# M847.net
KiCad netlist of a schematic drawn in EAGLE
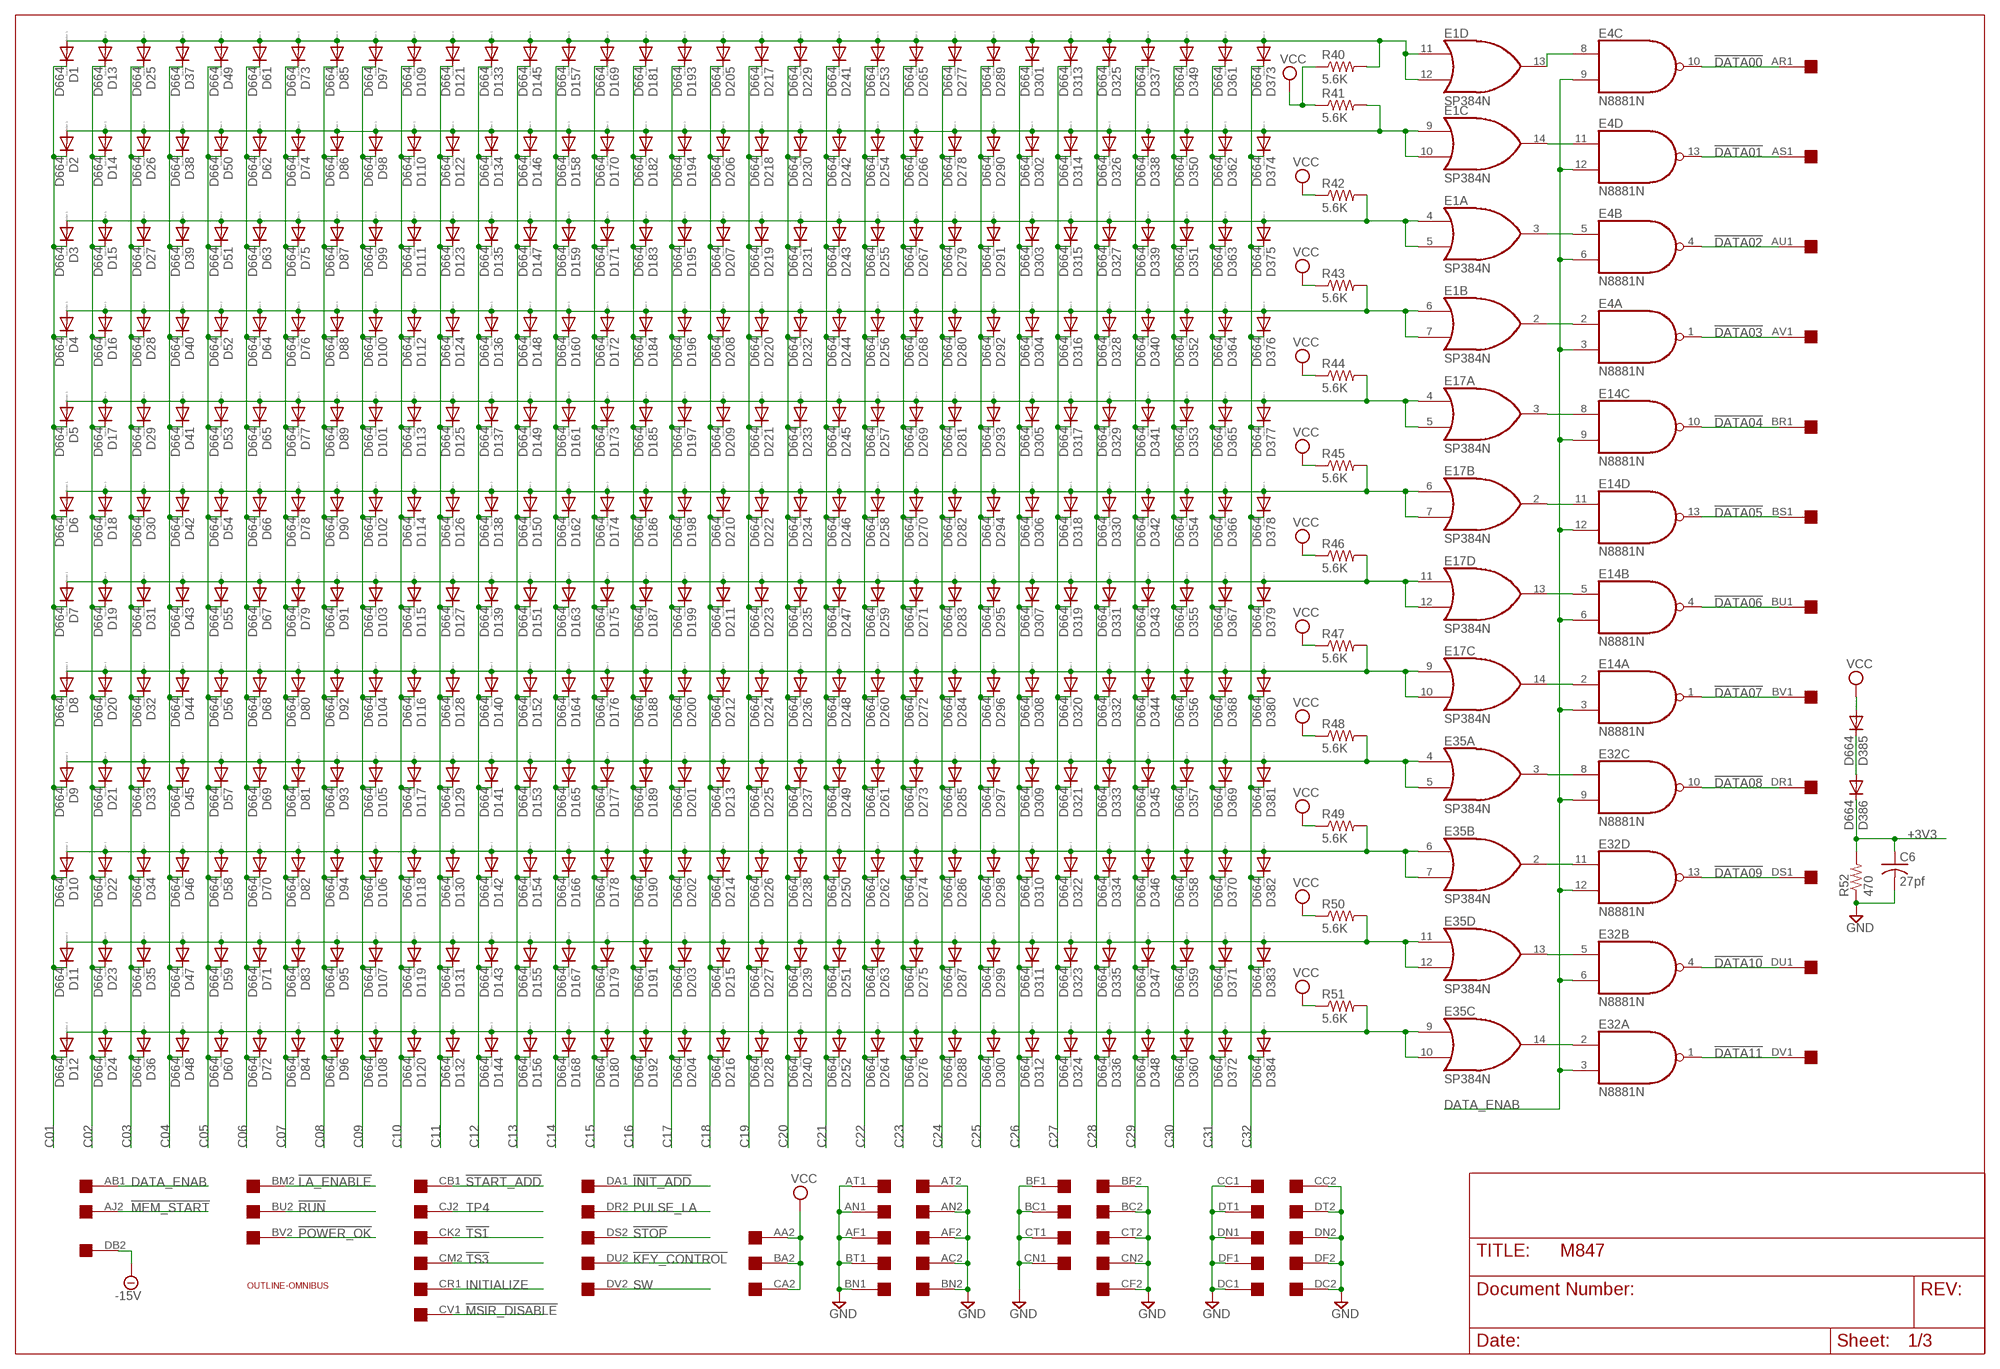
[diagram p0: schematic, sheet 1]
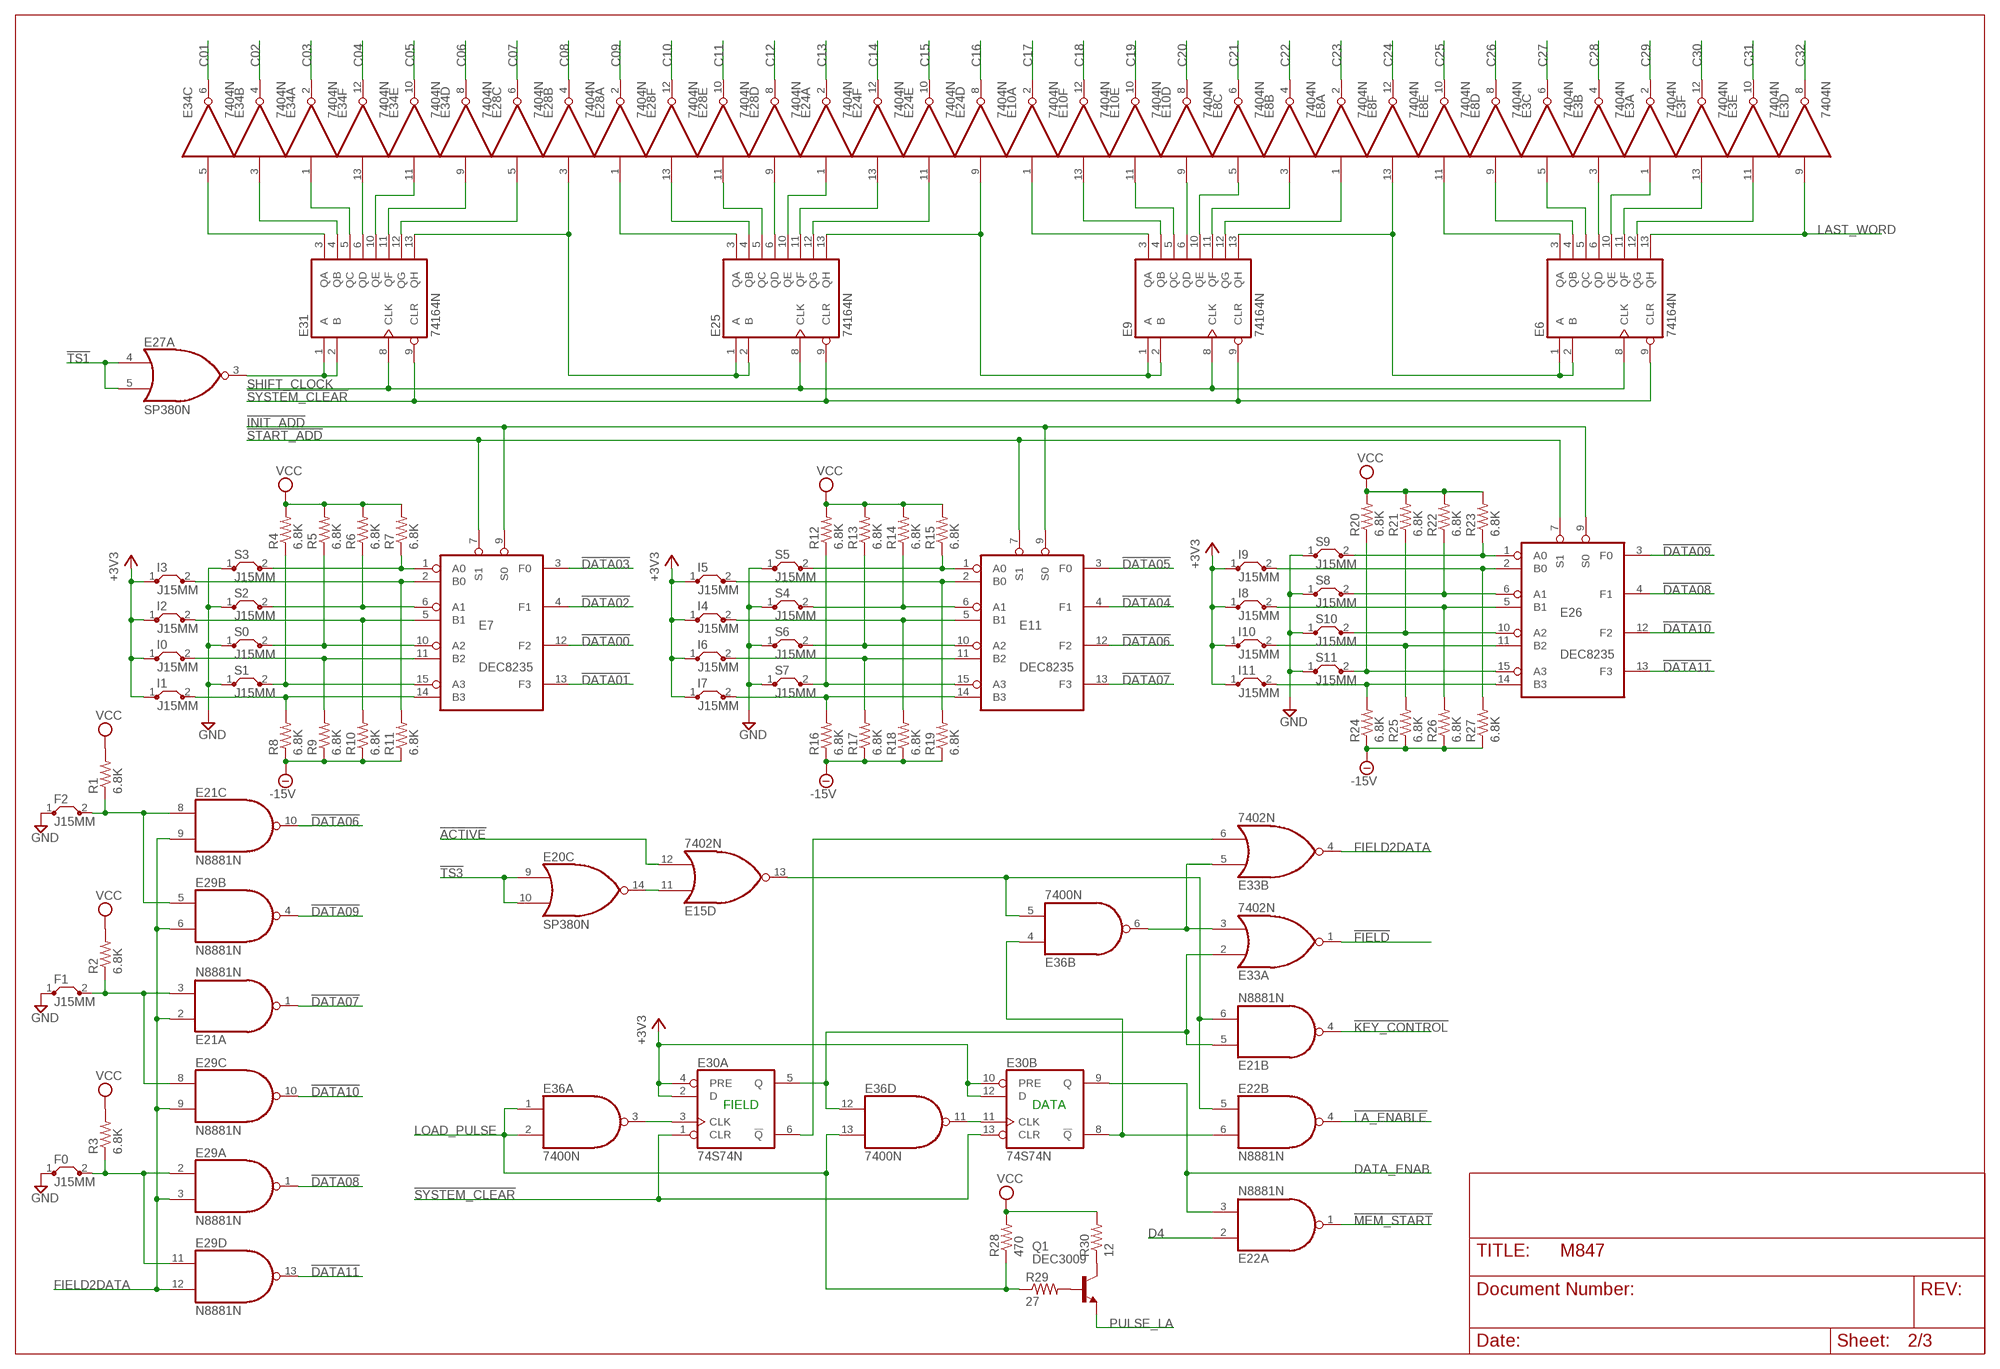
[diagram p1: schematic, sheet 2]
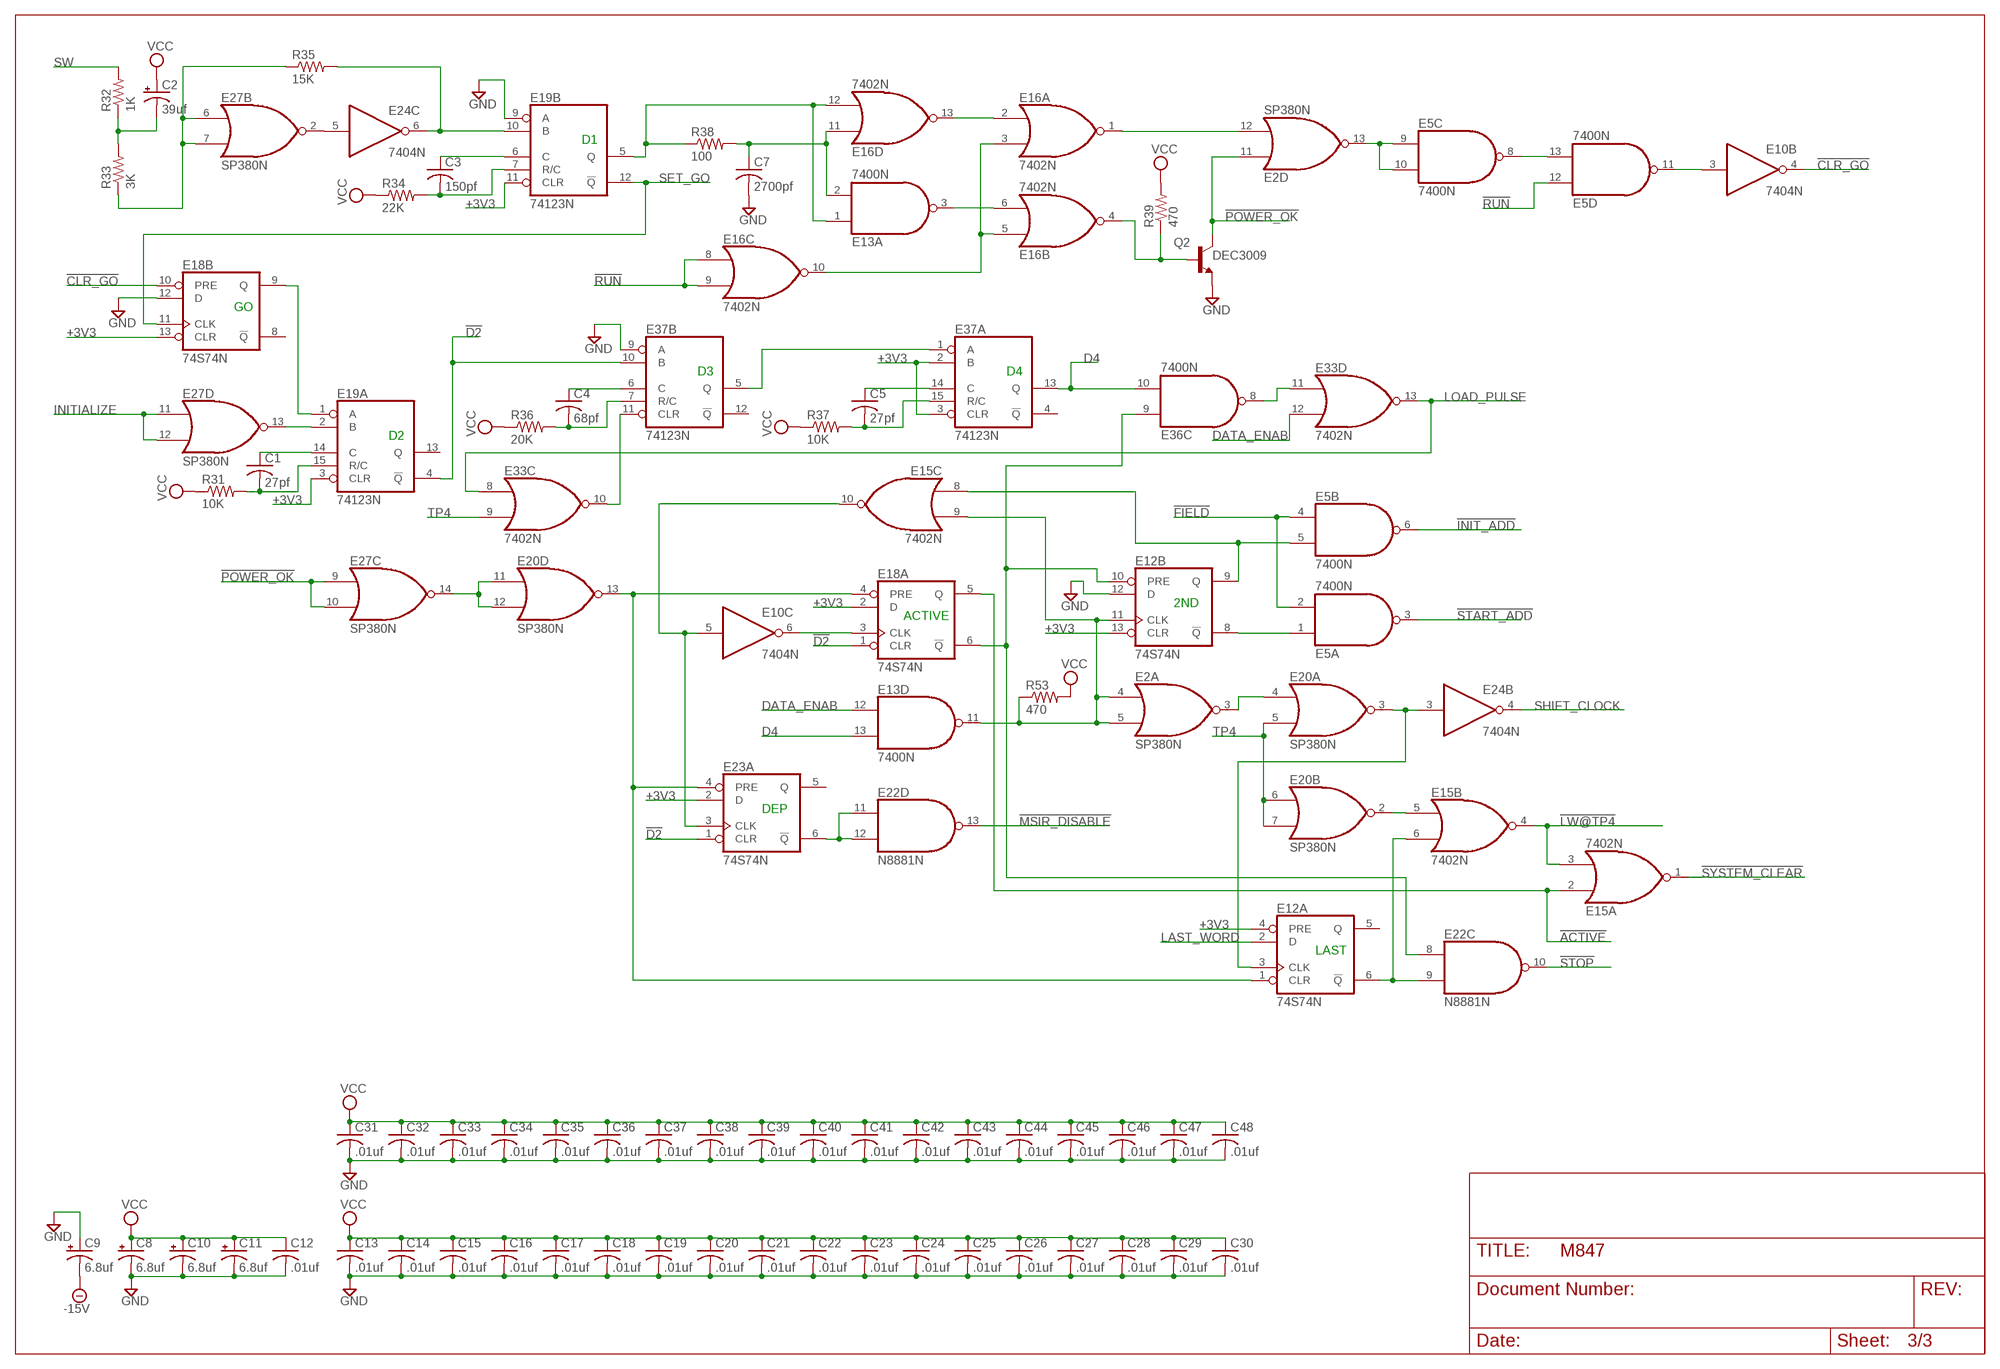
[diagram p2: schematic, sheet 3]

(export (version "E")
  (design (tool "Eeschema 10.0.6"))
  (components
    (comp (ref "C6")
      (value "27pf")
      (footprint "eagle-import:C050-025X075")
      (libsource (lib "eagle-import") (part "C-US050-025X075"))
    )
    (comp (ref "D1")
      (value "D664")
      (footprint "eagle-import:DO35-10")
      (libsource (lib "eagle-import") (part "1N4148DO35-10"))
    )
    (comp (ref "D2")
      (value "D664")
      (footprint "eagle-import:DO35-10")
      (libsource (lib "eagle-import") (part "1N4148DO35-10"))
    )
    (comp (ref "D3")
      (value "D664")
      (footprint "eagle-import:DO35-10")
      (libsource (lib "eagle-import") (part "1N4148DO35-10"))
    )
    (comp (ref "D4")
      (value "D664")
      (footprint "eagle-import:DO35-10")
      (libsource (lib "eagle-import") (part "1N4148DO35-10"))
    )
    (comp (ref "D5")
      (value "D664")
      (footprint "eagle-import:DO35-10")
      (libsource (lib "eagle-import") (part "1N4148DO35-10"))
    )
    (comp (ref "D6")
      (value "D664")
      (footprint "eagle-import:DO35-10")
      (libsource (lib "eagle-import") (part "1N4148DO35-10"))
    )
    (comp (ref "D7")
      (value "D664")
      (footprint "eagle-import:DO35-10")
      (libsource (lib "eagle-import") (part "1N4148DO35-10"))
    )
    (comp (ref "D8")
      (value "D664")
      (footprint "eagle-import:DO35-10")
      (libsource (lib "eagle-import") (part "1N4148DO35-10"))
    )
    (comp (ref "D9")
      (value "D664")
      (footprint "eagle-import:DO35-10")
      (libsource (lib "eagle-import") (part "1N4148DO35-10"))
    )
    (comp (ref "D10")
      (value "D664")
      (footprint "eagle-import:DO35-10")
      (libsource (lib "eagle-import") (part "1N4148DO35-10"))
    )
    (comp (ref "D11")
      (value "D664")
      (footprint "eagle-import:DO35-10")
      (libsource (lib "eagle-import") (part "1N4148DO35-10"))
    )
    (comp (ref "D12")
      (value "D664")
      (footprint "eagle-import:DO35-10")
      (libsource (lib "eagle-import") (part "1N4148DO35-10"))
    )
    (comp (ref "D13")
      (value "D664")
      (footprint "eagle-import:DO35-10")
      (libsource (lib "eagle-import") (part "1N4148DO35-10"))
    )
    (comp (ref "D14")
      (value "D664")
      (footprint "eagle-import:DO35-10")
      (libsource (lib "eagle-import") (part "1N4148DO35-10"))
    )
    (comp (ref "D15")
      (value "D664")
      (footprint "eagle-import:DO35-10")
      (libsource (lib "eagle-import") (part "1N4148DO35-10"))
    )
    (comp (ref "D16")
      (value "D664")
      (footprint "eagle-import:DO35-10")
      (libsource (lib "eagle-import") (part "1N4148DO35-10"))
    )
    (comp (ref "D17")
      (value "D664")
      (footprint "eagle-import:DO35-10")
      (libsource (lib "eagle-import") (part "1N4148DO35-10"))
    )
    (comp (ref "D18")
      (value "D664")
      (footprint "eagle-import:DO35-10")
      (libsource (lib "eagle-import") (part "1N4148DO35-10"))
    )
    (comp (ref "D19")
      (value "D664")
      (footprint "eagle-import:DO35-10")
      (libsource (lib "eagle-import") (part "1N4148DO35-10"))
    )
    (comp (ref "D20")
      (value "D664")
      (footprint "eagle-import:DO35-10")
      (libsource (lib "eagle-import") (part "1N4148DO35-10"))
    )
    (comp (ref "D21")
      (value "D664")
      (footprint "eagle-import:DO35-10")
      (libsource (lib "eagle-import") (part "1N4148DO35-10"))
    )
    (comp (ref "D22")
      (value "D664")
      (footprint "eagle-import:DO35-10")
      (libsource (lib "eagle-import") (part "1N4148DO35-10"))
    )
    (comp (ref "D23")
      (value "D664")
      (footprint "eagle-import:DO35-10")
      (libsource (lib "eagle-import") (part "1N4148DO35-10"))
    )
    (comp (ref "D24")
      (value "D664")
      (footprint "eagle-import:DO35-10")
      (libsource (lib "eagle-import") (part "1N4148DO35-10"))
    )
    (comp (ref "D25")
      (value "D664")
      (footprint "eagle-import:DO35-10")
      (libsource (lib "eagle-import") (part "1N4148DO35-10"))
    )
    (comp (ref "D26")
      (value "D664")
      (footprint "eagle-import:DO35-10")
      (libsource (lib "eagle-import") (part "1N4148DO35-10"))
    )
    (comp (ref "D27")
      (value "D664")
      (footprint "eagle-import:DO35-10")
      (libsource (lib "eagle-import") (part "1N4148DO35-10"))
    )
    (comp (ref "D28")
      (value "D664")
      (footprint "eagle-import:DO35-10")
      (libsource (lib "eagle-import") (part "1N4148DO35-10"))
    )
    (comp (ref "D29")
      (value "D664")
      (footprint "eagle-import:DO35-10")
      (libsource (lib "eagle-import") (part "1N4148DO35-10"))
    )
    (comp (ref "D30")
      (value "D664")
      (footprint "eagle-import:DO35-10")
      (libsource (lib "eagle-import") (part "1N4148DO35-10"))
    )
    (comp (ref "D31")
      (value "D664")
      (footprint "eagle-import:DO35-10")
      (libsource (lib "eagle-import") (part "1N4148DO35-10"))
    )
    (comp (ref "D32")
      (value "D664")
      (footprint "eagle-import:DO35-10")
      (libsource (lib "eagle-import") (part "1N4148DO35-10"))
    )
    (comp (ref "D33")
      (value "D664")
      (footprint "eagle-import:DO35-10")
      (libsource (lib "eagle-import") (part "1N4148DO35-10"))
    )
    (comp (ref "D34")
      (value "D664")
      (footprint "eagle-import:DO35-10")
      (libsource (lib "eagle-import") (part "1N4148DO35-10"))
    )
    (comp (ref "D35")
      (value "D664")
      (footprint "eagle-import:DO35-10")
      (libsource (lib "eagle-import") (part "1N4148DO35-10"))
    )
    (comp (ref "D36")
      (value "D664")
      (footprint "eagle-import:DO35-10")
      (libsource (lib "eagle-import") (part "1N4148DO35-10"))
    )
    (comp (ref "D37")
      (value "D664")
      (footprint "eagle-import:DO35-10")
      (libsource (lib "eagle-import") (part "1N4148DO35-10"))
    )
    (comp (ref "D38")
      (value "D664")
      (footprint "eagle-import:DO35-10")
      (libsource (lib "eagle-import") (part "1N4148DO35-10"))
    )
    (comp (ref "D39")
      (value "D664")
      (footprint "eagle-import:DO35-10")
      (libsource (lib "eagle-import") (part "1N4148DO35-10"))
    )
    (comp (ref "D40")
      (value "D664")
      (footprint "eagle-import:DO35-10")
      (libsource (lib "eagle-import") (part "1N4148DO35-10"))
    )
    (comp (ref "D41")
      (value "D664")
      (footprint "eagle-import:DO35-10")
      (libsource (lib "eagle-import") (part "1N4148DO35-10"))
    )
    (comp (ref "D42")
      (value "D664")
      (footprint "eagle-import:DO35-10")
      (libsource (lib "eagle-import") (part "1N4148DO35-10"))
    )
    (comp (ref "D43")
      (value "D664")
      (footprint "eagle-import:DO35-10")
      (libsource (lib "eagle-import") (part "1N4148DO35-10"))
    )
    (comp (ref "D44")
      (value "D664")
      (footprint "eagle-import:DO35-10")
      (libsource (lib "eagle-import") (part "1N4148DO35-10"))
    )
    (comp (ref "D45")
      (value "D664")
      (footprint "eagle-import:DO35-10")
      (libsource (lib "eagle-import") (part "1N4148DO35-10"))
    )
    (comp (ref "D46")
      (value "D664")
      (footprint "eagle-import:DO35-10")
      (libsource (lib "eagle-import") (part "1N4148DO35-10"))
    )
    (comp (ref "D47")
      (value "D664")
      (footprint "eagle-import:DO35-10")
      (libsource (lib "eagle-import") (part "1N4148DO35-10"))
    )
    (comp (ref "D48")
      (value "D664")
      (footprint "eagle-import:DO35-10")
      (libsource (lib "eagle-import") (part "1N4148DO35-10"))
    )
    (comp (ref "D49")
      (value "D664")
      (footprint "eagle-import:DO35-10")
      (libsource (lib "eagle-import") (part "1N4148DO35-10"))
    )
    (comp (ref "D50")
      (value "D664")
      (footprint "eagle-import:DO35-10")
      (libsource (lib "eagle-import") (part "1N4148DO35-10"))
    )
    (comp (ref "D51")
      (value "D664")
      (footprint "eagle-import:DO35-10")
      (libsource (lib "eagle-import") (part "1N4148DO35-10"))
    )
    (comp (ref "D52")
      (value "D664")
      (footprint "eagle-import:DO35-10")
      (libsource (lib "eagle-import") (part "1N4148DO35-10"))
    )
    (comp (ref "D53")
      (value "D664")
      (footprint "eagle-import:DO35-10")
      (libsource (lib "eagle-import") (part "1N4148DO35-10"))
    )
    (comp (ref "D54")
      (value "D664")
      (footprint "eagle-import:DO35-10")
      (libsource (lib "eagle-import") (part "1N4148DO35-10"))
    )
    (comp (ref "D55")
      (value "D664")
      (footprint "eagle-import:DO35-10")
      (libsource (lib "eagle-import") (part "1N4148DO35-10"))
    )
    (comp (ref "D56")
      (value "D664")
      (footprint "eagle-import:DO35-10")
      (libsource (lib "eagle-import") (part "1N4148DO35-10"))
    )
    (comp (ref "D57")
      (value "D664")
      (footprint "eagle-import:DO35-10")
      (libsource (lib "eagle-import") (part "1N4148DO35-10"))
    )
    (comp (ref "D58")
      (value "D664")
      (footprint "eagle-import:DO35-10")
      (libsource (lib "eagle-import") (part "1N4148DO35-10"))
    )
    (comp (ref "D59")
      (value "D664")
      (footprint "eagle-import:DO35-10")
      (libsource (lib "eagle-import") (part "1N4148DO35-10"))
    )
    (comp (ref "D60")
      (value "D664")
      (footprint "eagle-import:DO35-10")
      (libsource (lib "eagle-import") (part "1N4148DO35-10"))
    )
    (comp (ref "D61")
      (value "D664")
      (footprint "eagle-import:DO35-10")
      (libsource (lib "eagle-import") (part "1N4148DO35-10"))
    )
    (comp (ref "D62")
      (value "D664")
      (footprint "eagle-import:DO35-10")
      (libsource (lib "eagle-import") (part "1N4148DO35-10"))
    )
    (comp (ref "D63")
      (value "D664")
      (footprint "eagle-import:DO35-10")
      (libsource (lib "eagle-import") (part "1N4148DO35-10"))
    )
    (comp (ref "D64")
      (value "D664")
      (footprint "eagle-import:DO35-10")
      (libsource (lib "eagle-import") (part "1N4148DO35-10"))
    )
    (comp (ref "D65")
      (value "D664")
      (footprint "eagle-import:DO35-10")
      (libsource (lib "eagle-import") (part "1N4148DO35-10"))
    )
    (comp (ref "D66")
      (value "D664")
      (footprint "eagle-import:DO35-10")
      (libsource (lib "eagle-import") (part "1N4148DO35-10"))
    )
    (comp (ref "D67")
      (value "D664")
      (footprint "eagle-import:DO35-10")
      (libsource (lib "eagle-import") (part "1N4148DO35-10"))
    )
    (comp (ref "D68")
      (value "D664")
      (footprint "eagle-import:DO35-10")
      (libsource (lib "eagle-import") (part "1N4148DO35-10"))
    )
    (comp (ref "D69")
      (value "D664")
      (footprint "eagle-import:DO35-10")
      (libsource (lib "eagle-import") (part "1N4148DO35-10"))
    )
    (comp (ref "D70")
      (value "D664")
      (footprint "eagle-import:DO35-10")
      (libsource (lib "eagle-import") (part "1N4148DO35-10"))
    )
    (comp (ref "D71")
      (value "D664")
      (footprint "eagle-import:DO35-10")
      (libsource (lib "eagle-import") (part "1N4148DO35-10"))
    )
    (comp (ref "D72")
      (value "D664")
      (footprint "eagle-import:DO35-10")
      (libsource (lib "eagle-import") (part "1N4148DO35-10"))
    )
    (comp (ref "D73")
      (value "D664")
      (footprint "eagle-import:DO35-10")
      (libsource (lib "eagle-import") (part "1N4148DO35-10"))
    )
    (comp (ref "D74")
      (value "D664")
      (footprint "eagle-import:DO35-10")
      (libsource (lib "eagle-import") (part "1N4148DO35-10"))
    )
    (comp (ref "D75")
      (value "D664")
      (footprint "eagle-import:DO35-10")
      (libsource (lib "eagle-import") (part "1N4148DO35-10"))
    )
    (comp (ref "D76")
      (value "D664")
      (footprint "eagle-import:DO35-10")
      (libsource (lib "eagle-import") (part "1N4148DO35-10"))
    )
    (comp (ref "D77")
      (value "D664")
      (footprint "eagle-import:DO35-10")
      (libsource (lib "eagle-import") (part "1N4148DO35-10"))
    )
    (comp (ref "D78")
      (value "D664")
      (footprint "eagle-import:DO35-10")
      (libsource (lib "eagle-import") (part "1N4148DO35-10"))
    )
    (comp (ref "D79")
      (value "D664")
      (footprint "eagle-import:DO35-10")
      (libsource (lib "eagle-import") (part "1N4148DO35-10"))
    )
    (comp (ref "D80")
      (value "D664")
      (footprint "eagle-import:DO35-10")
      (libsource (lib "eagle-import") (part "1N4148DO35-10"))
    )
    (comp (ref "D81")
      (value "D664")
      (footprint "eagle-import:DO35-10")
      (libsource (lib "eagle-import") (part "1N4148DO35-10"))
    )
    (comp (ref "D82")
      (value "D664")
      (footprint "eagle-import:DO35-10")
      (libsource (lib "eagle-import") (part "1N4148DO35-10"))
    )
    (comp (ref "D83")
      (value "D664")
      (footprint "eagle-import:DO35-10")
      (libsource (lib "eagle-import") (part "1N4148DO35-10"))
    )
    (comp (ref "D84")
      (value "D664")
      (footprint "eagle-import:DO35-10")
      (libsource (lib "eagle-import") (part "1N4148DO35-10"))
    )
    (comp (ref "D85")
      (value "D664")
      (footprint "eagle-import:DO35-10")
      (libsource (lib "eagle-import") (part "1N4148DO35-10"))
    )
    (comp (ref "D86")
      (value "D664")
      (footprint "eagle-import:DO35-10")
      (libsource (lib "eagle-import") (part "1N4148DO35-10"))
    )
    (comp (ref "D87")
      (value "D664")
      (footprint "eagle-import:DO35-10")
      (libsource (lib "eagle-import") (part "1N4148DO35-10"))
    )
    (comp (ref "D88")
      (value "D664")
      (footprint "eagle-import:DO35-10")
      (libsource (lib "eagle-import") (part "1N4148DO35-10"))
    )
    (comp (ref "D89")
      (value "D664")
      (footprint "eagle-import:DO35-10")
      (libsource (lib "eagle-import") (part "1N4148DO35-10"))
    )
    (comp (ref "D90")
      (value "D664")
      (footprint "eagle-import:DO35-10")
      (libsource (lib "eagle-import") (part "1N4148DO35-10"))
    )
    (comp (ref "D91")
      (value "D664")
      (footprint "eagle-import:DO35-10")
      (libsource (lib "eagle-import") (part "1N4148DO35-10"))
    )
    (comp (ref "D92")
      (value "D664")
      (footprint "eagle-import:DO35-10")
      (libsource (lib "eagle-import") (part "1N4148DO35-10"))
    )
    (comp (ref "D93")
      (value "D664")
      (footprint "eagle-import:DO35-10")
      (libsource (lib "eagle-import") (part "1N4148DO35-10"))
    )
    (comp (ref "D94")
      (value "D664")
      (footprint "eagle-import:DO35-10")
      (libsource (lib "eagle-import") (part "1N4148DO35-10"))
    )
    (comp (ref "D95")
      (value "D664")
      (footprint "eagle-import:DO35-10")
      (libsource (lib "eagle-import") (part "1N4148DO35-10"))
    )
    (comp (ref "D96")
      (value "D664")
      (footprint "eagle-import:DO35-10")
      (libsource (lib "eagle-import") (part "1N4148DO35-10"))
    )
    (comp (ref "D97")
      (value "D664")
      (footprint "eagle-import:DO35-10")
      (libsource (lib "eagle-import") (part "1N4148DO35-10"))
    )
    (comp (ref "D98")
      (value "D664")
      (footprint "eagle-import:DO35-10")
      (libsource (lib "eagle-import") (part "1N4148DO35-10"))
    )
    (comp (ref "D99")
      (value "D664")
      (footprint "eagle-import:DO35-10")
      (libsource (lib "eagle-import") (part "1N4148DO35-10"))
    )
    (comp (ref "D100")
      (value "D664")
      (footprint "eagle-import:DO35-10")
      (libsource (lib "eagle-import") (part "1N4148DO35-10"))
    )
    (comp (ref "D101")
      (value "D664")
      (footprint "eagle-import:DO35-10")
      (libsource (lib "eagle-import") (part "1N4148DO35-10"))
    )
    (comp (ref "D102")
      (value "D664")
      (footprint "eagle-import:DO35-10")
      (libsource (lib "eagle-import") (part "1N4148DO35-10"))
    )
    (comp (ref "D103")
      (value "D664")
      (footprint "eagle-import:DO35-10")
      (libsource (lib "eagle-import") (part "1N4148DO35-10"))
    )
    (comp (ref "D104")
      (value "D664")
      (footprint "eagle-import:DO35-10")
      (libsource (lib "eagle-import") (part "1N4148DO35-10"))
    )
    (comp (ref "D105")
      (value "D664")
      (footprint "eagle-import:DO35-10")
      (libsource (lib "eagle-import") (part "1N4148DO35-10"))
    )
    (comp (ref "D106")
      (value "D664")
      (footprint "eagle-import:DO35-10")
      (libsource (lib "eagle-import") (part "1N4148DO35-10"))
    )
    (comp (ref "D107")
      (value "D664")
      (footprint "eagle-import:DO35-10")
      (libsource (lib "eagle-import") (part "1N4148DO35-10"))
    )
    (comp (ref "D108")
      (value "D664")
      (footprint "eagle-import:DO35-10")
      (libsource (lib "eagle-import") (part "1N4148DO35-10"))
    )
    (comp (ref "D109")
      (value "D664")
      (footprint "eagle-import:DO35-10")
      (libsource (lib "eagle-import") (part "1N4148DO35-10"))
    )
    (comp (ref "D110")
      (value "D664")
      (footprint "eagle-import:DO35-10")
      (libsource (lib "eagle-import") (part "1N4148DO35-10"))
    )
    (comp (ref "D111")
      (value "D664")
      (footprint "eagle-import:DO35-10")
      (libsource (lib "eagle-import") (part "1N4148DO35-10"))
    )
    (comp (ref "D112")
      (value "D664")
      (footprint "eagle-import:DO35-10")
      (libsource (lib "eagle-import") (part "1N4148DO35-10"))
    )
    (comp (ref "D113")
      (value "D664")
      (footprint "eagle-import:DO35-10")
      (libsource (lib "eagle-import") (part "1N4148DO35-10"))
    )
    (comp (ref "D114")
      (value "D664")
      (footprint "eagle-import:DO35-10")
      (libsource (lib "eagle-import") (part "1N4148DO35-10"))
    )
    (comp (ref "D115")
      (value "D664")
      (footprint "eagle-import:DO35-10")
      (libsource (lib "eagle-import") (part "1N4148DO35-10"))
    )
    (comp (ref "D116")
      (value "D664")
      (footprint "eagle-import:DO35-10")
      (libsource (lib "eagle-import") (part "1N4148DO35-10"))
    )
    (comp (ref "D117")
      (value "D664")
      (footprint "eagle-import:DO35-10")
      (libsource (lib "eagle-import") (part "1N4148DO35-10"))
    )
    (comp (ref "D118")
      (value "D664")
      (footprint "eagle-import:DO35-10")
      (libsource (lib "eagle-import") (part "1N4148DO35-10"))
    )
    (comp (ref "D119")
      (value "D664")
      (footprint "eagle-import:DO35-10")
      (libsource (lib "eagle-import") (part "1N4148DO35-10"))
    )
    (comp (ref "D120")
      (value "D664")
      (footprint "eagle-import:DO35-10")
      (libsource (lib "eagle-import") (part "1N4148DO35-10"))
    )
    (comp (ref "D121")
      (value "D664")
      (footprint "eagle-import:DO35-10")
      (libsource (lib "eagle-import") (part "1N4148DO35-10"))
    )
    (comp (ref "D122")
      (value "D664")
      (footprint "eagle-import:DO35-10")
      (libsource (lib "eagle-import") (part "1N4148DO35-10"))
    )
    (comp (ref "D123")
      (value "D664")
      (footprint "eagle-import:DO35-10")
      (libsource (lib "eagle-import") (part "1N4148DO35-10"))
    )
    (comp (ref "D124")
      (value "D664")
      (footprint "eagle-import:DO35-10")
      (libsource (lib "eagle-import") (part "1N4148DO35-10"))
    )
    (comp (ref "D125")
      (value "D664")
      (footprint "eagle-import:DO35-10")
      (libsource (lib "eagle-import") (part "1N4148DO35-10"))
    )
    (comp (ref "D126")
      (value "D664")
      (footprint "eagle-import:DO35-10")
      (libsource (lib "eagle-import") (part "1N4148DO35-10"))
    )
    (comp (ref "D127")
      (value "D664")
      (footprint "eagle-import:DO35-10")
      (libsource (lib "eagle-import") (part "1N4148DO35-10"))
    )
    (comp (ref "D128")
      (value "D664")
      (footprint "eagle-import:DO35-10")
      (libsource (lib "eagle-import") (part "1N4148DO35-10"))
    )
    (comp (ref "D129")
      (value "D664")
      (footprint "eagle-import:DO35-10")
      (libsource (lib "eagle-import") (part "1N4148DO35-10"))
    )
    (comp (ref "D130")
      (value "D664")
      (footprint "eagle-import:DO35-10")
      (libsource (lib "eagle-import") (part "1N4148DO35-10"))
    )
    (comp (ref "D131")
      (value "D664")
      (footprint "eagle-import:DO35-10")
      (libsource (lib "eagle-import") (part "1N4148DO35-10"))
    )
    (comp (ref "D132")
      (value "D664")
      (footprint "eagle-import:DO35-10")
      (libsource (lib "eagle-import") (part "1N4148DO35-10"))
    )
    (comp (ref "D133")
      (value "D664")
      (footprint "eagle-import:DO35-10")
      (libsource (lib "eagle-import") (part "1N4148DO35-10"))
    )
    (comp (ref "D134")
      (value "D664")
      (footprint "eagle-import:DO35-10")
      (libsource (lib "eagle-import") (part "1N4148DO35-10"))
    )
    (comp (ref "D135")
      (value "D664")
      (footprint "eagle-import:DO35-10")
      (libsource (lib "eagle-import") (part "1N4148DO35-10"))
    )
    (comp (ref "D136")
      (value "D664")
      (footprint "eagle-import:DO35-10")
      (libsource (lib "eagle-import") (part "1N4148DO35-10"))
    )
    (comp (ref "D137")
      (value "D664")
      (footprint "eagle-import:DO35-10")
      (libsource (lib "eagle-import") (part "1N4148DO35-10"))
    )
    (comp (ref "D138")
      (value "D664")
      (footprint "eagle-import:DO35-10")
      (libsource (lib "eagle-import") (part "1N4148DO35-10"))
    )
    (comp (ref "D139")
      (value "D664")
      (footprint "eagle-import:DO35-10")
      (libsource (lib "eagle-import") (part "1N4148DO35-10"))
    )
    (comp (ref "D140")
      (value "D664")
      (footprint "eagle-import:DO35-10")
      (libsource (lib "eagle-import") (part "1N4148DO35-10"))
    )
    (comp (ref "D141")
      (value "D664")
      (footprint "eagle-import:DO35-10")
      (libsource (lib "eagle-import") (part "1N4148DO35-10"))
    )
    (comp (ref "D142")
      (value "D664")
      (footprint "eagle-import:DO35-10")
      (libsource (lib "eagle-import") (part "1N4148DO35-10"))
    )
    (comp (ref "D143")
      (value "D664")
      (footprint "eagle-import:DO35-10")
      (libsource (lib "eagle-import") (part "1N4148DO35-10"))
    )
    (comp (ref "D144")
      (value "D664")
      (footprint "eagle-import:DO35-10")
      (libsource (lib "eagle-import") (part "1N4148DO35-10"))
    )
    (comp (ref "D145")
      (value "D664")
      (footprint "eagle-import:DO35-10")
      (libsource (lib "eagle-import") (part "1N4148DO35-10"))
    )
    (comp (ref "D146")
      (value "D664")
      (footprint "eagle-import:DO35-10")
      (libsource (lib "eagle-import") (part "1N4148DO35-10"))
    )
    (comp (ref "D147")
      (value "D664")
      (footprint "eagle-import:DO35-10")
      (libsource (lib "eagle-import") (part "1N4148DO35-10"))
    )
    (comp (ref "D148")
      (value "D664")
      (footprint "eagle-import:DO35-10")
      (libsource (lib "eagle-import") (part "1N4148DO35-10"))
    )
    (comp (ref "D149")
      (value "D664")
      (footprint "eagle-import:DO35-10")
      (libsource (lib "eagle-import") (part "1N4148DO35-10"))
    )
    (comp (ref "D150")
      (value "D664")
      (footprint "eagle-import:DO35-10")
      (libsource (lib "eagle-import") (part "1N4148DO35-10"))
    )
    (comp (ref "D151")
      (value "D664")
      (footprint "eagle-import:DO35-10")
      (libsource (lib "eagle-import") (part "1N4148DO35-10"))
    )
    (comp (ref "D152")
      (value "D664")
      (footprint "eagle-import:DO35-10")
      (libsource (lib "eagle-import") (part "1N4148DO35-10"))
    )
    (comp (ref "D153")
      (value "D664")
      (footprint "eagle-import:DO35-10")
      (libsource (lib "eagle-import") (part "1N4148DO35-10"))
    )
    (comp (ref "D154")
      (value "D664")
      (footprint "eagle-import:DO35-10")
      (libsource (lib "eagle-import") (part "1N4148DO35-10"))
    )
    (comp (ref "D155")
      (value "D664")
      (footprint "eagle-import:DO35-10")
      (libsource (lib "eagle-import") (part "1N4148DO35-10"))
    )
    (comp (ref "D156")
      (value "D664")
      (footprint "eagle-import:DO35-10")
      (libsource (lib "eagle-import") (part "1N4148DO35-10"))
    )
    (comp (ref "D157")
      (value "D664")
      (footprint "eagle-import:DO35-10")
      (libsource (lib "eagle-import") (part "1N4148DO35-10"))
    )
    (comp (ref "D158")
      (value "D664")
      (footprint "eagle-import:DO35-10")
      (libsource (lib "eagle-import") (part "1N4148DO35-10"))
    )
    (comp (ref "D159")
      (value "D664")
      (footprint "eagle-import:DO35-10")
      (libsource (lib "eagle-import") (part "1N4148DO35-10"))
    )
    (comp (ref "D160")
      (value "D664")
      (footprint "eagle-import:DO35-10")
      (libsource (lib "eagle-import") (part "1N4148DO35-10"))
    )
    (comp (ref "D161")
      (value "D664")
      (footprint "eagle-import:DO35-10")
      (libsource (lib "eagle-import") (part "1N4148DO35-10"))
    )
    (comp (ref "D162")
      (value "D664")
      (footprint "eagle-import:DO35-10")
      (libsource (lib "eagle-import") (part "1N4148DO35-10"))
    )
    (comp (ref "D163")
      (value "D664")
      (footprint "eagle-import:DO35-10")
      (libsource (lib "eagle-import") (part "1N4148DO35-10"))
    )
    (comp (ref "D164")
      (value "D664")
      (footprint "eagle-import:DO35-10")
      (libsource (lib "eagle-import") (part "1N4148DO35-10"))
    )
    (comp (ref "D165")
      (value "D664")
      (footprint "eagle-import:DO35-10")
      (libsource (lib "eagle-import") (part "1N4148DO35-10"))
    )
    (comp (ref "D166")
      (value "D664")
      (footprint "eagle-import:DO35-10")
      (libsource (lib "eagle-import") (part "1N4148DO35-10"))
    )
    (comp (ref "D167")
      (value "D664")
      (footprint "eagle-import:DO35-10")
      (libsource (lib "eagle-import") (part "1N4148DO35-10"))
    )
    (comp (ref "D168")
      (value "D664")
      (footprint "eagle-import:DO35-10")
      (libsource (lib "eagle-import") (part "1N4148DO35-10"))
    )
    (comp (ref "D169")
      (value "D664")
      (footprint "eagle-import:DO35-10")
      (libsource (lib "eagle-import") (part "1N4148DO35-10"))
    )
    (comp (ref "D170")
      (value "D664")
      (footprint "eagle-import:DO35-10")
      (libsource (lib "eagle-import") (part "1N4148DO35-10"))
    )
    (comp (ref "D171")
      (value "D664")
      (footprint "eagle-import:DO35-10")
      (libsource (lib "eagle-import") (part "1N4148DO35-10"))
    )
    (comp (ref "D172")
      (value "D664")
      (footprint "eagle-import:DO35-10")
      (libsource (lib "eagle-import") (part "1N4148DO35-10"))
    )
    (comp (ref "D173")
      (value "D664")
      (footprint "eagle-import:DO35-10")
      (libsource (lib "eagle-import") (part "1N4148DO35-10"))
    )
    (comp (ref "D174")
      (value "D664")
      (footprint "eagle-import:DO35-10")
      (libsource (lib "eagle-import") (part "1N4148DO35-10"))
    )
    (comp (ref "D175")
      (value "D664")
      (footprint "eagle-import:DO35-10")
      (libsource (lib "eagle-import") (part "1N4148DO35-10"))
    )
    (comp (ref "D176")
      (value "D664")
      (footprint "eagle-import:DO35-10")
      (libsource (lib "eagle-import") (part "1N4148DO35-10"))
    )
    (comp (ref "D177")
      (value "D664")
      (footprint "eagle-import:DO35-10")
      (libsource (lib "eagle-import") (part "1N4148DO35-10"))
    )
    (comp (ref "D178")
      (value "D664")
      (footprint "eagle-import:DO35-10")
      (libsource (lib "eagle-import") (part "1N4148DO35-10"))
    )
    (comp (ref "D179")
      (value "D664")
      (footprint "eagle-import:DO35-10")
      (libsource (lib "eagle-import") (part "1N4148DO35-10"))
    )
    (comp (ref "D180")
      (value "D664")
      (footprint "eagle-import:DO35-10")
      (libsource (lib "eagle-import") (part "1N4148DO35-10"))
    )
    (comp (ref "D181")
      (value "D664")
      (footprint "eagle-import:DO35-10")
      (libsource (lib "eagle-import") (part "1N4148DO35-10"))
    )
    (comp (ref "D182")
      (value "D664")
      (footprint "eagle-import:DO35-10")
      (libsource (lib "eagle-import") (part "1N4148DO35-10"))
    )
    (comp (ref "D183")
      (value "D664")
      (footprint "eagle-import:DO35-10")
      (libsource (lib "eagle-import") (part "1N4148DO35-10"))
    )
    (comp (ref "D184")
      (value "D664")
      (footprint "eagle-import:DO35-10")
      (libsource (lib "eagle-import") (part "1N4148DO35-10"))
    )
    (comp (ref "D185")
      (value "D664")
      (footprint "eagle-import:DO35-10")
      (libsource (lib "eagle-import") (part "1N4148DO35-10"))
    )
    (comp (ref "D186")
      (value "D664")
      (footprint "eagle-import:DO35-10")
      (libsource (lib "eagle-import") (part "1N4148DO35-10"))
    )
    (comp (ref "D187")
      (value "D664")
      (footprint "eagle-import:DO35-10")
      (libsource (lib "eagle-import") (part "1N4148DO35-10"))
    )
    (comp (ref "D188")
      (value "D664")
      (footprint "eagle-import:DO35-10")
      (libsource (lib "eagle-import") (part "1N4148DO35-10"))
    )
    (comp (ref "D189")
      (value "D664")
      (footprint "eagle-import:DO35-10")
      (libsource (lib "eagle-import") (part "1N4148DO35-10"))
    )
    (comp (ref "D190")
      (value "D664")
      (footprint "eagle-import:DO35-10")
      (libsource (lib "eagle-import") (part "1N4148DO35-10"))
    )
    (comp (ref "D191")
      (value "D664")
      (footprint "eagle-import:DO35-10")
      (libsource (lib "eagle-import") (part "1N4148DO35-10"))
    )
    (comp (ref "D192")
      (value "D664")
      (footprint "eagle-import:DO35-10")
      (libsource (lib "eagle-import") (part "1N4148DO35-10"))
    )
    (comp (ref "D193")
      (value "D664")
      (footprint "eagle-import:DO35-10")
      (libsource (lib "eagle-import") (part "1N4148DO35-10"))
    )
    (comp (ref "D194")
      (value "D664")
      (footprint "eagle-import:DO35-10")
      (libsource (lib "eagle-import") (part "1N4148DO35-10"))
    )
    (comp (ref "D195")
      (value "D664")
      (footprint "eagle-import:DO35-10")
      (libsource (lib "eagle-import") (part "1N4148DO35-10"))
    )
    (comp (ref "D196")
      (value "D664")
      (footprint "eagle-import:DO35-10")
      (libsource (lib "eagle-import") (part "1N4148DO35-10"))
    )
    (comp (ref "D197")
      (value "D664")
      (footprint "eagle-import:DO35-10")
      (libsource (lib "eagle-import") (part "1N4148DO35-10"))
    )
    (comp (ref "D198")
      (value "D664")
      (footprint "eagle-import:DO35-10")
      (libsource (lib "eagle-import") (part "1N4148DO35-10"))
    )
    (comp (ref "D199")
      (value "D664")
      (footprint "eagle-import:DO35-10")
      (libsource (lib "eagle-import") (part "1N4148DO35-10"))
    )
    (comp (ref "D200")
      (value "D664")
      (footprint "eagle-import:DO35-10")
      (libsource (lib "eagle-import") (part "1N4148DO35-10"))
    )
    (comp (ref "D201")
      (value "D664")
      (footprint "eagle-import:DO35-10")
      (libsource (lib "eagle-import") (part "1N4148DO35-10"))
    )
    (comp (ref "D202")
      (value "D664")
      (footprint "eagle-import:DO35-10")
      (libsource (lib "eagle-import") (part "1N4148DO35-10"))
    )
    (comp (ref "D203")
      (value "D664")
      (footprint "eagle-import:DO35-10")
      (libsource (lib "eagle-import") (part "1N4148DO35-10"))
    )
    (comp (ref "D204")
      (value "D664")
      (footprint "eagle-import:DO35-10")
      (libsource (lib "eagle-import") (part "1N4148DO35-10"))
    )
    (comp (ref "D205")
      (value "D664")
      (footprint "eagle-import:DO35-10")
      (libsource (lib "eagle-import") (part "1N4148DO35-10"))
    )
    (comp (ref "D206")
      (value "D664")
      (footprint "eagle-import:DO35-10")
      (libsource (lib "eagle-import") (part "1N4148DO35-10"))
    )
    (comp (ref "D207")
      (value "D664")
      (footprint "eagle-import:DO35-10")
      (libsource (lib "eagle-import") (part "1N4148DO35-10"))
    )
    (comp (ref "D208")
      (value "D664")
      (footprint "eagle-import:DO35-10")
      (libsource (lib "eagle-import") (part "1N4148DO35-10"))
    )
    (comp (ref "D209")
      (value "D664")
      (footprint "eagle-import:DO35-10")
      (libsource (lib "eagle-import") (part "1N4148DO35-10"))
    )
    (comp (ref "D210")
      (value "D664")
      (footprint "eagle-import:DO35-10")
      (libsource (lib "eagle-import") (part "1N4148DO35-10"))
    )
    (comp (ref "D211")
      (value "D664")
      (footprint "eagle-import:DO35-10")
      (libsource (lib "eagle-import") (part "1N4148DO35-10"))
    )
    (comp (ref "D212")
      (value "D664")
      (footprint "eagle-import:DO35-10")
      (libsource (lib "eagle-import") (part "1N4148DO35-10"))
    )
    (comp (ref "D213")
      (value "D664")
      (footprint "eagle-import:DO35-10")
      (libsource (lib "eagle-import") (part "1N4148DO35-10"))
    )
    (comp (ref "D214")
      (value "D664")
      (footprint "eagle-import:DO35-10")
      (libsource (lib "eagle-import") (part "1N4148DO35-10"))
    )
    (comp (ref "D215")
      (value "D664")
      (footprint "eagle-import:DO35-10")
      (libsource (lib "eagle-import") (part "1N4148DO35-10"))
    )
    (comp (ref "D216")
      (value "D664")
      (footprint "eagle-import:DO35-10")
      (libsource (lib "eagle-import") (part "1N4148DO35-10"))
    )
    (comp (ref "D217")
      (value "D664")
      (footprint "eagle-import:DO35-10")
      (libsource (lib "eagle-import") (part "1N4148DO35-10"))
    )
    (comp (ref "D218")
      (value "D664")
      (footprint "eagle-import:DO35-10")
      (libsource (lib "eagle-import") (part "1N4148DO35-10"))
    )
    (comp (ref "D219")
      (value "D664")
      (footprint "eagle-import:DO35-10")
      (libsource (lib "eagle-import") (part "1N4148DO35-10"))
    )
    (comp (ref "D220")
      (value "D664")
      (footprint "eagle-import:DO35-10")
      (libsource (lib "eagle-import") (part "1N4148DO35-10"))
    )
    (comp (ref "D221")
      (value "D664")
      (footprint "eagle-import:DO35-10")
      (libsource (lib "eagle-import") (part "1N4148DO35-10"))
    )
    (comp (ref "D222")
      (value "D664")
      (footprint "eagle-import:DO35-10")
      (libsource (lib "eagle-import") (part "1N4148DO35-10"))
    )
    (comp (ref "D223")
      (value "D664")
      (footprint "eagle-import:DO35-10")
      (libsource (lib "eagle-import") (part "1N4148DO35-10"))
    )
    (comp (ref "D224")
      (value "D664")
      (footprint "eagle-import:DO35-10")
      (libsource (lib "eagle-import") (part "1N4148DO35-10"))
    )
    (comp (ref "D225")
      (value "D664")
      (footprint "eagle-import:DO35-10")
      (libsource (lib "eagle-import") (part "1N4148DO35-10"))
    )
    (comp (ref "D226")
      (value "D664")
      (footprint "eagle-import:DO35-10")
      (libsource (lib "eagle-import") (part "1N4148DO35-10"))
    )
    (comp (ref "D227")
      (value "D664")
      (footprint "eagle-import:DO35-10")
      (libsource (lib "eagle-import") (part "1N4148DO35-10"))
    )
    (comp (ref "D228")
      (value "D664")
      (footprint "eagle-import:DO35-10")
      (libsource (lib "eagle-import") (part "1N4148DO35-10"))
    )
    (comp (ref "D229")
      (value "D664")
      (footprint "eagle-import:DO35-10")
      (libsource (lib "eagle-import") (part "1N4148DO35-10"))
    )
    (comp (ref "D230")
      (value "D664")
      (footprint "eagle-import:DO35-10")
      (libsource (lib "eagle-import") (part "1N4148DO35-10"))
    )
    (comp (ref "D231")
      (value "D664")
      (footprint "eagle-import:DO35-10")
      (libsource (lib "eagle-import") (part "1N4148DO35-10"))
    )
    (comp (ref "D232")
      (value "D664")
      (footprint "eagle-import:DO35-10")
      (libsource (lib "eagle-import") (part "1N4148DO35-10"))
    )
    (comp (ref "D233")
      (value "D664")
      (footprint "eagle-import:DO35-10")
      (libsource (lib "eagle-import") (part "1N4148DO35-10"))
    )
    (comp (ref "D234")
      (value "D664")
      (footprint "eagle-import:DO35-10")
      (libsource (lib "eagle-import") (part "1N4148DO35-10"))
    )
    (comp (ref "D235")
      (value "D664")
      (footprint "eagle-import:DO35-10")
      (libsource (lib "eagle-import") (part "1N4148DO35-10"))
    )
    (comp (ref "D236")
      (value "D664")
      (footprint "eagle-import:DO35-10")
      (libsource (lib "eagle-import") (part "1N4148DO35-10"))
    )
    (comp (ref "D237")
      (value "D664")
      (footprint "eagle-import:DO35-10")
      (libsource (lib "eagle-import") (part "1N4148DO35-10"))
    )
    (comp (ref "D238")
      (value "D664")
      (footprint "eagle-import:DO35-10")
      (libsource (lib "eagle-import") (part "1N4148DO35-10"))
    )
    (comp (ref "D239")
      (value "D664")
      (footprint "eagle-import:DO35-10")
      (libsource (lib "eagle-import") (part "1N4148DO35-10"))
    )
    (comp (ref "D240")
      (value "D664")
      (footprint "eagle-import:DO35-10")
      (libsource (lib "eagle-import") (part "1N4148DO35-10"))
    )
    (comp (ref "D241")
      (value "D664")
      (footprint "eagle-import:DO35-10")
      (libsource (lib "eagle-import") (part "1N4148DO35-10"))
    )
    (comp (ref "D242")
      (value "D664")
      (footprint "eagle-import:DO35-10")
      (libsource (lib "eagle-import") (part "1N4148DO35-10"))
    )
    (comp (ref "D243")
      (value "D664")
      (footprint "eagle-import:DO35-10")
      (libsource (lib "eagle-import") (part "1N4148DO35-10"))
    )
    (comp (ref "D244")
      (value "D664")
      (footprint "eagle-import:DO35-10")
      (libsource (lib "eagle-import") (part "1N4148DO35-10"))
    )
    (comp (ref "D245")
      (value "D664")
      (footprint "eagle-import:DO35-10")
      (libsource (lib "eagle-import") (part "1N4148DO35-10"))
    )
    (comp (ref "D246")
      (value "D664")
      (footprint "eagle-import:DO35-10")
      (libsource (lib "eagle-import") (part "1N4148DO35-10"))
    )
    (comp (ref "D247")
      (value "D664")
      (footprint "eagle-import:DO35-10")
      (libsource (lib "eagle-import") (part "1N4148DO35-10"))
    )
    (comp (ref "D248")
      (value "D664")
      (footprint "eagle-import:DO35-10")
      (libsource (lib "eagle-import") (part "1N4148DO35-10"))
    )
    (comp (ref "D249")
      (value "D664")
      (footprint "eagle-import:DO35-10")
      (libsource (lib "eagle-import") (part "1N4148DO35-10"))
    )
    (comp (ref "D250")
      (value "D664")
      (footprint "eagle-import:DO35-10")
      (libsource (lib "eagle-import") (part "1N4148DO35-10"))
    )
    (comp (ref "D251")
      (value "D664")
      (footprint "eagle-import:DO35-10")
      (libsource (lib "eagle-import") (part "1N4148DO35-10"))
    )
    (comp (ref "D252")
      (value "D664")
      (footprint "eagle-import:DO35-10")
      (libsource (lib "eagle-import") (part "1N4148DO35-10"))
    )
    (comp (ref "D253")
      (value "D664")
      (footprint "eagle-import:DO35-10")
      (libsource (lib "eagle-import") (part "1N4148DO35-10"))
    )
    (comp (ref "D254")
      (value "D664")
      (footprint "eagle-import:DO35-10")
      (libsource (lib "eagle-import") (part "1N4148DO35-10"))
    )
    (comp (ref "D255")
      (value "D664")
      (footprint "eagle-import:DO35-10")
      (libsource (lib "eagle-import") (part "1N4148DO35-10"))
    )
    (comp (ref "D256")
      (value "D664")
      (footprint "eagle-import:DO35-10")
      (libsource (lib "eagle-import") (part "1N4148DO35-10"))
    )
    (comp (ref "D257")
      (value "D664")
      (footprint "eagle-import:DO35-10")
      (libsource (lib "eagle-import") (part "1N4148DO35-10"))
    )
    (comp (ref "D258")
      (value "D664")
      (footprint "eagle-import:DO35-10")
      (libsource (lib "eagle-import") (part "1N4148DO35-10"))
    )
    (comp (ref "D259")
      (value "D664")
      (footprint "eagle-import:DO35-10")
      (libsource (lib "eagle-import") (part "1N4148DO35-10"))
    )
    (comp (ref "D260")
      (value "D664")
      (footprint "eagle-import:DO35-10")
      (libsource (lib "eagle-import") (part "1N4148DO35-10"))
    )
    (comp (ref "D261")
      (value "D664")
      (footprint "eagle-import:DO35-10")
      (libsource (lib "eagle-import") (part "1N4148DO35-10"))
    )
    (comp (ref "D262")
      (value "D664")
      (footprint "eagle-import:DO35-10")
      (libsource (lib "eagle-import") (part "1N4148DO35-10"))
    )
    (comp (ref "D263")
      (value "D664")
      (footprint "eagle-import:DO35-10")
      (libsource (lib "eagle-import") (part "1N4148DO35-10"))
    )
    (comp (ref "D264")
      (value "D664")
      (footprint "eagle-import:DO35-10")
      (libsource (lib "eagle-import") (part "1N4148DO35-10"))
    )
    (comp (ref "D265")
      (value "D664")
      (footprint "eagle-import:DO35-10")
      (libsource (lib "eagle-import") (part "1N4148DO35-10"))
    )
    (comp (ref "D266")
      (value "D664")
      (footprint "eagle-import:DO35-10")
      (libsource (lib "eagle-import") (part "1N4148DO35-10"))
    )
    (comp (ref "D267")
      (value "D664")
      (footprint "eagle-import:DO35-10")
      (libsource (lib "eagle-import") (part "1N4148DO35-10"))
    )
    (comp (ref "D268")
      (value "D664")
      (footprint "eagle-import:DO35-10")
      (libsource (lib "eagle-import") (part "1N4148DO35-10"))
    )
    (comp (ref "D269")
      (value "D664")
      (footprint "eagle-import:DO35-10")
      (libsource (lib "eagle-import") (part "1N4148DO35-10"))
    )
    (comp (ref "D270")
      (value "D664")
      (footprint "eagle-import:DO35-10")
      (libsource (lib "eagle-import") (part "1N4148DO35-10"))
    )
    (comp (ref "D271")
      (value "D664")
      (footprint "eagle-import:DO35-10")
      (libsource (lib "eagle-import") (part "1N4148DO35-10"))
    )
    (comp (ref "D272")
      (value "D664")
      (footprint "eagle-import:DO35-10")
      (libsource (lib "eagle-import") (part "1N4148DO35-10"))
    )
    (comp (ref "D273")
      (value "D664")
      (footprint "eagle-import:DO35-10")
      (libsource (lib "eagle-import") (part "1N4148DO35-10"))
    )
    (comp (ref "D274")
      (value "D664")
      (footprint "eagle-import:DO35-10")
      (libsource (lib "eagle-import") (part "1N4148DO35-10"))
    )
    (comp (ref "D275")
      (value "D664")
      (footprint "eagle-import:DO35-10")
      (libsource (lib "eagle-import") (part "1N4148DO35-10"))
    )
    (comp (ref "D276")
      (value "D664")
      (footprint "eagle-import:DO35-10")
      (libsource (lib "eagle-import") (part "1N4148DO35-10"))
    )
    (comp (ref "D277")
      (value "D664")
      (footprint "eagle-import:DO35-10")
      (libsource (lib "eagle-import") (part "1N4148DO35-10"))
    )
    (comp (ref "D278")
      (value "D664")
      (footprint "eagle-import:DO35-10")
      (libsource (lib "eagle-import") (part "1N4148DO35-10"))
    )
    (comp (ref "D279")
      (value "D664")
      (footprint "eagle-import:DO35-10")
      (libsource (lib "eagle-import") (part "1N4148DO35-10"))
    )
    (comp (ref "D280")
      (value "D664")
      (footprint "eagle-import:DO35-10")
      (libsource (lib "eagle-import") (part "1N4148DO35-10"))
    )
    (comp (ref "D281")
      (value "D664")
      (footprint "eagle-import:DO35-10")
      (libsource (lib "eagle-import") (part "1N4148DO35-10"))
    )
    (comp (ref "D282")
      (value "D664")
      (footprint "eagle-import:DO35-10")
      (libsource (lib "eagle-import") (part "1N4148DO35-10"))
    )
    (comp (ref "D283")
      (value "D664")
      (footprint "eagle-import:DO35-10")
      (libsource (lib "eagle-import") (part "1N4148DO35-10"))
    )
    (comp (ref "D284")
      (value "D664")
      (footprint "eagle-import:DO35-10")
      (libsource (lib "eagle-import") (part "1N4148DO35-10"))
    )
    (comp (ref "D285")
      (value "D664")
      (footprint "eagle-import:DO35-10")
      (libsource (lib "eagle-import") (part "1N4148DO35-10"))
    )
    (comp (ref "D286")
      (value "D664")
      (footprint "eagle-import:DO35-10")
      (libsource (lib "eagle-import") (part "1N4148DO35-10"))
    )
    (comp (ref "D287")
      (value "D664")
      (footprint "eagle-import:DO35-10")
      (libsource (lib "eagle-import") (part "1N4148DO35-10"))
    )
    (comp (ref "D288")
      (value "D664")
      (footprint "eagle-import:DO35-10")
      (libsource (lib "eagle-import") (part "1N4148DO35-10"))
    )
    (comp (ref "D289")
      (value "D664")
      (footprint "eagle-import:DO35-10")
      (libsource (lib "eagle-import") (part "1N4148DO35-10"))
    )
    (comp (ref "D290")
      (value "D664")
      (footprint "eagle-import:DO35-10")
      (libsource (lib "eagle-import") (part "1N4148DO35-10"))
    )
    (comp (ref "D291")
      (value "D664")
      (footprint "eagle-import:DO35-10")
      (libsource (lib "eagle-import") (part "1N4148DO35-10"))
    )
    (comp (ref "D292")
      (value "D664")
      (footprint "eagle-import:DO35-10")
      (libsource (lib "eagle-import") (part "1N4148DO35-10"))
    )
    (comp (ref "D293")
      (value "D664")
      (footprint "eagle-import:DO35-10")
      (libsource (lib "eagle-import") (part "1N4148DO35-10"))
    )
    (comp (ref "D294")
      (value "D664")
      (footprint "eagle-import:DO35-10")
      (libsource (lib "eagle-import") (part "1N4148DO35-10"))
    )
    (comp (ref "D295")
      (value "D664")
      (footprint "eagle-import:DO35-10")
      (libsource (lib "eagle-import") (part "1N4148DO35-10"))
    )
    (comp (ref "D296")
      (value "D664")
      (footprint "eagle-import:DO35-10")
      (libsource (lib "eagle-import") (part "1N4148DO35-10"))
    )
    (comp (ref "D297")
      (value "D664")
      (footprint "eagle-import:DO35-10")
      (libsource (lib "eagle-import") (part "1N4148DO35-10"))
    )
    (comp (ref "D298")
      (value "D664")
      (footprint "eagle-import:DO35-10")
      (libsource (lib "eagle-import") (part "1N4148DO35-10"))
    )
    (comp (ref "D299")
      (value "D664")
      (footprint "eagle-import:DO35-10")
      (libsource (lib "eagle-import") (part "1N4148DO35-10"))
    )
    (comp (ref "D300")
      (value "D664")
      (footprint "eagle-import:DO35-10")
      (libsource (lib "eagle-import") (part "1N4148DO35-10"))
    )
    (comp (ref "D301")
      (value "D664")
      (footprint "eagle-import:DO35-10")
      (libsource (lib "eagle-import") (part "1N4148DO35-10"))
    )
    (comp (ref "D302")
      (value "D664")
      (footprint "eagle-import:DO35-10")
      (libsource (lib "eagle-import") (part "1N4148DO35-10"))
    )
    (comp (ref "D303")
      (value "D664")
      (footprint "eagle-import:DO35-10")
      (libsource (lib "eagle-import") (part "1N4148DO35-10"))
    )
    (comp (ref "D304")
      (value "D664")
      (footprint "eagle-import:DO35-10")
      (libsource (lib "eagle-import") (part "1N4148DO35-10"))
    )
    (comp (ref "D305")
      (value "D664")
      (footprint "eagle-import:DO35-10")
      (libsource (lib "eagle-import") (part "1N4148DO35-10"))
    )
    (comp (ref "D306")
      (value "D664")
      (footprint "eagle-import:DO35-10")
      (libsource (lib "eagle-import") (part "1N4148DO35-10"))
    )
    (comp (ref "D307")
      (value "D664")
      (footprint "eagle-import:DO35-10")
      (libsource (lib "eagle-import") (part "1N4148DO35-10"))
    )
    (comp (ref "D308")
      (value "D664")
      (footprint "eagle-import:DO35-10")
      (libsource (lib "eagle-import") (part "1N4148DO35-10"))
    )
    (comp (ref "D309")
      (value "D664")
      (footprint "eagle-import:DO35-10")
      (libsource (lib "eagle-import") (part "1N4148DO35-10"))
    )
    (comp (ref "D310")
      (value "D664")
      (footprint "eagle-import:DO35-10")
      (libsource (lib "eagle-import") (part "1N4148DO35-10"))
    )
    (comp (ref "D311")
      (value "D664")
      (footprint "eagle-import:DO35-10")
      (libsource (lib "eagle-import") (part "1N4148DO35-10"))
    )
    (comp (ref "D312")
      (value "D664")
      (footprint "eagle-import:DO35-10")
      (libsource (lib "eagle-import") (part "1N4148DO35-10"))
    )
    (comp (ref "D313")
      (value "D664")
      (footprint "eagle-import:DO35-10")
      (libsource (lib "eagle-import") (part "1N4148DO35-10"))
    )
    (comp (ref "D314")
      (value "D664")
      (footprint "eagle-import:DO35-10")
      (libsource (lib "eagle-import") (part "1N4148DO35-10"))
    )
    (comp (ref "D315")
      (value "D664")
      (footprint "eagle-import:DO35-10")
      (libsource (lib "eagle-import") (part "1N4148DO35-10"))
    )
    (comp (ref "D316")
      (value "D664")
      (footprint "eagle-import:DO35-10")
      (libsource (lib "eagle-import") (part "1N4148DO35-10"))
    )
    (comp (ref "D317")
      (value "D664")
      (footprint "eagle-import:DO35-10")
      (libsource (lib "eagle-import") (part "1N4148DO35-10"))
    )
    (comp (ref "D318")
      (value "D664")
      (footprint "eagle-import:DO35-10")
      (libsource (lib "eagle-import") (part "1N4148DO35-10"))
    )
    (comp (ref "D319")
      (value "D664")
      (footprint "eagle-import:DO35-10")
      (libsource (lib "eagle-import") (part "1N4148DO35-10"))
    )
    (comp (ref "D320")
      (value "D664")
      (footprint "eagle-import:DO35-10")
      (libsource (lib "eagle-import") (part "1N4148DO35-10"))
    )
    (comp (ref "D321")
      (value "D664")
      (footprint "eagle-import:DO35-10")
      (libsource (lib "eagle-import") (part "1N4148DO35-10"))
    )
    (comp (ref "D322")
      (value "D664")
      (footprint "eagle-import:DO35-10")
      (libsource (lib "eagle-import") (part "1N4148DO35-10"))
    )
    (comp (ref "D323")
      (value "D664")
      (footprint "eagle-import:DO35-10")
      (libsource (lib "eagle-import") (part "1N4148DO35-10"))
    )
    (comp (ref "D324")
      (value "D664")
      (footprint "eagle-import:DO35-10")
      (libsource (lib "eagle-import") (part "1N4148DO35-10"))
    )
    (comp (ref "D325")
      (value "D664")
      (footprint "eagle-import:DO35-10")
      (libsource (lib "eagle-import") (part "1N4148DO35-10"))
    )
    (comp (ref "D326")
      (value "D664")
      (footprint "eagle-import:DO35-10")
      (libsource (lib "eagle-import") (part "1N4148DO35-10"))
    )
    (comp (ref "D327")
      (value "D664")
      (footprint "eagle-import:DO35-10")
      (libsource (lib "eagle-import") (part "1N4148DO35-10"))
    )
    (comp (ref "D328")
      (value "D664")
      (footprint "eagle-import:DO35-10")
      (libsource (lib "eagle-import") (part "1N4148DO35-10"))
    )
    (comp (ref "D329")
      (value "D664")
      (footprint "eagle-import:DO35-10")
      (libsource (lib "eagle-import") (part "1N4148DO35-10"))
    )
    (comp (ref "D330")
      (value "D664")
      (footprint "eagle-import:DO35-10")
      (libsource (lib "eagle-import") (part "1N4148DO35-10"))
    )
    (comp (ref "D331")
      (value "D664")
      (footprint "eagle-import:DO35-10")
      (libsource (lib "eagle-import") (part "1N4148DO35-10"))
    )
    (comp (ref "D332")
      (value "D664")
      (footprint "eagle-import:DO35-10")
      (libsource (lib "eagle-import") (part "1N4148DO35-10"))
    )
    (comp (ref "D333")
      (value "D664")
      (footprint "eagle-import:DO35-10")
      (libsource (lib "eagle-import") (part "1N4148DO35-10"))
    )
    (comp (ref "D334")
      (value "D664")
      (footprint "eagle-import:DO35-10")
      (libsource (lib "eagle-import") (part "1N4148DO35-10"))
    )
    (comp (ref "D335")
      (value "D664")
      (footprint "eagle-import:DO35-10")
      (libsource (lib "eagle-import") (part "1N4148DO35-10"))
    )
    (comp (ref "D336")
      (value "D664")
      (footprint "eagle-import:DO35-10")
      (libsource (lib "eagle-import") (part "1N4148DO35-10"))
    )
    (comp (ref "D337")
      (value "D664")
      (footprint "eagle-import:DO35-10")
      (libsource (lib "eagle-import") (part "1N4148DO35-10"))
    )
    (comp (ref "D338")
      (value "D664")
      (footprint "eagle-import:DO35-10")
      (libsource (lib "eagle-import") (part "1N4148DO35-10"))
    )
    (comp (ref "D339")
      (value "D664")
      (footprint "eagle-import:DO35-10")
      (libsource (lib "eagle-import") (part "1N4148DO35-10"))
    )
    (comp (ref "D340")
      (value "D664")
      (footprint "eagle-import:DO35-10")
      (libsource (lib "eagle-import") (part "1N4148DO35-10"))
    )
    (comp (ref "D341")
      (value "D664")
      (footprint "eagle-import:DO35-10")
      (libsource (lib "eagle-import") (part "1N4148DO35-10"))
    )
    (comp (ref "D342")
      (value "D664")
      (footprint "eagle-import:DO35-10")
      (libsource (lib "eagle-import") (part "1N4148DO35-10"))
    )
    (comp (ref "D343")
      (value "D664")
      (footprint "eagle-import:DO35-10")
      (libsource (lib "eagle-import") (part "1N4148DO35-10"))
    )
    (comp (ref "D344")
      (value "D664")
      (footprint "eagle-import:DO35-10")
      (libsource (lib "eagle-import") (part "1N4148DO35-10"))
    )
    (comp (ref "D345")
      (value "D664")
      (footprint "eagle-import:DO35-10")
      (libsource (lib "eagle-import") (part "1N4148DO35-10"))
    )
    (comp (ref "D346")
      (value "D664")
      (footprint "eagle-import:DO35-10")
      (libsource (lib "eagle-import") (part "1N4148DO35-10"))
    )
    (comp (ref "D347")
      (value "D664")
      (footprint "eagle-import:DO35-10")
      (libsource (lib "eagle-import") (part "1N4148DO35-10"))
    )
    (comp (ref "D348")
      (value "D664")
      (footprint "eagle-import:DO35-10")
      (libsource (lib "eagle-import") (part "1N4148DO35-10"))
    )
    (comp (ref "D349")
      (value "D664")
      (footprint "eagle-import:DO35-10")
      (libsource (lib "eagle-import") (part "1N4148DO35-10"))
    )
    (comp (ref "D350")
      (value "D664")
      (footprint "eagle-import:DO35-10")
      (libsource (lib "eagle-import") (part "1N4148DO35-10"))
    )
    (comp (ref "D351")
      (value "D664")
      (footprint "eagle-import:DO35-10")
      (libsource (lib "eagle-import") (part "1N4148DO35-10"))
    )
    (comp (ref "D352")
      (value "D664")
      (footprint "eagle-import:DO35-10")
      (libsource (lib "eagle-import") (part "1N4148DO35-10"))
    )
    (comp (ref "D353")
      (value "D664")
      (footprint "eagle-import:DO35-10")
      (libsource (lib "eagle-import") (part "1N4148DO35-10"))
    )
    (comp (ref "D354")
      (value "D664")
      (footprint "eagle-import:DO35-10")
      (libsource (lib "eagle-import") (part "1N4148DO35-10"))
    )
    (comp (ref "D355")
      (value "D664")
      (footprint "eagle-import:DO35-10")
      (libsource (lib "eagle-import") (part "1N4148DO35-10"))
    )
    (comp (ref "D356")
      (value "D664")
      (footprint "eagle-import:DO35-10")
      (libsource (lib "eagle-import") (part "1N4148DO35-10"))
    )
    (comp (ref "D357")
      (value "D664")
      (footprint "eagle-import:DO35-10")
      (libsource (lib "eagle-import") (part "1N4148DO35-10"))
    )
    (comp (ref "D358")
      (value "D664")
      (footprint "eagle-import:DO35-10")
      (libsource (lib "eagle-import") (part "1N4148DO35-10"))
    )
    (comp (ref "D359")
      (value "D664")
      (footprint "eagle-import:DO35-10")
      (libsource (lib "eagle-import") (part "1N4148DO35-10"))
    )
    (comp (ref "D360")
      (value "D664")
      (footprint "eagle-import:DO35-10")
      (libsource (lib "eagle-import") (part "1N4148DO35-10"))
    )
    (comp (ref "D361")
      (value "D664")
      (footprint "eagle-import:DO35-10")
      (libsource (lib "eagle-import") (part "1N4148DO35-10"))
    )
    (comp (ref "D362")
      (value "D664")
      (footprint "eagle-import:DO35-10")
      (libsource (lib "eagle-import") (part "1N4148DO35-10"))
    )
    (comp (ref "D363")
      (value "D664")
      (footprint "eagle-import:DO35-10")
      (libsource (lib "eagle-import") (part "1N4148DO35-10"))
    )
    (comp (ref "D364")
      (value "D664")
      (footprint "eagle-import:DO35-10")
      (libsource (lib "eagle-import") (part "1N4148DO35-10"))
    )
    (comp (ref "D365")
      (value "D664")
      (footprint "eagle-import:DO35-10")
      (libsource (lib "eagle-import") (part "1N4148DO35-10"))
    )
    (comp (ref "D366")
      (value "D664")
      (footprint "eagle-import:DO35-10")
      (libsource (lib "eagle-import") (part "1N4148DO35-10"))
    )
    (comp (ref "D367")
      (value "D664")
      (footprint "eagle-import:DO35-10")
      (libsource (lib "eagle-import") (part "1N4148DO35-10"))
    )
    (comp (ref "D368")
      (value "D664")
      (footprint "eagle-import:DO35-10")
      (libsource (lib "eagle-import") (part "1N4148DO35-10"))
    )
    (comp (ref "D369")
      (value "D664")
      (footprint "eagle-import:DO35-10")
      (libsource (lib "eagle-import") (part "1N4148DO35-10"))
    )
    (comp (ref "D370")
      (value "D664")
      (footprint "eagle-import:DO35-10")
      (libsource (lib "eagle-import") (part "1N4148DO35-10"))
    )
    (comp (ref "D371")
      (value "D664")
      (footprint "eagle-import:DO35-10")
      (libsource (lib "eagle-import") (part "1N4148DO35-10"))
    )
    (comp (ref "D372")
      (value "D664")
      (footprint "eagle-import:DO35-10")
      (libsource (lib "eagle-import") (part "1N4148DO35-10"))
    )
    (comp (ref "D373")
      (value "D664")
      (footprint "eagle-import:DO35-10")
      (libsource (lib "eagle-import") (part "1N4148DO35-10"))
    )
    (comp (ref "D374")
      (value "D664")
      (footprint "eagle-import:DO35-10")
      (libsource (lib "eagle-import") (part "1N4148DO35-10"))
    )
    (comp (ref "D375")
      (value "D664")
      (footprint "eagle-import:DO35-10")
      (libsource (lib "eagle-import") (part "1N4148DO35-10"))
    )
    (comp (ref "D376")
      (value "D664")
      (footprint "eagle-import:DO35-10")
      (libsource (lib "eagle-import") (part "1N4148DO35-10"))
    )
    (comp (ref "D377")
      (value "D664")
      (footprint "eagle-import:DO35-10")
      (libsource (lib "eagle-import") (part "1N4148DO35-10"))
    )
    (comp (ref "D378")
      (value "D664")
      (footprint "eagle-import:DO35-10")
      (libsource (lib "eagle-import") (part "1N4148DO35-10"))
    )
    (comp (ref "D379")
      (value "D664")
      (footprint "eagle-import:DO35-10")
      (libsource (lib "eagle-import") (part "1N4148DO35-10"))
    )
    (comp (ref "D380")
      (value "D664")
      (footprint "eagle-import:DO35-10")
      (libsource (lib "eagle-import") (part "1N4148DO35-10"))
    )
    (comp (ref "D381")
      (value "D664")
      (footprint "eagle-import:DO35-10")
      (libsource (lib "eagle-import") (part "1N4148DO35-10"))
    )
    (comp (ref "D382")
      (value "D664")
      (footprint "eagle-import:DO35-10")
      (libsource (lib "eagle-import") (part "1N4148DO35-10"))
    )
    (comp (ref "D383")
      (value "D664")
      (footprint "eagle-import:DO35-10")
      (libsource (lib "eagle-import") (part "1N4148DO35-10"))
    )
    (comp (ref "D384")
      (value "D664")
      (footprint "eagle-import:DO35-10")
      (libsource (lib "eagle-import") (part "1N4148DO35-10"))
    )
    (comp (ref "D385")
      (value "D664")
      (footprint "eagle-import:DO35-10")
      (libsource (lib "eagle-import") (part "1N4148DO35-10"))
    )
    (comp (ref "D386")
      (value "D664")
      (footprint "eagle-import:DO35-10")
      (libsource (lib "eagle-import") (part "1N4148DO35-10"))
    )
    (comp (ref "E1")
      (value "SP384N")
      (footprint "eagle-import:DIL14")
      (libsource (lib "eagle-import") (part "SP384N"))
    )
    (comp (ref "E4")
      (value "N8881N")
      (footprint "eagle-import:DIL14")
      (libsource (lib "eagle-import") (part "N8881N"))
    )
    (comp (ref "E14")
      (value "N8881N")
      (footprint "eagle-import:DIL14")
      (libsource (lib "eagle-import") (part "N8881N"))
    )
    (comp (ref "E17")
      (value "SP384N")
      (footprint "eagle-import:DIL14")
      (libsource (lib "eagle-import") (part "SP384N"))
    )
    (comp (ref "E32")
      (value "N8881N")
      (footprint "eagle-import:DIL14")
      (libsource (lib "eagle-import") (part "N8881N"))
    )
    (comp (ref "E35")
      (value "SP384N")
      (footprint "eagle-import:DIL14")
      (libsource (lib "eagle-import") (part "SP384N"))
    )
    (comp (ref "R40")
      (value "5.6K")
      (footprint "eagle-import:0207_10")
      (libsource (lib "eagle-import") (part "R-US_0207/10"))
    )
    (comp (ref "R41")
      (value "5.6K")
      (footprint "eagle-import:0207_10")
      (libsource (lib "eagle-import") (part "R-US_0207/10"))
    )
    (comp (ref "R42")
      (value "5.6K")
      (footprint "eagle-import:0207_10")
      (libsource (lib "eagle-import") (part "R-US_0207/10"))
    )
    (comp (ref "R43")
      (value "5.6K")
      (footprint "eagle-import:0207_10")
      (libsource (lib "eagle-import") (part "R-US_0207/10"))
    )
    (comp (ref "R44")
      (value "5.6K")
      (footprint "eagle-import:0207_10")
      (libsource (lib "eagle-import") (part "R-US_0207/10"))
    )
    (comp (ref "R45")
      (value "5.6K")
      (footprint "eagle-import:0207_10")
      (libsource (lib "eagle-import") (part "R-US_0207/10"))
    )
    (comp (ref "R46")
      (value "5.6K")
      (footprint "eagle-import:0207_10")
      (libsource (lib "eagle-import") (part "R-US_0207/10"))
    )
    (comp (ref "R47")
      (value "5.6K")
      (footprint "eagle-import:0207_10")
      (libsource (lib "eagle-import") (part "R-US_0207/10"))
    )
    (comp (ref "R48")
      (value "5.6K")
      (footprint "eagle-import:0207_10")
      (libsource (lib "eagle-import") (part "R-US_0207/10"))
    )
    (comp (ref "R49")
      (value "5.6K")
      (footprint "eagle-import:0207_10")
      (libsource (lib "eagle-import") (part "R-US_0207/10"))
    )
    (comp (ref "R50")
      (value "5.6K")
      (footprint "eagle-import:0207_10")
      (libsource (lib "eagle-import") (part "R-US_0207/10"))
    )
    (comp (ref "R51")
      (value "5.6K")
      (footprint "eagle-import:0207_10")
      (libsource (lib "eagle-import") (part "R-US_0207/10"))
    )
    (comp (ref "R52")
      (value "470")
      (footprint "eagle-import:0207_10")
      (libsource (lib "eagle-import") (part "R-US_0207/10"))
    )
    (comp (ref "U$1")
      (value "OUTLINE-OMNIBUS")
      (footprint "eagle-import:OMNIBUS")
      (libsource (lib "eagle-import") (part "OUTLINE-OMNIBUS"))
    )
    (comp (ref "U$2")
      (value "QUAD")
      (footprint "eagle-import:EDGE-CON8")
      (libsource (lib "eagle-import") (part "QUAD"))
    )
    (comp (ref "C1")
      (value "27pf")
      (footprint "eagle-import:C050-025X075")
      (libsource (lib "eagle-import") (part "C-US050-025X075"))
    )
    (comp (ref "C2")
      (value "39uf")
      (footprint "eagle-import:E15-5")
      (libsource (lib "eagle-import") (part "CPOL-USE15-5AXIAL"))
    )
    (comp (ref "C3")
      (value "150pf")
      (footprint "eagle-import:C050-025X075")
      (libsource (lib "eagle-import") (part "C-US050-025X075"))
    )
    (comp (ref "C4")
      (value "68pf")
      (footprint "eagle-import:C050-025X075")
      (libsource (lib "eagle-import") (part "C-US050-025X075"))
    )
    (comp (ref "C5")
      (value "27pf")
      (footprint "eagle-import:C050-025X075")
      (libsource (lib "eagle-import") (part "C-US050-025X075"))
    )
    (comp (ref "C7")
      (value "2700pf")
      (footprint "eagle-import:C102-043X133")
      (libsource (lib "eagle-import") (part "C-US102-043X133"))
    )
    (comp (ref "C8")
      (value "6.8uf")
      (footprint "eagle-import:E15-5")
      (libsource (lib "eagle-import") (part "CPOL-USE15-5AXIAL"))
    )
    (comp (ref "C9")
      (value "6.8uf")
      (footprint "eagle-import:E15-5")
      (libsource (lib "eagle-import") (part "CPOL-USE15-5AXIAL"))
    )
    (comp (ref "C10")
      (value "6.8uf")
      (footprint "eagle-import:E15-5")
      (libsource (lib "eagle-import") (part "CPOL-USE15-5AXIAL"))
    )
    (comp (ref "C11")
      (value "6.8uf")
      (footprint "eagle-import:E15-5")
      (libsource (lib "eagle-import") (part "CPOL-USE15-5AXIAL"))
    )
    (comp (ref "C12")
      (value ".01uf")
      (footprint "eagle-import:C050-025X075")
      (libsource (lib "eagle-import") (part "C-US050-025X075"))
    )
    (comp (ref "C13")
      (value ".01uf")
      (footprint "eagle-import:C050-025X075")
      (libsource (lib "eagle-import") (part "C-US050-025X075"))
    )
    (comp (ref "C14")
      (value ".01uf")
      (footprint "eagle-import:C050-025X075")
      (libsource (lib "eagle-import") (part "C-US050-025X075"))
    )
    (comp (ref "C15")
      (value ".01uf")
      (footprint "eagle-import:C050-025X075")
      (libsource (lib "eagle-import") (part "C-US050-025X075"))
    )
    (comp (ref "C16")
      (value ".01uf")
      (footprint "eagle-import:C050-025X075")
      (libsource (lib "eagle-import") (part "C-US050-025X075"))
    )
    (comp (ref "C17")
      (value ".01uf")
      (footprint "eagle-import:C050-025X075")
      (libsource (lib "eagle-import") (part "C-US050-025X075"))
    )
    (comp (ref "C18")
      (value ".01uf")
      (footprint "eagle-import:C050-025X075")
      (libsource (lib "eagle-import") (part "C-US050-025X075"))
    )
    (comp (ref "C19")
      (value ".01uf")
      (footprint "eagle-import:C050-025X075")
      (libsource (lib "eagle-import") (part "C-US050-025X075"))
    )
    (comp (ref "C20")
      (value ".01uf")
      (footprint "eagle-import:C050-025X075")
      (libsource (lib "eagle-import") (part "C-US050-025X075"))
    )
    (comp (ref "C21")
      (value ".01uf")
      (footprint "eagle-import:C050-025X075")
      (libsource (lib "eagle-import") (part "C-US050-025X075"))
    )
    (comp (ref "C22")
      (value ".01uf")
      (footprint "eagle-import:C050-025X075")
      (libsource (lib "eagle-import") (part "C-US050-025X075"))
    )
    (comp (ref "C23")
      (value ".01uf")
      (footprint "eagle-import:C050-025X075")
      (libsource (lib "eagle-import") (part "C-US050-025X075"))
    )
    (comp (ref "C24")
      (value ".01uf")
      (footprint "eagle-import:C050-025X075")
      (libsource (lib "eagle-import") (part "C-US050-025X075"))
    )
    (comp (ref "C25")
      (value ".01uf")
      (footprint "eagle-import:C050-025X075")
      (libsource (lib "eagle-import") (part "C-US050-025X075"))
    )
    (comp (ref "C26")
      (value ".01uf")
      (footprint "eagle-import:C050-025X075")
      (libsource (lib "eagle-import") (part "C-US050-025X075"))
    )
    (comp (ref "C27")
      (value ".01uf")
      (footprint "eagle-import:C050-025X075")
      (libsource (lib "eagle-import") (part "C-US050-025X075"))
    )
    (comp (ref "C28")
      (value ".01uf")
      (footprint "eagle-import:C050-025X075")
      (libsource (lib "eagle-import") (part "C-US050-025X075"))
    )
    (comp (ref "C29")
      (value ".01uf")
      (footprint "eagle-import:C050-025X075")
      (libsource (lib "eagle-import") (part "C-US050-025X075"))
    )
    (comp (ref "C30")
      (value ".01uf")
      (footprint "eagle-import:C050-025X075")
      (libsource (lib "eagle-import") (part "C-US050-025X075"))
    )
    (comp (ref "C31")
      (value ".01uf")
      (footprint "eagle-import:C050-025X075")
      (libsource (lib "eagle-import") (part "C-US050-025X075"))
    )
    (comp (ref "C32")
      (value ".01uf")
      (footprint "eagle-import:C050-025X075")
      (libsource (lib "eagle-import") (part "C-US050-025X075"))
    )
    (comp (ref "C33")
      (value ".01uf")
      (footprint "eagle-import:C050-025X075")
      (libsource (lib "eagle-import") (part "C-US050-025X075"))
    )
    (comp (ref "C34")
      (value ".01uf")
      (footprint "eagle-import:C050-025X075")
      (libsource (lib "eagle-import") (part "C-US050-025X075"))
    )
    (comp (ref "C35")
      (value ".01uf")
      (footprint "eagle-import:C050-025X075")
      (libsource (lib "eagle-import") (part "C-US050-025X075"))
    )
    (comp (ref "C36")
      (value ".01uf")
      (footprint "eagle-import:C050-025X075")
      (libsource (lib "eagle-import") (part "C-US050-025X075"))
    )
    (comp (ref "C37")
      (value ".01uf")
      (footprint "eagle-import:C050-025X075")
      (libsource (lib "eagle-import") (part "C-US050-025X075"))
    )
    (comp (ref "C38")
      (value ".01uf")
      (footprint "eagle-import:C050-025X075")
      (libsource (lib "eagle-import") (part "C-US050-025X075"))
    )
    (comp (ref "C39")
      (value ".01uf")
      (footprint "eagle-import:C050-025X075")
      (libsource (lib "eagle-import") (part "C-US050-025X075"))
    )
    (comp (ref "C40")
      (value ".01uf")
      (footprint "eagle-import:C050-025X075")
      (libsource (lib "eagle-import") (part "C-US050-025X075"))
    )
    (comp (ref "C41")
      (value ".01uf")
      (footprint "eagle-import:C050-025X075")
      (libsource (lib "eagle-import") (part "C-US050-025X075"))
    )
    (comp (ref "C42")
      (value ".01uf")
      (footprint "eagle-import:C050-025X075")
      (libsource (lib "eagle-import") (part "C-US050-025X075"))
    )
    (comp (ref "C43")
      (value ".01uf")
      (footprint "eagle-import:C050-025X075")
      (libsource (lib "eagle-import") (part "C-US050-025X075"))
    )
    (comp (ref "C44")
      (value ".01uf")
      (footprint "eagle-import:C050-025X075")
      (libsource (lib "eagle-import") (part "C-US050-025X075"))
    )
    (comp (ref "C45")
      (value ".01uf")
      (footprint "eagle-import:C050-025X075")
      (libsource (lib "eagle-import") (part "C-US050-025X075"))
    )
    (comp (ref "C46")
      (value ".01uf")
      (footprint "eagle-import:C050-025X075")
      (libsource (lib "eagle-import") (part "C-US050-025X075"))
    )
    (comp (ref "C47")
      (value ".01uf")
      (footprint "eagle-import:C050-025X075")
      (libsource (lib "eagle-import") (part "C-US050-025X075"))
    )
    (comp (ref "C48")
      (value ".01uf")
      (footprint "eagle-import:C050-025X075")
      (libsource (lib "eagle-import") (part "C-US050-025X075"))
    )
    (comp (ref "E2")
      (value "SP380N")
      (footprint "eagle-import:DIL14")
      (libsource (lib "eagle-import") (part "SP380N"))
    )
    (comp (ref "E5")
      (value "7400N")
      (footprint "eagle-import:DIL14")
      (libsource (lib "eagle-import") (part "7400N"))
    )
    (comp (ref "E10")
      (value "7404N")
      (footprint "eagle-import:DIL14")
      (libsource (lib "eagle-import") (part "7404N"))
    )
    (comp (ref "E12")
      (value "74S74N")
      (footprint "eagle-import:DIL14")
      (libsource (lib "eagle-import") (part "7474NS"))
    )
    (comp (ref "E13")
      (value "7400N")
      (footprint "eagle-import:DIL14")
      (libsource (lib "eagle-import") (part "7400N"))
    )
    (comp (ref "E15")
      (value "7402N")
      (footprint "eagle-import:DIL14")
      (libsource (lib "eagle-import") (part "7402N"))
    )
    (comp (ref "E16")
      (value "7402N")
      (footprint "eagle-import:DIL14")
      (libsource (lib "eagle-import") (part "7402N"))
    )
    (comp (ref "E18")
      (value "74S74N")
      (footprint "eagle-import:DIL14")
      (libsource (lib "eagle-import") (part "7474NS"))
    )
    (comp (ref "E19")
      (value "74123N")
      (footprint "eagle-import:DIL16")
      (libsource (lib "eagle-import") (part "74123N"))
    )
    (comp (ref "E20")
      (value "SP380N")
      (footprint "eagle-import:DIL14")
      (libsource (lib "eagle-import") (part "SP380N"))
    )
    (comp (ref "E22")
      (value "N8881N")
      (footprint "eagle-import:DIL14")
      (libsource (lib "eagle-import") (part "N8881N"))
    )
    (comp (ref "E23")
      (value "74S74N")
      (footprint "eagle-import:DIL14")
      (libsource (lib "eagle-import") (part "7474NS"))
    )
    (comp (ref "E24")
      (value "7404N")
      (footprint "eagle-import:DIL14")
      (libsource (lib "eagle-import") (part "7404N"))
    )
    (comp (ref "E27")
      (value "SP380N")
      (footprint "eagle-import:DIL14")
      (libsource (lib "eagle-import") (part "SP380N"))
    )
    (comp (ref "E33")
      (value "7402N")
      (footprint "eagle-import:DIL14")
      (libsource (lib "eagle-import") (part "7402N"))
    )
    (comp (ref "E36")
      (value "7400N")
      (footprint "eagle-import:DIL14")
      (libsource (lib "eagle-import") (part "7400N"))
    )
    (comp (ref "E37")
      (value "74123N")
      (footprint "eagle-import:DIL16")
      (libsource (lib "eagle-import") (part "74123N"))
    )
    (comp (ref "Q2")
      (value "DEC3009")
      (footprint "eagle-import:TO92")
      (libsource (lib "eagle-import") (part "-NPN-TO92"))
    )
    (comp (ref "R31")
      (value "10K")
      (footprint "eagle-import:0207_10")
      (libsource (lib "eagle-import") (part "R-US_0207/10"))
    )
    (comp (ref "R32")
      (value "1K")
      (footprint "eagle-import:0207_10")
      (libsource (lib "eagle-import") (part "R-US_0207/10"))
    )
    (comp (ref "R33")
      (value "3K")
      (footprint "eagle-import:0207_10")
      (libsource (lib "eagle-import") (part "R-US_0207/10"))
    )
    (comp (ref "R34")
      (value "22K")
      (footprint "eagle-import:0207_10")
      (libsource (lib "eagle-import") (part "R-US_0207/10"))
    )
    (comp (ref "R35")
      (value "15K")
      (footprint "eagle-import:0207_10")
      (libsource (lib "eagle-import") (part "R-US_0207/10"))
    )
    (comp (ref "R36")
      (value "20K")
      (footprint "eagle-import:0207_10")
      (libsource (lib "eagle-import") (part "R-US_0207/10"))
    )
    (comp (ref "R37")
      (value "10K")
      (footprint "eagle-import:0207_10")
      (libsource (lib "eagle-import") (part "R-US_0207/10"))
    )
    (comp (ref "R38")
      (value "100")
      (footprint "eagle-import:0207_10")
      (libsource (lib "eagle-import") (part "R-US_0207/10"))
    )
    (comp (ref "R39")
      (value "470")
      (footprint "eagle-import:0207_10")
      (libsource (lib "eagle-import") (part "R-US_0207/10"))
    )
    (comp (ref "R53")
      (value "470")
      (footprint "eagle-import:0207_10")
      (libsource (lib "eagle-import") (part "R-US_0207/10"))
    )
    (comp (ref "E3")
      (value "7404N")
      (footprint "eagle-import:DIL14")
      (libsource (lib "eagle-import") (part "7404N"))
    )
    (comp (ref "E6")
      (value "74164N")
      (footprint "eagle-import:DIL14")
      (libsource (lib "eagle-import") (part "74164N"))
    )
    (comp (ref "E7")
      (value "DEC8235")
      (footprint "eagle-import:DIL16")
      (libsource (lib "eagle-import") (part "DEC8235"))
    )
    (comp (ref "E8")
      (value "7404N")
      (footprint "eagle-import:DIL14")
      (libsource (lib "eagle-import") (part "7404N"))
    )
    (comp (ref "E9")
      (value "74164N")
      (footprint "eagle-import:DIL14")
      (libsource (lib "eagle-import") (part "74164N"))
    )
    (comp (ref "E11")
      (value "DEC8235")
      (footprint "eagle-import:DIL16")
      (libsource (lib "eagle-import") (part "DEC8235"))
    )
    (comp (ref "E21")
      (value "N8881N")
      (footprint "eagle-import:DIL14")
      (libsource (lib "eagle-import") (part "N8881N"))
    )
    (comp (ref "E25")
      (value "74164N")
      (footprint "eagle-import:DIL14")
      (libsource (lib "eagle-import") (part "74164N"))
    )
    (comp (ref "E26")
      (value "DEC8235")
      (footprint "eagle-import:DIL16")
      (libsource (lib "eagle-import") (part "DEC8235"))
    )
    (comp (ref "E28")
      (value "7404N")
      (footprint "eagle-import:DIL14")
      (libsource (lib "eagle-import") (part "7404N"))
    )
    (comp (ref "E29")
      (value "N8881N")
      (footprint "eagle-import:DIL14")
      (libsource (lib "eagle-import") (part "N8881N"))
    )
    (comp (ref "E30")
      (value "74S74N")
      (footprint "eagle-import:DIL14")
      (libsource (lib "eagle-import") (part "7474NS"))
    )
    (comp (ref "E31")
      (value "74164N")
      (footprint "eagle-import:DIL14")
      (libsource (lib "eagle-import") (part "74164N"))
    )
    (comp (ref "E34")
      (value "7404N")
      (footprint "eagle-import:DIL14")
      (libsource (lib "eagle-import") (part "7404N"))
    )
    (comp (ref "F0")
      (value "J15MM")
      (footprint "eagle-import:15")
      (libsource (lib "eagle-import") (part "J15MM"))
    )
    (comp (ref "F1")
      (value "J15MM")
      (footprint "eagle-import:15")
      (libsource (lib "eagle-import") (part "J15MM"))
    )
    (comp (ref "F2")
      (value "J15MM")
      (footprint "eagle-import:15")
      (libsource (lib "eagle-import") (part "J15MM"))
    )
    (comp (ref "I0")
      (value "J15MM")
      (footprint "eagle-import:15")
      (libsource (lib "eagle-import") (part "J15MM"))
    )
    (comp (ref "I1")
      (value "J15MM")
      (footprint "eagle-import:15")
      (libsource (lib "eagle-import") (part "J15MM"))
    )
    (comp (ref "I2")
      (value "J15MM")
      (footprint "eagle-import:15")
      (libsource (lib "eagle-import") (part "J15MM"))
    )
    (comp (ref "I3")
      (value "J15MM")
      (footprint "eagle-import:15")
      (libsource (lib "eagle-import") (part "J15MM"))
    )
    (comp (ref "I4")
      (value "J15MM")
      (footprint "eagle-import:15")
      (libsource (lib "eagle-import") (part "J15MM"))
    )
    (comp (ref "I5")
      (value "J15MM")
      (footprint "eagle-import:15")
      (libsource (lib "eagle-import") (part "J15MM"))
    )
    (comp (ref "I6")
      (value "J15MM")
      (footprint "eagle-import:15")
      (libsource (lib "eagle-import") (part "J15MM"))
    )
    (comp (ref "I7")
      (value "J15MM")
      (footprint "eagle-import:15")
      (libsource (lib "eagle-import") (part "J15MM"))
    )
    (comp (ref "I8")
      (value "J15MM")
      (footprint "eagle-import:15")
      (libsource (lib "eagle-import") (part "J15MM"))
    )
    (comp (ref "I9")
      (value "J15MM")
      (footprint "eagle-import:15")
      (libsource (lib "eagle-import") (part "J15MM"))
    )
    (comp (ref "I10")
      (value "J15MM")
      (footprint "eagle-import:15")
      (libsource (lib "eagle-import") (part "J15MM"))
    )
    (comp (ref "I11")
      (value "J15MM")
      (footprint "eagle-import:15")
      (libsource (lib "eagle-import") (part "J15MM"))
    )
    (comp (ref "Q1")
      (value "DEC3009")
      (footprint "eagle-import:TO92")
      (libsource (lib "eagle-import") (part "-NPN-TO92"))
    )
    (comp (ref "R1")
      (value "6.8K")
      (footprint "eagle-import:0207_10")
      (libsource (lib "eagle-import") (part "R-US_0207/10"))
    )
    (comp (ref "R2")
      (value "6.8K")
      (footprint "eagle-import:0207_10")
      (libsource (lib "eagle-import") (part "R-US_0207/10"))
    )
    (comp (ref "R3")
      (value "6.8K")
      (footprint "eagle-import:0207_10")
      (libsource (lib "eagle-import") (part "R-US_0207/10"))
    )
    (comp (ref "R4")
      (value "6.8K")
      (footprint "eagle-import:0207_10")
      (libsource (lib "eagle-import") (part "R-US_0207/10"))
    )
    (comp (ref "R5")
      (value "6.8K")
      (footprint "eagle-import:0207_10")
      (libsource (lib "eagle-import") (part "R-US_0207/10"))
    )
    (comp (ref "R6")
      (value "6.8K")
      (footprint "eagle-import:0207_10")
      (libsource (lib "eagle-import") (part "R-US_0207/10"))
    )
    (comp (ref "R7")
      (value "6.8K")
      (footprint "eagle-import:0207_10")
      (libsource (lib "eagle-import") (part "R-US_0207/10"))
    )
    (comp (ref "R8")
      (value "6.8K")
      (footprint "eagle-import:0207_10")
      (libsource (lib "eagle-import") (part "R-US_0207/10"))
    )
    (comp (ref "R9")
      (value "6.8K")
      (footprint "eagle-import:0207_10")
      (libsource (lib "eagle-import") (part "R-US_0207/10"))
    )
    (comp (ref "R10")
      (value "6.8K")
      (footprint "eagle-import:0207_10")
      (libsource (lib "eagle-import") (part "R-US_0207/10"))
    )
    (comp (ref "R11")
      (value "6.8K")
      (footprint "eagle-import:0207_10")
      (libsource (lib "eagle-import") (part "R-US_0207/10"))
    )
    (comp (ref "R12")
      (value "6.8K")
      (footprint "eagle-import:0207_10")
      (libsource (lib "eagle-import") (part "R-US_0207/10"))
    )
    (comp (ref "R13")
      (value "6.8K")
      (footprint "eagle-import:0207_10")
      (libsource (lib "eagle-import") (part "R-US_0207/10"))
    )
    (comp (ref "R14")
      (value "6.8K")
      (footprint "eagle-import:0207_10")
      (libsource (lib "eagle-import") (part "R-US_0207/10"))
    )
    (comp (ref "R15")
      (value "6.8K")
      (footprint "eagle-import:0207_10")
      (libsource (lib "eagle-import") (part "R-US_0207/10"))
    )
    (comp (ref "R16")
      (value "6.8K")
      (footprint "eagle-import:0207_10")
      (libsource (lib "eagle-import") (part "R-US_0207/10"))
    )
    (comp (ref "R17")
      (value "6.8K")
      (footprint "eagle-import:0207_10")
      (libsource (lib "eagle-import") (part "R-US_0207/10"))
    )
    (comp (ref "R18")
      (value "6.8K")
      (footprint "eagle-import:0207_10")
      (libsource (lib "eagle-import") (part "R-US_0207/10"))
    )
    (comp (ref "R19")
      (value "6.8K")
      (footprint "eagle-import:0207_10")
      (libsource (lib "eagle-import") (part "R-US_0207/10"))
    )
    (comp (ref "R20")
      (value "6.8K")
      (footprint "eagle-import:0207_10")
      (libsource (lib "eagle-import") (part "R-US_0207/10"))
    )
    (comp (ref "R21")
      (value "6.8K")
      (footprint "eagle-import:0207_10")
      (libsource (lib "eagle-import") (part "R-US_0207/10"))
    )
    (comp (ref "R22")
      (value "6.8K")
      (footprint "eagle-import:0207_10")
      (libsource (lib "eagle-import") (part "R-US_0207/10"))
    )
    (comp (ref "R23")
      (value "6.8K")
      (footprint "eagle-import:0207_10")
      (libsource (lib "eagle-import") (part "R-US_0207/10"))
    )
    (comp (ref "R24")
      (value "6.8K")
      (footprint "eagle-import:0207_10")
      (libsource (lib "eagle-import") (part "R-US_0207/10"))
    )
    (comp (ref "R25")
      (value "6.8K")
      (footprint "eagle-import:0207_10")
      (libsource (lib "eagle-import") (part "R-US_0207/10"))
    )
    (comp (ref "R26")
      (value "6.8K")
      (footprint "eagle-import:0207_10")
      (libsource (lib "eagle-import") (part "R-US_0207/10"))
    )
    (comp (ref "R27")
      (value "6.8K")
      (footprint "eagle-import:0207_10")
      (libsource (lib "eagle-import") (part "R-US_0207/10"))
    )
    (comp (ref "R28")
      (value "470")
      (footprint "eagle-import:0207_10")
      (libsource (lib "eagle-import") (part "R-US_0207/10"))
    )
    (comp (ref "R29")
      (value "27")
      (footprint "eagle-import:0207_10")
      (libsource (lib "eagle-import") (part "R-US_0207/10"))
    )
    (comp (ref "R30")
      (value "12")
      (footprint "eagle-import:0207_10")
      (libsource (lib "eagle-import") (part "R-US_0207/10"))
    )
    (comp (ref "S0")
      (value "J15MM")
      (footprint "eagle-import:15")
      (libsource (lib "eagle-import") (part "J15MM"))
    )
    (comp (ref "S1")
      (value "J15MM")
      (footprint "eagle-import:15")
      (libsource (lib "eagle-import") (part "J15MM"))
    )
    (comp (ref "S2")
      (value "J15MM")
      (footprint "eagle-import:15")
      (libsource (lib "eagle-import") (part "J15MM"))
    )
    (comp (ref "S3")
      (value "J15MM")
      (footprint "eagle-import:15")
      (libsource (lib "eagle-import") (part "J15MM"))
    )
    (comp (ref "S4")
      (value "J15MM")
      (footprint "eagle-import:15")
      (libsource (lib "eagle-import") (part "J15MM"))
    )
    (comp (ref "S5")
      (value "J15MM")
      (footprint "eagle-import:15")
      (libsource (lib "eagle-import") (part "J15MM"))
    )
    (comp (ref "S6")
      (value "J15MM")
      (footprint "eagle-import:15")
      (libsource (lib "eagle-import") (part "J15MM"))
    )
    (comp (ref "S7")
      (value "J15MM")
      (footprint "eagle-import:15")
      (libsource (lib "eagle-import") (part "J15MM"))
    )
    (comp (ref "S8")
      (value "J15MM")
      (footprint "eagle-import:15")
      (libsource (lib "eagle-import") (part "J15MM"))
    )
    (comp (ref "S9")
      (value "J15MM")
      (footprint "eagle-import:15")
      (libsource (lib "eagle-import") (part "J15MM"))
    )
    (comp (ref "S10")
      (value "J15MM")
      (footprint "eagle-import:15")
      (libsource (lib "eagle-import") (part "J15MM"))
    )
    (comp (ref "S11")
      (value "J15MM")
      (footprint "eagle-import:15")
      (libsource (lib "eagle-import") (part "J15MM"))
    )
  )
  (nets
    (net (code "1") (name "+3V3") (class "Default")
      (node (ref "C6") (pin "1") (pinfunction "1_1") (pintype "passive"))
      (node (ref "D386") (pin "C") (pinfunction "C_C") (pintype "passive"))
      (node (ref "E12") (pin "13") (pinfunction "CLR_13") (pintype "input"))
      (node (ref "E12") (pin "4") (pinfunction "PRE_4") (pintype "input"))
      (node (ref "E18") (pin "13") (pinfunction "CLR_13") (pintype "input"))
      (node (ref "E18") (pin "2") (pinfunction "D_2") (pintype "input"))
      (node (ref "E19") (pin "11") (pinfunction "CLR_11") (pintype "input"))
      (node (ref "E19") (pin "3") (pinfunction "CLR_3") (pintype "input"))
      (node (ref "E23") (pin "2") (pinfunction "D_2") (pintype "input"))
      (node (ref "E30") (pin "10") (pinfunction "PRE_10") (pintype "input"))
      (node (ref "E30") (pin "12") (pinfunction "D_12") (pintype "input"))
      (node (ref "E30") (pin "2") (pinfunction "D_2") (pintype "input"))
      (node (ref "E30") (pin "4") (pinfunction "PRE_4") (pintype "input"))
      (node (ref "E37") (pin "2") (pinfunction "B_2") (pintype "input"))
      (node (ref "E37") (pin "3") (pinfunction "CLR_3") (pintype "input"))
      (node (ref "I0") (pin "1") (pinfunction "1_1") (pintype "passive"))
      (node (ref "I1") (pin "1") (pinfunction "1_1") (pintype "passive"))
      (node (ref "I10") (pin "1") (pinfunction "1_1") (pintype "passive"))
      (node (ref "I11") (pin "1") (pinfunction "1_1") (pintype "passive"))
      (node (ref "I2") (pin "1") (pinfunction "1_1") (pintype "passive"))
      (node (ref "I3") (pin "1") (pinfunction "1_1") (pintype "passive"))
      (node (ref "I4") (pin "1") (pinfunction "1_1") (pintype "passive"))
      (node (ref "I5") (pin "1") (pinfunction "1_1") (pintype "passive"))
      (node (ref "I6") (pin "1") (pinfunction "1_1") (pintype "passive"))
      (node (ref "I7") (pin "1") (pinfunction "1_1") (pintype "passive"))
      (node (ref "I8") (pin "1") (pinfunction "1_1") (pintype "passive"))
      (node (ref "I9") (pin "1") (pinfunction "1_1") (pintype "passive"))
      (node (ref "R52") (pin "2") (pinfunction "2_2") (pintype "passive"))
    )
    (net (code "2") (name "-15V") (class "Default")
      (node (ref "C9") (pin "-") (pinfunction "-_-") (pintype "passive"))
      (node (ref "R10") (pin "1") (pinfunction "1_1") (pintype "passive"))
      (node (ref "R11") (pin "1") (pinfunction "1_1") (pintype "passive"))
      (node (ref "R16") (pin "1") (pinfunction "1_1") (pintype "passive"))
      (node (ref "R17") (pin "1") (pinfunction "1_1") (pintype "passive"))
      (node (ref "R18") (pin "1") (pinfunction "1_1") (pintype "passive"))
      (node (ref "R19") (pin "1") (pinfunction "1_1") (pintype "passive"))
      (node (ref "R24") (pin "1") (pinfunction "1_1") (pintype "passive"))
      (node (ref "R25") (pin "1") (pinfunction "1_1") (pintype "passive"))
      (node (ref "R26") (pin "1") (pinfunction "1_1") (pintype "passive"))
      (node (ref "R27") (pin "1") (pinfunction "1_1") (pintype "passive"))
      (node (ref "R8") (pin "1") (pinfunction "1_1") (pintype "passive"))
      (node (ref "R9") (pin "1") (pinfunction "1_1") (pintype "passive"))
      (node (ref "U$2") (pin "DB2") (pinfunction "1_DB2") (pintype "bidirectional"))
    )
    (net (code "3") (name "C01") (class "Default")
      (node (ref "D1") (pin "C") (pinfunction "C_C") (pintype "passive"))
      (node (ref "D10") (pin "C") (pinfunction "C_C") (pintype "passive"))
      (node (ref "D11") (pin "C") (pinfunction "C_C") (pintype "passive"))
      (node (ref "D12") (pin "C") (pinfunction "C_C") (pintype "passive"))
      (node (ref "D2") (pin "C") (pinfunction "C_C") (pintype "passive"))
      (node (ref "D3") (pin "C") (pinfunction "C_C") (pintype "passive"))
      (node (ref "D4") (pin "C") (pinfunction "C_C") (pintype "passive"))
      (node (ref "D5") (pin "C") (pinfunction "C_C") (pintype "passive"))
      (node (ref "D6") (pin "C") (pinfunction "C_C") (pintype "passive"))
      (node (ref "D7") (pin "C") (pinfunction "C_C") (pintype "passive"))
      (node (ref "D8") (pin "C") (pinfunction "C_C") (pintype "passive"))
      (node (ref "D9") (pin "C") (pinfunction "C_C") (pintype "passive"))
      (node (ref "E34") (pin "6") (pinfunction "O_6") (pintype "output"))
    )
    (net (code "4") (name "C02") (class "Default")
      (node (ref "D13") (pin "C") (pinfunction "C_C") (pintype "passive"))
      (node (ref "D14") (pin "C") (pinfunction "C_C") (pintype "passive"))
      (node (ref "D15") (pin "C") (pinfunction "C_C") (pintype "passive"))
      (node (ref "D16") (pin "C") (pinfunction "C_C") (pintype "passive"))
      (node (ref "D17") (pin "C") (pinfunction "C_C") (pintype "passive"))
      (node (ref "D18") (pin "C") (pinfunction "C_C") (pintype "passive"))
      (node (ref "D19") (pin "C") (pinfunction "C_C") (pintype "passive"))
      (node (ref "D20") (pin "C") (pinfunction "C_C") (pintype "passive"))
      (node (ref "D21") (pin "C") (pinfunction "C_C") (pintype "passive"))
      (node (ref "D22") (pin "C") (pinfunction "C_C") (pintype "passive"))
      (node (ref "D23") (pin "C") (pinfunction "C_C") (pintype "passive"))
      (node (ref "D24") (pin "C") (pinfunction "C_C") (pintype "passive"))
      (node (ref "E34") (pin "4") (pinfunction "O_4") (pintype "output"))
    )
    (net (code "5") (name "C03") (class "Default")
      (node (ref "D25") (pin "C") (pinfunction "C_C") (pintype "passive"))
      (node (ref "D26") (pin "C") (pinfunction "C_C") (pintype "passive"))
      (node (ref "D27") (pin "C") (pinfunction "C_C") (pintype "passive"))
      (node (ref "D28") (pin "C") (pinfunction "C_C") (pintype "passive"))
      (node (ref "D29") (pin "C") (pinfunction "C_C") (pintype "passive"))
      (node (ref "D30") (pin "C") (pinfunction "C_C") (pintype "passive"))
      (node (ref "D31") (pin "C") (pinfunction "C_C") (pintype "passive"))
      (node (ref "D32") (pin "C") (pinfunction "C_C") (pintype "passive"))
      (node (ref "D33") (pin "C") (pinfunction "C_C") (pintype "passive"))
      (node (ref "D34") (pin "C") (pinfunction "C_C") (pintype "passive"))
      (node (ref "D35") (pin "C") (pinfunction "C_C") (pintype "passive"))
      (node (ref "D36") (pin "C") (pinfunction "C_C") (pintype "passive"))
      (node (ref "E34") (pin "2") (pinfunction "O_2") (pintype "output"))
    )
    (net (code "6") (name "C04") (class "Default")
      (node (ref "D37") (pin "C") (pinfunction "C_C") (pintype "passive"))
      (node (ref "D38") (pin "C") (pinfunction "C_C") (pintype "passive"))
      (node (ref "D39") (pin "C") (pinfunction "C_C") (pintype "passive"))
      (node (ref "D40") (pin "C") (pinfunction "C_C") (pintype "passive"))
      (node (ref "D41") (pin "C") (pinfunction "C_C") (pintype "passive"))
      (node (ref "D42") (pin "C") (pinfunction "C_C") (pintype "passive"))
      (node (ref "D43") (pin "C") (pinfunction "C_C") (pintype "passive"))
      (node (ref "D44") (pin "C") (pinfunction "C_C") (pintype "passive"))
      (node (ref "D45") (pin "C") (pinfunction "C_C") (pintype "passive"))
      (node (ref "D46") (pin "C") (pinfunction "C_C") (pintype "passive"))
      (node (ref "D47") (pin "C") (pinfunction "C_C") (pintype "passive"))
      (node (ref "D48") (pin "C") (pinfunction "C_C") (pintype "passive"))
      (node (ref "E34") (pin "12") (pinfunction "O_12") (pintype "output"))
    )
    (net (code "7") (name "C05") (class "Default")
      (node (ref "D49") (pin "C") (pinfunction "C_C") (pintype "passive"))
      (node (ref "D50") (pin "C") (pinfunction "C_C") (pintype "passive"))
      (node (ref "D51") (pin "C") (pinfunction "C_C") (pintype "passive"))
      (node (ref "D52") (pin "C") (pinfunction "C_C") (pintype "passive"))
      (node (ref "D53") (pin "C") (pinfunction "C_C") (pintype "passive"))
      (node (ref "D54") (pin "C") (pinfunction "C_C") (pintype "passive"))
      (node (ref "D55") (pin "C") (pinfunction "C_C") (pintype "passive"))
      (node (ref "D56") (pin "C") (pinfunction "C_C") (pintype "passive"))
      (node (ref "D57") (pin "C") (pinfunction "C_C") (pintype "passive"))
      (node (ref "D58") (pin "C") (pinfunction "C_C") (pintype "passive"))
      (node (ref "D59") (pin "C") (pinfunction "C_C") (pintype "passive"))
      (node (ref "D60") (pin "C") (pinfunction "C_C") (pintype "passive"))
      (node (ref "E34") (pin "10") (pinfunction "O_10") (pintype "output"))
    )
    (net (code "8") (name "C06") (class "Default")
      (node (ref "D61") (pin "C") (pinfunction "C_C") (pintype "passive"))
      (node (ref "D62") (pin "C") (pinfunction "C_C") (pintype "passive"))
      (node (ref "D63") (pin "C") (pinfunction "C_C") (pintype "passive"))
      (node (ref "D64") (pin "C") (pinfunction "C_C") (pintype "passive"))
      (node (ref "D65") (pin "C") (pinfunction "C_C") (pintype "passive"))
      (node (ref "D66") (pin "C") (pinfunction "C_C") (pintype "passive"))
      (node (ref "D67") (pin "C") (pinfunction "C_C") (pintype "passive"))
      (node (ref "D68") (pin "C") (pinfunction "C_C") (pintype "passive"))
      (node (ref "D69") (pin "C") (pinfunction "C_C") (pintype "passive"))
      (node (ref "D70") (pin "C") (pinfunction "C_C") (pintype "passive"))
      (node (ref "D71") (pin "C") (pinfunction "C_C") (pintype "passive"))
      (node (ref "D72") (pin "C") (pinfunction "C_C") (pintype "passive"))
      (node (ref "E34") (pin "8") (pinfunction "O_8") (pintype "output"))
    )
    (net (code "9") (name "C07") (class "Default")
      (node (ref "D73") (pin "C") (pinfunction "C_C") (pintype "passive"))
      (node (ref "D74") (pin "C") (pinfunction "C_C") (pintype "passive"))
      (node (ref "D75") (pin "C") (pinfunction "C_C") (pintype "passive"))
      (node (ref "D76") (pin "C") (pinfunction "C_C") (pintype "passive"))
      (node (ref "D77") (pin "C") (pinfunction "C_C") (pintype "passive"))
      (node (ref "D78") (pin "C") (pinfunction "C_C") (pintype "passive"))
      (node (ref "D79") (pin "C") (pinfunction "C_C") (pintype "passive"))
      (node (ref "D80") (pin "C") (pinfunction "C_C") (pintype "passive"))
      (node (ref "D81") (pin "C") (pinfunction "C_C") (pintype "passive"))
      (node (ref "D82") (pin "C") (pinfunction "C_C") (pintype "passive"))
      (node (ref "D83") (pin "C") (pinfunction "C_C") (pintype "passive"))
      (node (ref "D84") (pin "C") (pinfunction "C_C") (pintype "passive"))
      (node (ref "E28") (pin "6") (pinfunction "O_6") (pintype "output"))
    )
    (net (code "10") (name "C08") (class "Default")
      (node (ref "D85") (pin "C") (pinfunction "C_C") (pintype "passive"))
      (node (ref "D86") (pin "C") (pinfunction "C_C") (pintype "passive"))
      (node (ref "D87") (pin "C") (pinfunction "C_C") (pintype "passive"))
      (node (ref "D88") (pin "C") (pinfunction "C_C") (pintype "passive"))
      (node (ref "D89") (pin "C") (pinfunction "C_C") (pintype "passive"))
      (node (ref "D90") (pin "C") (pinfunction "C_C") (pintype "passive"))
      (node (ref "D91") (pin "C") (pinfunction "C_C") (pintype "passive"))
      (node (ref "D92") (pin "C") (pinfunction "C_C") (pintype "passive"))
      (node (ref "D93") (pin "C") (pinfunction "C_C") (pintype "passive"))
      (node (ref "D94") (pin "C") (pinfunction "C_C") (pintype "passive"))
      (node (ref "D95") (pin "C") (pinfunction "C_C") (pintype "passive"))
      (node (ref "D96") (pin "C") (pinfunction "C_C") (pintype "passive"))
      (node (ref "E28") (pin "4") (pinfunction "O_4") (pintype "output"))
    )
    (net (code "11") (name "C09") (class "Default")
      (node (ref "D100") (pin "C") (pinfunction "C_C") (pintype "passive"))
      (node (ref "D101") (pin "C") (pinfunction "C_C") (pintype "passive"))
      (node (ref "D102") (pin "C") (pinfunction "C_C") (pintype "passive"))
      (node (ref "D103") (pin "C") (pinfunction "C_C") (pintype "passive"))
      (node (ref "D104") (pin "C") (pinfunction "C_C") (pintype "passive"))
      (node (ref "D105") (pin "C") (pinfunction "C_C") (pintype "passive"))
      (node (ref "D106") (pin "C") (pinfunction "C_C") (pintype "passive"))
      (node (ref "D107") (pin "C") (pinfunction "C_C") (pintype "passive"))
      (node (ref "D108") (pin "C") (pinfunction "C_C") (pintype "passive"))
      (node (ref "D97") (pin "C") (pinfunction "C_C") (pintype "passive"))
      (node (ref "D98") (pin "C") (pinfunction "C_C") (pintype "passive"))
      (node (ref "D99") (pin "C") (pinfunction "C_C") (pintype "passive"))
      (node (ref "E28") (pin "2") (pinfunction "O_2") (pintype "output"))
    )
    (net (code "12") (name "C10") (class "Default")
      (node (ref "D109") (pin "C") (pinfunction "C_C") (pintype "passive"))
      (node (ref "D110") (pin "C") (pinfunction "C_C") (pintype "passive"))
      (node (ref "D111") (pin "C") (pinfunction "C_C") (pintype "passive"))
      (node (ref "D112") (pin "C") (pinfunction "C_C") (pintype "passive"))
      (node (ref "D113") (pin "C") (pinfunction "C_C") (pintype "passive"))
      (node (ref "D114") (pin "C") (pinfunction "C_C") (pintype "passive"))
      (node (ref "D115") (pin "C") (pinfunction "C_C") (pintype "passive"))
      (node (ref "D116") (pin "C") (pinfunction "C_C") (pintype "passive"))
      (node (ref "D117") (pin "C") (pinfunction "C_C") (pintype "passive"))
      (node (ref "D118") (pin "C") (pinfunction "C_C") (pintype "passive"))
      (node (ref "D119") (pin "C") (pinfunction "C_C") (pintype "passive"))
      (node (ref "D120") (pin "C") (pinfunction "C_C") (pintype "passive"))
      (node (ref "E28") (pin "12") (pinfunction "O_12") (pintype "output"))
    )
    (net (code "13") (name "C11") (class "Default")
      (node (ref "D121") (pin "C") (pinfunction "C_C") (pintype "passive"))
      (node (ref "D122") (pin "C") (pinfunction "C_C") (pintype "passive"))
      (node (ref "D123") (pin "C") (pinfunction "C_C") (pintype "passive"))
      (node (ref "D124") (pin "C") (pinfunction "C_C") (pintype "passive"))
      (node (ref "D125") (pin "C") (pinfunction "C_C") (pintype "passive"))
      (node (ref "D126") (pin "C") (pinfunction "C_C") (pintype "passive"))
      (node (ref "D127") (pin "C") (pinfunction "C_C") (pintype "passive"))
      (node (ref "D128") (pin "C") (pinfunction "C_C") (pintype "passive"))
      (node (ref "D129") (pin "C") (pinfunction "C_C") (pintype "passive"))
      (node (ref "D130") (pin "C") (pinfunction "C_C") (pintype "passive"))
      (node (ref "D131") (pin "C") (pinfunction "C_C") (pintype "passive"))
      (node (ref "D132") (pin "C") (pinfunction "C_C") (pintype "passive"))
      (node (ref "E28") (pin "10") (pinfunction "O_10") (pintype "output"))
    )
    (net (code "14") (name "C12") (class "Default")
      (node (ref "D133") (pin "C") (pinfunction "C_C") (pintype "passive"))
      (node (ref "D134") (pin "C") (pinfunction "C_C") (pintype "passive"))
      (node (ref "D135") (pin "C") (pinfunction "C_C") (pintype "passive"))
      (node (ref "D136") (pin "C") (pinfunction "C_C") (pintype "passive"))
      (node (ref "D137") (pin "C") (pinfunction "C_C") (pintype "passive"))
      (node (ref "D138") (pin "C") (pinfunction "C_C") (pintype "passive"))
      (node (ref "D139") (pin "C") (pinfunction "C_C") (pintype "passive"))
      (node (ref "D140") (pin "C") (pinfunction "C_C") (pintype "passive"))
      (node (ref "D141") (pin "C") (pinfunction "C_C") (pintype "passive"))
      (node (ref "D142") (pin "C") (pinfunction "C_C") (pintype "passive"))
      (node (ref "D143") (pin "C") (pinfunction "C_C") (pintype "passive"))
      (node (ref "D144") (pin "C") (pinfunction "C_C") (pintype "passive"))
      (node (ref "E28") (pin "8") (pinfunction "O_8") (pintype "output"))
    )
    (net (code "15") (name "C13") (class "Default")
      (node (ref "D145") (pin "C") (pinfunction "C_C") (pintype "passive"))
      (node (ref "D146") (pin "C") (pinfunction "C_C") (pintype "passive"))
      (node (ref "D147") (pin "C") (pinfunction "C_C") (pintype "passive"))
      (node (ref "D148") (pin "C") (pinfunction "C_C") (pintype "passive"))
      (node (ref "D149") (pin "C") (pinfunction "C_C") (pintype "passive"))
      (node (ref "D150") (pin "C") (pinfunction "C_C") (pintype "passive"))
      (node (ref "D151") (pin "C") (pinfunction "C_C") (pintype "passive"))
      (node (ref "D152") (pin "C") (pinfunction "C_C") (pintype "passive"))
      (node (ref "D153") (pin "C") (pinfunction "C_C") (pintype "passive"))
      (node (ref "D154") (pin "C") (pinfunction "C_C") (pintype "passive"))
      (node (ref "D155") (pin "C") (pinfunction "C_C") (pintype "passive"))
      (node (ref "D156") (pin "C") (pinfunction "C_C") (pintype "passive"))
      (node (ref "E24") (pin "2") (pinfunction "O_2") (pintype "output"))
    )
    (net (code "16") (name "C14") (class "Default")
      (node (ref "D157") (pin "C") (pinfunction "C_C") (pintype "passive"))
      (node (ref "D158") (pin "C") (pinfunction "C_C") (pintype "passive"))
      (node (ref "D159") (pin "C") (pinfunction "C_C") (pintype "passive"))
      (node (ref "D160") (pin "C") (pinfunction "C_C") (pintype "passive"))
      (node (ref "D161") (pin "C") (pinfunction "C_C") (pintype "passive"))
      (node (ref "D162") (pin "C") (pinfunction "C_C") (pintype "passive"))
      (node (ref "D163") (pin "C") (pinfunction "C_C") (pintype "passive"))
      (node (ref "D164") (pin "C") (pinfunction "C_C") (pintype "passive"))
      (node (ref "D165") (pin "C") (pinfunction "C_C") (pintype "passive"))
      (node (ref "D166") (pin "C") (pinfunction "C_C") (pintype "passive"))
      (node (ref "D167") (pin "C") (pinfunction "C_C") (pintype "passive"))
      (node (ref "D168") (pin "C") (pinfunction "C_C") (pintype "passive"))
      (node (ref "E24") (pin "12") (pinfunction "O_12") (pintype "output"))
    )
    (net (code "17") (name "C15") (class "Default")
      (node (ref "D169") (pin "C") (pinfunction "C_C") (pintype "passive"))
      (node (ref "D170") (pin "C") (pinfunction "C_C") (pintype "passive"))
      (node (ref "D171") (pin "C") (pinfunction "C_C") (pintype "passive"))
      (node (ref "D172") (pin "C") (pinfunction "C_C") (pintype "passive"))
      (node (ref "D173") (pin "C") (pinfunction "C_C") (pintype "passive"))
      (node (ref "D174") (pin "C") (pinfunction "C_C") (pintype "passive"))
      (node (ref "D175") (pin "C") (pinfunction "C_C") (pintype "passive"))
      (node (ref "D176") (pin "C") (pinfunction "C_C") (pintype "passive"))
      (node (ref "D177") (pin "C") (pinfunction "C_C") (pintype "passive"))
      (node (ref "D178") (pin "C") (pinfunction "C_C") (pintype "passive"))
      (node (ref "D179") (pin "C") (pinfunction "C_C") (pintype "passive"))
      (node (ref "D180") (pin "C") (pinfunction "C_C") (pintype "passive"))
      (node (ref "E24") (pin "10") (pinfunction "O_10") (pintype "output"))
    )
    (net (code "18") (name "C16") (class "Default")
      (node (ref "D181") (pin "C") (pinfunction "C_C") (pintype "passive"))
      (node (ref "D182") (pin "C") (pinfunction "C_C") (pintype "passive"))
      (node (ref "D183") (pin "C") (pinfunction "C_C") (pintype "passive"))
      (node (ref "D184") (pin "C") (pinfunction "C_C") (pintype "passive"))
      (node (ref "D185") (pin "C") (pinfunction "C_C") (pintype "passive"))
      (node (ref "D186") (pin "C") (pinfunction "C_C") (pintype "passive"))
      (node (ref "D187") (pin "C") (pinfunction "C_C") (pintype "passive"))
      (node (ref "D188") (pin "C") (pinfunction "C_C") (pintype "passive"))
      (node (ref "D189") (pin "C") (pinfunction "C_C") (pintype "passive"))
      (node (ref "D190") (pin "C") (pinfunction "C_C") (pintype "passive"))
      (node (ref "D191") (pin "C") (pinfunction "C_C") (pintype "passive"))
      (node (ref "D192") (pin "C") (pinfunction "C_C") (pintype "passive"))
      (node (ref "E24") (pin "8") (pinfunction "O_8") (pintype "output"))
    )
    (net (code "19") (name "C17") (class "Default")
      (node (ref "D193") (pin "C") (pinfunction "C_C") (pintype "passive"))
      (node (ref "D194") (pin "C") (pinfunction "C_C") (pintype "passive"))
      (node (ref "D195") (pin "C") (pinfunction "C_C") (pintype "passive"))
      (node (ref "D196") (pin "C") (pinfunction "C_C") (pintype "passive"))
      (node (ref "D197") (pin "C") (pinfunction "C_C") (pintype "passive"))
      (node (ref "D198") (pin "C") (pinfunction "C_C") (pintype "passive"))
      (node (ref "D199") (pin "C") (pinfunction "C_C") (pintype "passive"))
      (node (ref "D200") (pin "C") (pinfunction "C_C") (pintype "passive"))
      (node (ref "D201") (pin "C") (pinfunction "C_C") (pintype "passive"))
      (node (ref "D202") (pin "C") (pinfunction "C_C") (pintype "passive"))
      (node (ref "D203") (pin "C") (pinfunction "C_C") (pintype "passive"))
      (node (ref "D204") (pin "C") (pinfunction "C_C") (pintype "passive"))
      (node (ref "E10") (pin "2") (pinfunction "O_2") (pintype "output"))
    )
    (net (code "20") (name "C18") (class "Default")
      (node (ref "D205") (pin "C") (pinfunction "C_C") (pintype "passive"))
      (node (ref "D206") (pin "C") (pinfunction "C_C") (pintype "passive"))
      (node (ref "D207") (pin "C") (pinfunction "C_C") (pintype "passive"))
      (node (ref "D208") (pin "C") (pinfunction "C_C") (pintype "passive"))
      (node (ref "D209") (pin "C") (pinfunction "C_C") (pintype "passive"))
      (node (ref "D210") (pin "C") (pinfunction "C_C") (pintype "passive"))
      (node (ref "D211") (pin "C") (pinfunction "C_C") (pintype "passive"))
      (node (ref "D212") (pin "C") (pinfunction "C_C") (pintype "passive"))
      (node (ref "D213") (pin "C") (pinfunction "C_C") (pintype "passive"))
      (node (ref "D214") (pin "C") (pinfunction "C_C") (pintype "passive"))
      (node (ref "D215") (pin "C") (pinfunction "C_C") (pintype "passive"))
      (node (ref "D216") (pin "C") (pinfunction "C_C") (pintype "passive"))
      (node (ref "E10") (pin "12") (pinfunction "O_12") (pintype "output"))
    )
    (net (code "21") (name "C19") (class "Default")
      (node (ref "D217") (pin "C") (pinfunction "C_C") (pintype "passive"))
      (node (ref "D218") (pin "C") (pinfunction "C_C") (pintype "passive"))
      (node (ref "D219") (pin "C") (pinfunction "C_C") (pintype "passive"))
      (node (ref "D220") (pin "C") (pinfunction "C_C") (pintype "passive"))
      (node (ref "D221") (pin "C") (pinfunction "C_C") (pintype "passive"))
      (node (ref "D222") (pin "C") (pinfunction "C_C") (pintype "passive"))
      (node (ref "D223") (pin "C") (pinfunction "C_C") (pintype "passive"))
      (node (ref "D224") (pin "C") (pinfunction "C_C") (pintype "passive"))
      (node (ref "D225") (pin "C") (pinfunction "C_C") (pintype "passive"))
      (node (ref "D226") (pin "C") (pinfunction "C_C") (pintype "passive"))
      (node (ref "D227") (pin "C") (pinfunction "C_C") (pintype "passive"))
      (node (ref "D228") (pin "C") (pinfunction "C_C") (pintype "passive"))
      (node (ref "E10") (pin "10") (pinfunction "O_10") (pintype "output"))
    )
    (net (code "22") (name "C20") (class "Default")
      (node (ref "D229") (pin "C") (pinfunction "C_C") (pintype "passive"))
      (node (ref "D230") (pin "C") (pinfunction "C_C") (pintype "passive"))
      (node (ref "D231") (pin "C") (pinfunction "C_C") (pintype "passive"))
      (node (ref "D232") (pin "C") (pinfunction "C_C") (pintype "passive"))
      (node (ref "D233") (pin "C") (pinfunction "C_C") (pintype "passive"))
      (node (ref "D234") (pin "C") (pinfunction "C_C") (pintype "passive"))
      (node (ref "D235") (pin "C") (pinfunction "C_C") (pintype "passive"))
      (node (ref "D236") (pin "C") (pinfunction "C_C") (pintype "passive"))
      (node (ref "D237") (pin "C") (pinfunction "C_C") (pintype "passive"))
      (node (ref "D238") (pin "C") (pinfunction "C_C") (pintype "passive"))
      (node (ref "D239") (pin "C") (pinfunction "C_C") (pintype "passive"))
      (node (ref "D240") (pin "C") (pinfunction "C_C") (pintype "passive"))
      (node (ref "E10") (pin "8") (pinfunction "O_8") (pintype "output"))
    )
    (net (code "23") (name "C21") (class "Default")
      (node (ref "D241") (pin "C") (pinfunction "C_C") (pintype "passive"))
      (node (ref "D242") (pin "C") (pinfunction "C_C") (pintype "passive"))
      (node (ref "D243") (pin "C") (pinfunction "C_C") (pintype "passive"))
      (node (ref "D244") (pin "C") (pinfunction "C_C") (pintype "passive"))
      (node (ref "D245") (pin "C") (pinfunction "C_C") (pintype "passive"))
      (node (ref "D246") (pin "C") (pinfunction "C_C") (pintype "passive"))
      (node (ref "D247") (pin "C") (pinfunction "C_C") (pintype "passive"))
      (node (ref "D248") (pin "C") (pinfunction "C_C") (pintype "passive"))
      (node (ref "D249") (pin "C") (pinfunction "C_C") (pintype "passive"))
      (node (ref "D250") (pin "C") (pinfunction "C_C") (pintype "passive"))
      (node (ref "D251") (pin "C") (pinfunction "C_C") (pintype "passive"))
      (node (ref "D252") (pin "C") (pinfunction "C_C") (pintype "passive"))
      (node (ref "E8") (pin "6") (pinfunction "O_6") (pintype "output"))
    )
    (net (code "24") (name "C22") (class "Default")
      (node (ref "D253") (pin "C") (pinfunction "C_C") (pintype "passive"))
      (node (ref "D254") (pin "C") (pinfunction "C_C") (pintype "passive"))
      (node (ref "D255") (pin "C") (pinfunction "C_C") (pintype "passive"))
      (node (ref "D256") (pin "C") (pinfunction "C_C") (pintype "passive"))
      (node (ref "D257") (pin "C") (pinfunction "C_C") (pintype "passive"))
      (node (ref "D258") (pin "C") (pinfunction "C_C") (pintype "passive"))
      (node (ref "D259") (pin "C") (pinfunction "C_C") (pintype "passive"))
      (node (ref "D260") (pin "C") (pinfunction "C_C") (pintype "passive"))
      (node (ref "D261") (pin "C") (pinfunction "C_C") (pintype "passive"))
      (node (ref "D262") (pin "C") (pinfunction "C_C") (pintype "passive"))
      (node (ref "D263") (pin "C") (pinfunction "C_C") (pintype "passive"))
      (node (ref "D264") (pin "C") (pinfunction "C_C") (pintype "passive"))
      (node (ref "E8") (pin "4") (pinfunction "O_4") (pintype "output"))
    )
    (net (code "25") (name "C23") (class "Default")
      (node (ref "D265") (pin "C") (pinfunction "C_C") (pintype "passive"))
      (node (ref "D266") (pin "C") (pinfunction "C_C") (pintype "passive"))
      (node (ref "D267") (pin "C") (pinfunction "C_C") (pintype "passive"))
      (node (ref "D268") (pin "C") (pinfunction "C_C") (pintype "passive"))
      (node (ref "D269") (pin "C") (pinfunction "C_C") (pintype "passive"))
      (node (ref "D270") (pin "C") (pinfunction "C_C") (pintype "passive"))
      (node (ref "D271") (pin "C") (pinfunction "C_C") (pintype "passive"))
      (node (ref "D272") (pin "C") (pinfunction "C_C") (pintype "passive"))
      (node (ref "D273") (pin "C") (pinfunction "C_C") (pintype "passive"))
      (node (ref "D274") (pin "C") (pinfunction "C_C") (pintype "passive"))
      (node (ref "D275") (pin "C") (pinfunction "C_C") (pintype "passive"))
      (node (ref "D276") (pin "C") (pinfunction "C_C") (pintype "passive"))
      (node (ref "E8") (pin "2") (pinfunction "O_2") (pintype "output"))
    )
    (net (code "26") (name "C24") (class "Default")
      (node (ref "D277") (pin "C") (pinfunction "C_C") (pintype "passive"))
      (node (ref "D278") (pin "C") (pinfunction "C_C") (pintype "passive"))
      (node (ref "D279") (pin "C") (pinfunction "C_C") (pintype "passive"))
      (node (ref "D280") (pin "C") (pinfunction "C_C") (pintype "passive"))
      (node (ref "D281") (pin "C") (pinfunction "C_C") (pintype "passive"))
      (node (ref "D282") (pin "C") (pinfunction "C_C") (pintype "passive"))
      (node (ref "D283") (pin "C") (pinfunction "C_C") (pintype "passive"))
      (node (ref "D284") (pin "C") (pinfunction "C_C") (pintype "passive"))
      (node (ref "D285") (pin "C") (pinfunction "C_C") (pintype "passive"))
      (node (ref "D286") (pin "C") (pinfunction "C_C") (pintype "passive"))
      (node (ref "D287") (pin "C") (pinfunction "C_C") (pintype "passive"))
      (node (ref "D288") (pin "C") (pinfunction "C_C") (pintype "passive"))
      (node (ref "E8") (pin "12") (pinfunction "O_12") (pintype "output"))
    )
    (net (code "27") (name "C25") (class "Default")
      (node (ref "D289") (pin "C") (pinfunction "C_C") (pintype "passive"))
      (node (ref "D290") (pin "C") (pinfunction "C_C") (pintype "passive"))
      (node (ref "D291") (pin "C") (pinfunction "C_C") (pintype "passive"))
      (node (ref "D292") (pin "C") (pinfunction "C_C") (pintype "passive"))
      (node (ref "D293") (pin "C") (pinfunction "C_C") (pintype "passive"))
      (node (ref "D294") (pin "C") (pinfunction "C_C") (pintype "passive"))
      (node (ref "D295") (pin "C") (pinfunction "C_C") (pintype "passive"))
      (node (ref "D296") (pin "C") (pinfunction "C_C") (pintype "passive"))
      (node (ref "D297") (pin "C") (pinfunction "C_C") (pintype "passive"))
      (node (ref "D298") (pin "C") (pinfunction "C_C") (pintype "passive"))
      (node (ref "D299") (pin "C") (pinfunction "C_C") (pintype "passive"))
      (node (ref "D300") (pin "C") (pinfunction "C_C") (pintype "passive"))
      (node (ref "E8") (pin "10") (pinfunction "O_10") (pintype "output"))
    )
    (net (code "28") (name "C26") (class "Default")
      (node (ref "D301") (pin "C") (pinfunction "C_C") (pintype "passive"))
      (node (ref "D302") (pin "C") (pinfunction "C_C") (pintype "passive"))
      (node (ref "D303") (pin "C") (pinfunction "C_C") (pintype "passive"))
      (node (ref "D304") (pin "C") (pinfunction "C_C") (pintype "passive"))
      (node (ref "D305") (pin "C") (pinfunction "C_C") (pintype "passive"))
      (node (ref "D306") (pin "C") (pinfunction "C_C") (pintype "passive"))
      (node (ref "D307") (pin "C") (pinfunction "C_C") (pintype "passive"))
      (node (ref "D308") (pin "C") (pinfunction "C_C") (pintype "passive"))
      (node (ref "D309") (pin "C") (pinfunction "C_C") (pintype "passive"))
      (node (ref "D310") (pin "C") (pinfunction "C_C") (pintype "passive"))
      (node (ref "D311") (pin "C") (pinfunction "C_C") (pintype "passive"))
      (node (ref "D312") (pin "C") (pinfunction "C_C") (pintype "passive"))
      (node (ref "E8") (pin "8") (pinfunction "O_8") (pintype "output"))
    )
    (net (code "29") (name "C27") (class "Default")
      (node (ref "D313") (pin "C") (pinfunction "C_C") (pintype "passive"))
      (node (ref "D314") (pin "C") (pinfunction "C_C") (pintype "passive"))
      (node (ref "D315") (pin "C") (pinfunction "C_C") (pintype "passive"))
      (node (ref "D316") (pin "C") (pinfunction "C_C") (pintype "passive"))
      (node (ref "D317") (pin "C") (pinfunction "C_C") (pintype "passive"))
      (node (ref "D318") (pin "C") (pinfunction "C_C") (pintype "passive"))
      (node (ref "D319") (pin "C") (pinfunction "C_C") (pintype "passive"))
      (node (ref "D320") (pin "C") (pinfunction "C_C") (pintype "passive"))
      (node (ref "D321") (pin "C") (pinfunction "C_C") (pintype "passive"))
      (node (ref "D322") (pin "C") (pinfunction "C_C") (pintype "passive"))
      (node (ref "D323") (pin "C") (pinfunction "C_C") (pintype "passive"))
      (node (ref "D324") (pin "C") (pinfunction "C_C") (pintype "passive"))
      (node (ref "E3") (pin "6") (pinfunction "O_6") (pintype "output"))
    )
    (net (code "30") (name "C28") (class "Default")
      (node (ref "D325") (pin "C") (pinfunction "C_C") (pintype "passive"))
      (node (ref "D326") (pin "C") (pinfunction "C_C") (pintype "passive"))
      (node (ref "D327") (pin "C") (pinfunction "C_C") (pintype "passive"))
      (node (ref "D328") (pin "C") (pinfunction "C_C") (pintype "passive"))
      (node (ref "D329") (pin "C") (pinfunction "C_C") (pintype "passive"))
      (node (ref "D330") (pin "C") (pinfunction "C_C") (pintype "passive"))
      (node (ref "D331") (pin "C") (pinfunction "C_C") (pintype "passive"))
      (node (ref "D332") (pin "C") (pinfunction "C_C") (pintype "passive"))
      (node (ref "D333") (pin "C") (pinfunction "C_C") (pintype "passive"))
      (node (ref "D334") (pin "C") (pinfunction "C_C") (pintype "passive"))
      (node (ref "D335") (pin "C") (pinfunction "C_C") (pintype "passive"))
      (node (ref "D336") (pin "C") (pinfunction "C_C") (pintype "passive"))
      (node (ref "E3") (pin "4") (pinfunction "O_4") (pintype "output"))
    )
    (net (code "31") (name "C29") (class "Default")
      (node (ref "D337") (pin "C") (pinfunction "C_C") (pintype "passive"))
      (node (ref "D338") (pin "C") (pinfunction "C_C") (pintype "passive"))
      (node (ref "D339") (pin "C") (pinfunction "C_C") (pintype "passive"))
      (node (ref "D340") (pin "C") (pinfunction "C_C") (pintype "passive"))
      (node (ref "D341") (pin "C") (pinfunction "C_C") (pintype "passive"))
      (node (ref "D342") (pin "C") (pinfunction "C_C") (pintype "passive"))
      (node (ref "D343") (pin "C") (pinfunction "C_C") (pintype "passive"))
      (node (ref "D344") (pin "C") (pinfunction "C_C") (pintype "passive"))
      (node (ref "D345") (pin "C") (pinfunction "C_C") (pintype "passive"))
      (node (ref "D346") (pin "C") (pinfunction "C_C") (pintype "passive"))
      (node (ref "D347") (pin "C") (pinfunction "C_C") (pintype "passive"))
      (node (ref "D348") (pin "C") (pinfunction "C_C") (pintype "passive"))
      (node (ref "E3") (pin "2") (pinfunction "O_2") (pintype "output"))
    )
    (net (code "32") (name "C30") (class "Default")
      (node (ref "D349") (pin "C") (pinfunction "C_C") (pintype "passive"))
      (node (ref "D350") (pin "C") (pinfunction "C_C") (pintype "passive"))
      (node (ref "D351") (pin "C") (pinfunction "C_C") (pintype "passive"))
      (node (ref "D352") (pin "C") (pinfunction "C_C") (pintype "passive"))
      (node (ref "D353") (pin "C") (pinfunction "C_C") (pintype "passive"))
      (node (ref "D354") (pin "C") (pinfunction "C_C") (pintype "passive"))
      (node (ref "D355") (pin "C") (pinfunction "C_C") (pintype "passive"))
      (node (ref "D356") (pin "C") (pinfunction "C_C") (pintype "passive"))
      (node (ref "D357") (pin "C") (pinfunction "C_C") (pintype "passive"))
      (node (ref "D358") (pin "C") (pinfunction "C_C") (pintype "passive"))
      (node (ref "D359") (pin "C") (pinfunction "C_C") (pintype "passive"))
      (node (ref "D360") (pin "C") (pinfunction "C_C") (pintype "passive"))
      (node (ref "E3") (pin "12") (pinfunction "O_12") (pintype "output"))
    )
    (net (code "33") (name "C31") (class "Default")
      (node (ref "D361") (pin "C") (pinfunction "C_C") (pintype "passive"))
      (node (ref "D362") (pin "C") (pinfunction "C_C") (pintype "passive"))
      (node (ref "D363") (pin "C") (pinfunction "C_C") (pintype "passive"))
      (node (ref "D364") (pin "C") (pinfunction "C_C") (pintype "passive"))
      (node (ref "D365") (pin "C") (pinfunction "C_C") (pintype "passive"))
      (node (ref "D366") (pin "C") (pinfunction "C_C") (pintype "passive"))
      (node (ref "D367") (pin "C") (pinfunction "C_C") (pintype "passive"))
      (node (ref "D368") (pin "C") (pinfunction "C_C") (pintype "passive"))
      (node (ref "D369") (pin "C") (pinfunction "C_C") (pintype "passive"))
      (node (ref "D370") (pin "C") (pinfunction "C_C") (pintype "passive"))
      (node (ref "D371") (pin "C") (pinfunction "C_C") (pintype "passive"))
      (node (ref "D372") (pin "C") (pinfunction "C_C") (pintype "passive"))
      (node (ref "E3") (pin "10") (pinfunction "O_10") (pintype "output"))
    )
    (net (code "34") (name "C32") (class "Default")
      (node (ref "D373") (pin "C") (pinfunction "C_C") (pintype "passive"))
      (node (ref "D374") (pin "C") (pinfunction "C_C") (pintype "passive"))
      (node (ref "D375") (pin "C") (pinfunction "C_C") (pintype "passive"))
      (node (ref "D376") (pin "C") (pinfunction "C_C") (pintype "passive"))
      (node (ref "D377") (pin "C") (pinfunction "C_C") (pintype "passive"))
      (node (ref "D378") (pin "C") (pinfunction "C_C") (pintype "passive"))
      (node (ref "D379") (pin "C") (pinfunction "C_C") (pintype "passive"))
      (node (ref "D380") (pin "C") (pinfunction "C_C") (pintype "passive"))
      (node (ref "D381") (pin "C") (pinfunction "C_C") (pintype "passive"))
      (node (ref "D382") (pin "C") (pinfunction "C_C") (pintype "passive"))
      (node (ref "D383") (pin "C") (pinfunction "C_C") (pintype "passive"))
      (node (ref "D384") (pin "C") (pinfunction "C_C") (pintype "passive"))
      (node (ref "E3") (pin "8") (pinfunction "O_8") (pintype "output"))
    )
    (net (code "35") (name "D4") (class "Default")
      (node (ref "E13") (pin "13") (pinfunction "I1_13") (pintype "input"))
      (node (ref "E22") (pin "2") (pinfunction "I0_2") (pintype "input"))
      (node (ref "E36") (pin "10") (pinfunction "I1_10") (pintype "input"))
      (node (ref "E37") (pin "13") (pinfunction "Q_13") (pintype "output"))
    )
    (net (code "36") (name "DATA_ENAB") (class "Default")
      (node (ref "E13") (pin "12") (pinfunction "I0_12") (pintype "input"))
      (node (ref "E14") (pin "12") (pinfunction "I1_12") (pintype "input"))
      (node (ref "E14") (pin "3") (pinfunction "I1_3") (pintype "input"))
      (node (ref "E14") (pin "6") (pinfunction "I1_6") (pintype "input"))
      (node (ref "E14") (pin "9") (pinfunction "I1_9") (pintype "input"))
      (node (ref "E22") (pin "3") (pinfunction "I1_3") (pintype "input"))
      (node (ref "E30") (pin "9") (pinfunction "Q_9") (pintype "output"))
      (node (ref "E32") (pin "12") (pinfunction "I1_12") (pintype "input"))
      (node (ref "E32") (pin "3") (pinfunction "I1_3") (pintype "input"))
      (node (ref "E32") (pin "6") (pinfunction "I1_6") (pintype "input"))
      (node (ref "E32") (pin "9") (pinfunction "I1_9") (pintype "input"))
      (node (ref "E33") (pin "12") (pinfunction "I1_12") (pintype "input"))
      (node (ref "E4") (pin "12") (pinfunction "I1_12") (pintype "input"))
      (node (ref "E4") (pin "3") (pinfunction "I1_3") (pintype "input"))
      (node (ref "E4") (pin "6") (pinfunction "I1_6") (pintype "input"))
      (node (ref "E4") (pin "9") (pinfunction "I1_9") (pintype "input"))
      (node (ref "U$2") (pin "AB1") (pinfunction "1_AB1") (pintype "bidirectional"))
    )
    (net (code "37") (name "FIELD2DATA") (class "Default")
      (node (ref "E21") (pin "2") (pinfunction "I0_2") (pintype "input"))
      (node (ref "E21") (pin "9") (pinfunction "I1_9") (pintype "input"))
      (node (ref "E29") (pin "12") (pinfunction "I1_12") (pintype "input"))
      (node (ref "E29") (pin "3") (pinfunction "I1_3") (pintype "input"))
      (node (ref "E29") (pin "6") (pinfunction "I1_6") (pintype "input"))
      (node (ref "E29") (pin "9") (pinfunction "I1_9") (pintype "input"))
      (node (ref "E33") (pin "4") (pinfunction "O_4") (pintype "output"))
    )
    (net (code "38") (name "GND") (class "Default")
      (node (ref "C10") (pin "-") (pinfunction "-_-") (pintype "passive"))
      (node (ref "C11") (pin "-") (pinfunction "-_-") (pintype "passive"))
      (node (ref "C12") (pin "2") (pinfunction "2_2") (pintype "passive"))
      (node (ref "C13") (pin "2") (pinfunction "2_2") (pintype "passive"))
      (node (ref "C14") (pin "2") (pinfunction "2_2") (pintype "passive"))
      (node (ref "C15") (pin "2") (pinfunction "2_2") (pintype "passive"))
      (node (ref "C16") (pin "2") (pinfunction "2_2") (pintype "passive"))
      (node (ref "C17") (pin "2") (pinfunction "2_2") (pintype "passive"))
      (node (ref "C18") (pin "2") (pinfunction "2_2") (pintype "passive"))
      (node (ref "C19") (pin "2") (pinfunction "2_2") (pintype "passive"))
      (node (ref "C20") (pin "2") (pinfunction "2_2") (pintype "passive"))
      (node (ref "C21") (pin "2") (pinfunction "2_2") (pintype "passive"))
      (node (ref "C22") (pin "2") (pinfunction "2_2") (pintype "passive"))
      (node (ref "C23") (pin "2") (pinfunction "2_2") (pintype "passive"))
      (node (ref "C24") (pin "2") (pinfunction "2_2") (pintype "passive"))
      (node (ref "C25") (pin "2") (pinfunction "2_2") (pintype "passive"))
      (node (ref "C26") (pin "2") (pinfunction "2_2") (pintype "passive"))
      (node (ref "C27") (pin "2") (pinfunction "2_2") (pintype "passive"))
      (node (ref "C28") (pin "2") (pinfunction "2_2") (pintype "passive"))
      (node (ref "C29") (pin "2") (pinfunction "2_2") (pintype "passive"))
      (node (ref "C30") (pin "2") (pinfunction "2_2") (pintype "passive"))
      (node (ref "C31") (pin "2") (pinfunction "2_2") (pintype "passive"))
      (node (ref "C32") (pin "2") (pinfunction "2_2") (pintype "passive"))
      (node (ref "C33") (pin "2") (pinfunction "2_2") (pintype "passive"))
      (node (ref "C34") (pin "2") (pinfunction "2_2") (pintype "passive"))
      (node (ref "C35") (pin "2") (pinfunction "2_2") (pintype "passive"))
      (node (ref "C36") (pin "2") (pinfunction "2_2") (pintype "passive"))
      (node (ref "C37") (pin "2") (pinfunction "2_2") (pintype "passive"))
      (node (ref "C38") (pin "2") (pinfunction "2_2") (pintype "passive"))
      (node (ref "C39") (pin "2") (pinfunction "2_2") (pintype "passive"))
      (node (ref "C40") (pin "2") (pinfunction "2_2") (pintype "passive"))
      (node (ref "C41") (pin "2") (pinfunction "2_2") (pintype "passive"))
      (node (ref "C42") (pin "2") (pinfunction "2_2") (pintype "passive"))
      (node (ref "C43") (pin "2") (pinfunction "2_2") (pintype "passive"))
      (node (ref "C44") (pin "2") (pinfunction "2_2") (pintype "passive"))
      (node (ref "C45") (pin "2") (pinfunction "2_2") (pintype "passive"))
      (node (ref "C46") (pin "2") (pinfunction "2_2") (pintype "passive"))
      (node (ref "C47") (pin "2") (pinfunction "2_2") (pintype "passive"))
      (node (ref "C48") (pin "2") (pinfunction "2_2") (pintype "passive"))
      (node (ref "C6") (pin "2") (pinfunction "2_2") (pintype "passive"))
      (node (ref "C7") (pin "2") (pinfunction "2_2") (pintype "passive"))
      (node (ref "C8") (pin "-") (pinfunction "-_-") (pintype "passive"))
      (node (ref "C9") (pin "+") (pinfunction "+_+") (pintype "passive"))
      (node (ref "E12") (pin "12") (pinfunction "D_12") (pintype "input"))
      (node (ref "E18") (pin "12") (pinfunction "D_12") (pintype "input"))
      (node (ref "E19") (pin "9") (pinfunction "A_9") (pintype "input"))
      (node (ref "E37") (pin "9") (pinfunction "A_9") (pintype "input"))
      (node (ref "F0") (pin "1") (pinfunction "1_1") (pintype "passive"))
      (node (ref "F1") (pin "1") (pinfunction "1_1") (pintype "passive"))
      (node (ref "F2") (pin "1") (pinfunction "1_1") (pintype "passive"))
      (node (ref "Q2") (pin "1") (pinfunction "E_1") (pintype "passive"))
      (node (ref "R52") (pin "1") (pinfunction "1_1") (pintype "passive"))
      (node (ref "S0") (pin "1") (pinfunction "1_1") (pintype "passive"))
      (node (ref "S1") (pin "1") (pinfunction "1_1") (pintype "passive"))
      (node (ref "S10") (pin "1") (pinfunction "1_1") (pintype "passive"))
      (node (ref "S11") (pin "1") (pinfunction "1_1") (pintype "passive"))
      (node (ref "S2") (pin "1") (pinfunction "1_1") (pintype "passive"))
      (node (ref "S3") (pin "1") (pinfunction "1_1") (pintype "passive"))
      (node (ref "S4") (pin "1") (pinfunction "1_1") (pintype "passive"))
      (node (ref "S5") (pin "1") (pinfunction "1_1") (pintype "passive"))
      (node (ref "S6") (pin "1") (pinfunction "1_1") (pintype "passive"))
      (node (ref "S7") (pin "1") (pinfunction "1_1") (pintype "passive"))
      (node (ref "S8") (pin "1") (pinfunction "1_1") (pintype "passive"))
      (node (ref "S9") (pin "1") (pinfunction "1_1") (pintype "passive"))
      (node (ref "U$2") (pin "AC2") (pinfunction "1_AC2") (pintype "bidirectional"))
      (node (ref "U$2") (pin "AF1") (pinfunction "1_AF1") (pintype "bidirectional"))
      (node (ref "U$2") (pin "AF2") (pinfunction "1_AF2") (pintype "bidirectional"))
      (node (ref "U$2") (pin "AN1") (pinfunction "1_AN1") (pintype "bidirectional"))
      (node (ref "U$2") (pin "AN2") (pinfunction "1_AN2") (pintype "bidirectional"))
      (node (ref "U$2") (pin "AT1") (pinfunction "1_AT1") (pintype "bidirectional"))
      (node (ref "U$2") (pin "AT2") (pinfunction "1_AT2") (pintype "bidirectional"))
      (node (ref "U$2") (pin "BC1") (pinfunction "1_BC1") (pintype "bidirectional"))
      (node (ref "U$2") (pin "BC2") (pinfunction "1_BC2") (pintype "bidirectional"))
      (node (ref "U$2") (pin "BF1") (pinfunction "1_BF1") (pintype "bidirectional"))
      (node (ref "U$2") (pin "BF2") (pinfunction "1_BF2") (pintype "bidirectional"))
      (node (ref "U$2") (pin "BN1") (pinfunction "1_BN1") (pintype "bidirectional"))
      (node (ref "U$2") (pin "BN2") (pinfunction "1_BN2") (pintype "bidirectional"))
      (node (ref "U$2") (pin "BT1") (pinfunction "1_BT1") (pintype "bidirectional"))
      (node (ref "U$2") (pin "CC1") (pinfunction "1_CC1") (pintype "bidirectional"))
      (node (ref "U$2") (pin "CC2") (pinfunction "1_CC2") (pintype "bidirectional"))
      (node (ref "U$2") (pin "CF2") (pinfunction "1_CF2") (pintype "bidirectional"))
      (node (ref "U$2") (pin "CN1") (pinfunction "1_CN1") (pintype "bidirectional"))
      (node (ref "U$2") (pin "CN2") (pinfunction "1_CN2") (pintype "bidirectional"))
      (node (ref "U$2") (pin "CT1") (pinfunction "1_CT1") (pintype "bidirectional"))
      (node (ref "U$2") (pin "CT2") (pinfunction "1_CT2") (pintype "bidirectional"))
      (node (ref "U$2") (pin "DC1") (pinfunction "1_DC1") (pintype "bidirectional"))
      (node (ref "U$2") (pin "DC2") (pinfunction "1_DC2") (pintype "bidirectional"))
      (node (ref "U$2") (pin "DF1") (pinfunction "1_DF1") (pintype "bidirectional"))
      (node (ref "U$2") (pin "DF2") (pinfunction "1_DF2") (pintype "bidirectional"))
      (node (ref "U$2") (pin "DN1") (pinfunction "1_DN1") (pintype "bidirectional"))
      (node (ref "U$2") (pin "DN2") (pinfunction "1_DN2") (pintype "bidirectional"))
      (node (ref "U$2") (pin "DT1") (pinfunction "1_DT1") (pintype "bidirectional"))
      (node (ref "U$2") (pin "DT2") (pinfunction "1_DT2") (pintype "bidirectional"))
    )
    (net (code "39") (name "INITIALIZE") (class "Default")
      (node (ref "E27") (pin "11") (pinfunction "I0_11") (pintype "input"))
      (node (ref "E27") (pin "12") (pinfunction "I1_12") (pintype "input"))
      (node (ref "U$2") (pin "CR1") (pinfunction "1_CR1") (pintype "bidirectional"))
    )
    (net (code "40") (name "LAST_WORD") (class "Default")
      (node (ref "E12") (pin "2") (pinfunction "D_2") (pintype "input"))
      (node (ref "E3") (pin "9") (pinfunction "I_9") (pintype "input"))
      (node (ref "E6") (pin "13") (pinfunction "QH_13") (pintype "output"))
    )
    (net (code "41") (name "LOAD_PULSE") (class "Default")
      (node (ref "E33") (pin "13") (pinfunction "O_13") (pintype "output"))
      (node (ref "E33") (pin "8") (pinfunction "I0_8") (pintype "input"))
      (node (ref "E36") (pin "1") (pinfunction "I0_1") (pintype "input"))
      (node (ref "E36") (pin "13") (pinfunction "I1_13") (pintype "input"))
      (node (ref "E36") (pin "2") (pinfunction "I1_2") (pintype "input"))
      (node (ref "R28") (pin "1") (pinfunction "1_1") (pintype "passive"))
      (node (ref "R29") (pin "1") (pinfunction "1_1") (pintype "passive"))
    )
    (net (code "42") (name "Net-(C2-Pad-)") (class "Default")
      (node (ref "C2") (pin "-") (pinfunction "-_-") (pintype "passive"))
      (node (ref "R32") (pin "1") (pinfunction "1_1") (pintype "passive"))
      (node (ref "R33") (pin "2") (pinfunction "2_2") (pintype "passive"))
    )
    (net (code "43") (name "Net-(D385-PadC)") (class "Default")
      (node (ref "D385") (pin "C") (pinfunction "C_C") (pintype "passive"))
      (node (ref "D386") (pin "A") (pinfunction "A_A") (pintype "passive"))
    )
    (net (code "44") (name "Net-(E1A-I0)") (class "Default")
      (node (ref "D111") (pin "A") (pinfunction "A_A") (pintype "passive"))
      (node (ref "D123") (pin "A") (pinfunction "A_A") (pintype "passive"))
      (node (ref "D135") (pin "A") (pinfunction "A_A") (pintype "passive"))
      (node (ref "D147") (pin "A") (pinfunction "A_A") (pintype "passive"))
      (node (ref "D15") (pin "A") (pinfunction "A_A") (pintype "passive"))
      (node (ref "D159") (pin "A") (pinfunction "A_A") (pintype "passive"))
      (node (ref "D171") (pin "A") (pinfunction "A_A") (pintype "passive"))
      (node (ref "D183") (pin "A") (pinfunction "A_A") (pintype "passive"))
      (node (ref "D195") (pin "A") (pinfunction "A_A") (pintype "passive"))
      (node (ref "D207") (pin "A") (pinfunction "A_A") (pintype "passive"))
      (node (ref "D219") (pin "A") (pinfunction "A_A") (pintype "passive"))
      (node (ref "D231") (pin "A") (pinfunction "A_A") (pintype "passive"))
      (node (ref "D243") (pin "A") (pinfunction "A_A") (pintype "passive"))
      (node (ref "D255") (pin "A") (pinfunction "A_A") (pintype "passive"))
      (node (ref "D267") (pin "A") (pinfunction "A_A") (pintype "passive"))
      (node (ref "D27") (pin "A") (pinfunction "A_A") (pintype "passive"))
      (node (ref "D279") (pin "A") (pinfunction "A_A") (pintype "passive"))
      (node (ref "D291") (pin "A") (pinfunction "A_A") (pintype "passive"))
      (node (ref "D3") (pin "A") (pinfunction "A_A") (pintype "passive"))
      (node (ref "D303") (pin "A") (pinfunction "A_A") (pintype "passive"))
      (node (ref "D315") (pin "A") (pinfunction "A_A") (pintype "passive"))
      (node (ref "D327") (pin "A") (pinfunction "A_A") (pintype "passive"))
      (node (ref "D339") (pin "A") (pinfunction "A_A") (pintype "passive"))
      (node (ref "D351") (pin "A") (pinfunction "A_A") (pintype "passive"))
      (node (ref "D363") (pin "A") (pinfunction "A_A") (pintype "passive"))
      (node (ref "D375") (pin "A") (pinfunction "A_A") (pintype "passive"))
      (node (ref "D39") (pin "A") (pinfunction "A_A") (pintype "passive"))
      (node (ref "D51") (pin "A") (pinfunction "A_A") (pintype "passive"))
      (node (ref "D63") (pin "A") (pinfunction "A_A") (pintype "passive"))
      (node (ref "D75") (pin "A") (pinfunction "A_A") (pintype "passive"))
      (node (ref "D87") (pin "A") (pinfunction "A_A") (pintype "passive"))
      (node (ref "D99") (pin "A") (pinfunction "A_A") (pintype "passive"))
      (node (ref "E1") (pin "4") (pinfunction "I0_4") (pintype "input"))
      (node (ref "E1") (pin "5") (pinfunction "I1_5") (pintype "input"))
      (node (ref "R42") (pin "2") (pinfunction "2_2") (pintype "passive"))
    )
    (net (code "45") (name "Net-(E1A-O)") (class "Default")
      (node (ref "E1") (pin "3") (pinfunction "O_3") (pintype "output"))
      (node (ref "E4") (pin "5") (pinfunction "I0_5") (pintype "input"))
    )
    (net (code "46") (name "Net-(E1B-I0)") (class "Default")
      (node (ref "D100") (pin "A") (pinfunction "A_A") (pintype "passive"))
      (node (ref "D112") (pin "A") (pinfunction "A_A") (pintype "passive"))
      (node (ref "D124") (pin "A") (pinfunction "A_A") (pintype "passive"))
      (node (ref "D136") (pin "A") (pinfunction "A_A") (pintype "passive"))
      (node (ref "D148") (pin "A") (pinfunction "A_A") (pintype "passive"))
      (node (ref "D16") (pin "A") (pinfunction "A_A") (pintype "passive"))
      (node (ref "D160") (pin "A") (pinfunction "A_A") (pintype "passive"))
      (node (ref "D172") (pin "A") (pinfunction "A_A") (pintype "passive"))
      (node (ref "D184") (pin "A") (pinfunction "A_A") (pintype "passive"))
      (node (ref "D196") (pin "A") (pinfunction "A_A") (pintype "passive"))
      (node (ref "D208") (pin "A") (pinfunction "A_A") (pintype "passive"))
      (node (ref "D220") (pin "A") (pinfunction "A_A") (pintype "passive"))
      (node (ref "D232") (pin "A") (pinfunction "A_A") (pintype "passive"))
      (node (ref "D244") (pin "A") (pinfunction "A_A") (pintype "passive"))
      (node (ref "D256") (pin "A") (pinfunction "A_A") (pintype "passive"))
      (node (ref "D268") (pin "A") (pinfunction "A_A") (pintype "passive"))
      (node (ref "D28") (pin "A") (pinfunction "A_A") (pintype "passive"))
      (node (ref "D280") (pin "A") (pinfunction "A_A") (pintype "passive"))
      (node (ref "D292") (pin "A") (pinfunction "A_A") (pintype "passive"))
      (node (ref "D304") (pin "A") (pinfunction "A_A") (pintype "passive"))
      (node (ref "D316") (pin "A") (pinfunction "A_A") (pintype "passive"))
      (node (ref "D328") (pin "A") (pinfunction "A_A") (pintype "passive"))
      (node (ref "D340") (pin "A") (pinfunction "A_A") (pintype "passive"))
      (node (ref "D352") (pin "A") (pinfunction "A_A") (pintype "passive"))
      (node (ref "D364") (pin "A") (pinfunction "A_A") (pintype "passive"))
      (node (ref "D376") (pin "A") (pinfunction "A_A") (pintype "passive"))
      (node (ref "D4") (pin "A") (pinfunction "A_A") (pintype "passive"))
      (node (ref "D40") (pin "A") (pinfunction "A_A") (pintype "passive"))
      (node (ref "D52") (pin "A") (pinfunction "A_A") (pintype "passive"))
      (node (ref "D64") (pin "A") (pinfunction "A_A") (pintype "passive"))
      (node (ref "D76") (pin "A") (pinfunction "A_A") (pintype "passive"))
      (node (ref "D88") (pin "A") (pinfunction "A_A") (pintype "passive"))
      (node (ref "E1") (pin "6") (pinfunction "I0_6") (pintype "input"))
      (node (ref "E1") (pin "7") (pinfunction "I1_7") (pintype "input"))
      (node (ref "R43") (pin "2") (pinfunction "2_2") (pintype "passive"))
    )
    (net (code "47") (name "Net-(E1B-O)") (class "Default")
      (node (ref "E1") (pin "2") (pinfunction "O_2") (pintype "output"))
      (node (ref "E4") (pin "2") (pinfunction "I0_2") (pintype "input"))
    )
    (net (code "48") (name "Net-(E1C-I0)") (class "Default")
      (node (ref "D110") (pin "A") (pinfunction "A_A") (pintype "passive"))
      (node (ref "D122") (pin "A") (pinfunction "A_A") (pintype "passive"))
      (node (ref "D134") (pin "A") (pinfunction "A_A") (pintype "passive"))
      (node (ref "D14") (pin "A") (pinfunction "A_A") (pintype "passive"))
      (node (ref "D146") (pin "A") (pinfunction "A_A") (pintype "passive"))
      (node (ref "D158") (pin "A") (pinfunction "A_A") (pintype "passive"))
      (node (ref "D170") (pin "A") (pinfunction "A_A") (pintype "passive"))
      (node (ref "D182") (pin "A") (pinfunction "A_A") (pintype "passive"))
      (node (ref "D194") (pin "A") (pinfunction "A_A") (pintype "passive"))
      (node (ref "D2") (pin "A") (pinfunction "A_A") (pintype "passive"))
      (node (ref "D206") (pin "A") (pinfunction "A_A") (pintype "passive"))
      (node (ref "D218") (pin "A") (pinfunction "A_A") (pintype "passive"))
      (node (ref "D230") (pin "A") (pinfunction "A_A") (pintype "passive"))
      (node (ref "D242") (pin "A") (pinfunction "A_A") (pintype "passive"))
      (node (ref "D254") (pin "A") (pinfunction "A_A") (pintype "passive"))
      (node (ref "D26") (pin "A") (pinfunction "A_A") (pintype "passive"))
      (node (ref "D266") (pin "A") (pinfunction "A_A") (pintype "passive"))
      (node (ref "D278") (pin "A") (pinfunction "A_A") (pintype "passive"))
      (node (ref "D290") (pin "A") (pinfunction "A_A") (pintype "passive"))
      (node (ref "D302") (pin "A") (pinfunction "A_A") (pintype "passive"))
      (node (ref "D314") (pin "A") (pinfunction "A_A") (pintype "passive"))
      (node (ref "D326") (pin "A") (pinfunction "A_A") (pintype "passive"))
      (node (ref "D338") (pin "A") (pinfunction "A_A") (pintype "passive"))
      (node (ref "D350") (pin "A") (pinfunction "A_A") (pintype "passive"))
      (node (ref "D362") (pin "A") (pinfunction "A_A") (pintype "passive"))
      (node (ref "D374") (pin "A") (pinfunction "A_A") (pintype "passive"))
      (node (ref "D38") (pin "A") (pinfunction "A_A") (pintype "passive"))
      (node (ref "D50") (pin "A") (pinfunction "A_A") (pintype "passive"))
      (node (ref "D62") (pin "A") (pinfunction "A_A") (pintype "passive"))
      (node (ref "D74") (pin "A") (pinfunction "A_A") (pintype "passive"))
      (node (ref "D86") (pin "A") (pinfunction "A_A") (pintype "passive"))
      (node (ref "D98") (pin "A") (pinfunction "A_A") (pintype "passive"))
      (node (ref "E1") (pin "10") (pinfunction "I1_10") (pintype "input"))
      (node (ref "E1") (pin "9") (pinfunction "I0_9") (pintype "input"))
      (node (ref "R41") (pin "2") (pinfunction "2_2") (pintype "passive"))
    )
    (net (code "49") (name "Net-(E1C-O)") (class "Default")
      (node (ref "E1") (pin "14") (pinfunction "O_14") (pintype "output"))
      (node (ref "E4") (pin "11") (pinfunction "I0_11") (pintype "input"))
    )
    (net (code "50") (name "Net-(E1D-I0)") (class "Default")
      (node (ref "D1") (pin "A") (pinfunction "A_A") (pintype "passive"))
      (node (ref "D109") (pin "A") (pinfunction "A_A") (pintype "passive"))
      (node (ref "D121") (pin "A") (pinfunction "A_A") (pintype "passive"))
      (node (ref "D13") (pin "A") (pinfunction "A_A") (pintype "passive"))
      (node (ref "D133") (pin "A") (pinfunction "A_A") (pintype "passive"))
      (node (ref "D145") (pin "A") (pinfunction "A_A") (pintype "passive"))
      (node (ref "D157") (pin "A") (pinfunction "A_A") (pintype "passive"))
      (node (ref "D169") (pin "A") (pinfunction "A_A") (pintype "passive"))
      (node (ref "D181") (pin "A") (pinfunction "A_A") (pintype "passive"))
      (node (ref "D193") (pin "A") (pinfunction "A_A") (pintype "passive"))
      (node (ref "D205") (pin "A") (pinfunction "A_A") (pintype "passive"))
      (node (ref "D217") (pin "A") (pinfunction "A_A") (pintype "passive"))
      (node (ref "D229") (pin "A") (pinfunction "A_A") (pintype "passive"))
      (node (ref "D241") (pin "A") (pinfunction "A_A") (pintype "passive"))
      (node (ref "D25") (pin "A") (pinfunction "A_A") (pintype "passive"))
      (node (ref "D253") (pin "A") (pinfunction "A_A") (pintype "passive"))
      (node (ref "D265") (pin "A") (pinfunction "A_A") (pintype "passive"))
      (node (ref "D277") (pin "A") (pinfunction "A_A") (pintype "passive"))
      (node (ref "D289") (pin "A") (pinfunction "A_A") (pintype "passive"))
      (node (ref "D301") (pin "A") (pinfunction "A_A") (pintype "passive"))
      (node (ref "D313") (pin "A") (pinfunction "A_A") (pintype "passive"))
      (node (ref "D325") (pin "A") (pinfunction "A_A") (pintype "passive"))
      (node (ref "D337") (pin "A") (pinfunction "A_A") (pintype "passive"))
      (node (ref "D349") (pin "A") (pinfunction "A_A") (pintype "passive"))
      (node (ref "D361") (pin "A") (pinfunction "A_A") (pintype "passive"))
      (node (ref "D37") (pin "A") (pinfunction "A_A") (pintype "passive"))
      (node (ref "D373") (pin "A") (pinfunction "A_A") (pintype "passive"))
      (node (ref "D49") (pin "A") (pinfunction "A_A") (pintype "passive"))
      (node (ref "D61") (pin "A") (pinfunction "A_A") (pintype "passive"))
      (node (ref "D73") (pin "A") (pinfunction "A_A") (pintype "passive"))
      (node (ref "D85") (pin "A") (pinfunction "A_A") (pintype "passive"))
      (node (ref "D97") (pin "A") (pinfunction "A_A") (pintype "passive"))
      (node (ref "E1") (pin "11") (pinfunction "I0_11") (pintype "input"))
      (node (ref "E1") (pin "12") (pinfunction "I1_12") (pintype "input"))
      (node (ref "R40") (pin "2") (pinfunction "2_2") (pintype "passive"))
    )
    (net (code "51") (name "Net-(E1D-O)") (class "Default")
      (node (ref "E1") (pin "13") (pinfunction "O_13") (pintype "output"))
      (node (ref "E4") (pin "8") (pinfunction "I0_8") (pintype "input"))
    )
    (net (code "52") (name "Net-(E2D-O)") (class "Default")
      (node (ref "E2") (pin "13") (pinfunction "O_13") (pintype "output"))
      (node (ref "E5") (pin "10") (pinfunction "I1_10") (pintype "input"))
      (node (ref "E5") (pin "9") (pinfunction "I0_9") (pintype "input"))
    )
    (net (code "53") (name "Net-(E3A-I)") (class "Default")
      (node (ref "E3") (pin "1") (pinfunction "I_1") (pintype "input"))
      (node (ref "E6") (pin "10") (pinfunction "QE_10") (pintype "output"))
    )
    (net (code "54") (name "Net-(E3B-I)") (class "Default")
      (node (ref "E3") (pin "3") (pinfunction "I_3") (pintype "input"))
      (node (ref "E6") (pin "6") (pinfunction "QD_6") (pintype "output"))
    )
    (net (code "55") (name "Net-(E3C-I)") (class "Default")
      (node (ref "E3") (pin "5") (pinfunction "I_5") (pintype "input"))
      (node (ref "E6") (pin "5") (pinfunction "QC_5") (pintype "output"))
    )
    (net (code "56") (name "Net-(E3E-I)") (class "Default")
      (node (ref "E3") (pin "11") (pinfunction "I_11") (pintype "input"))
      (node (ref "E6") (pin "12") (pinfunction "QG_12") (pintype "output"))
    )
    (net (code "57") (name "Net-(E3F-I)") (class "Default")
      (node (ref "E3") (pin "13") (pinfunction "I_13") (pintype "input"))
      (node (ref "E6") (pin "11") (pinfunction "QF_11") (pintype "output"))
    )
    (net (code "58") (name "Net-(E5C-O)") (class "Default")
      (node (ref "E5") (pin "13") (pinfunction "I1_13") (pintype "input"))
      (node (ref "E5") (pin "8") (pinfunction "O_8") (pintype "output"))
    )
    (net (code "59") (name "Net-(E6A-A)") (class "Default")
      (node (ref "E6") (pin "1") (pinfunction "A_1") (pintype "input"))
      (node (ref "E6") (pin "2") (pinfunction "B_2") (pintype "input"))
      (node (ref "E8") (pin "13") (pinfunction "I_13") (pintype "input"))
      (node (ref "E9") (pin "13") (pinfunction "QH_13") (pintype "output"))
    )
    (net (code "60") (name "Net-(E6A-QA)") (class "Default")
      (node (ref "E6") (pin "3") (pinfunction "QA_3") (pintype "output"))
      (node (ref "E8") (pin "11") (pinfunction "I_11") (pintype "input"))
    )
    (net (code "61") (name "Net-(E6A-QB)") (class "Default")
      (node (ref "E6") (pin "4") (pinfunction "QB_4") (pintype "output"))
      (node (ref "E8") (pin "9") (pinfunction "I_9") (pintype "input"))
    )
    (net (code "62") (name "Net-(E7A-A0)") (class "Default")
      (node (ref "E7") (pin "1") (pinfunction "A0_1") (pintype "input"))
      (node (ref "R7") (pin "1") (pinfunction "1_1") (pintype "passive"))
      (node (ref "S3") (pin "2") (pinfunction "2_2") (pintype "passive"))
    )
    (net (code "63") (name "Net-(E7A-A1)") (class "Default")
      (node (ref "E7") (pin "6") (pinfunction "A1_6") (pintype "input"))
      (node (ref "R6") (pin "1") (pinfunction "1_1") (pintype "passive"))
      (node (ref "S2") (pin "2") (pinfunction "2_2") (pintype "passive"))
    )
    (net (code "64") (name "Net-(E7A-A2)") (class "Default")
      (node (ref "E7") (pin "10") (pinfunction "A2_10") (pintype "input"))
      (node (ref "R5") (pin "1") (pinfunction "1_1") (pintype "passive"))
      (node (ref "S0") (pin "2") (pinfunction "2_2") (pintype "passive"))
    )
    (net (code "65") (name "Net-(E7A-A3)") (class "Default")
      (node (ref "E7") (pin "15") (pinfunction "A3_15") (pintype "input"))
      (node (ref "R4") (pin "1") (pinfunction "1_1") (pintype "passive"))
      (node (ref "S1") (pin "2") (pinfunction "2_2") (pintype "passive"))
    )
    (net (code "66") (name "Net-(E7A-B0)") (class "Default")
      (node (ref "E7") (pin "2") (pinfunction "B0_2") (pintype "input"))
      (node (ref "I3") (pin "2") (pinfunction "2_2") (pintype "passive"))
      (node (ref "R11") (pin "2") (pinfunction "2_2") (pintype "passive"))
    )
    (net (code "67") (name "Net-(E7A-B1)") (class "Default")
      (node (ref "E7") (pin "5") (pinfunction "B1_5") (pintype "input"))
      (node (ref "I2") (pin "2") (pinfunction "2_2") (pintype "passive"))
      (node (ref "R10") (pin "2") (pinfunction "2_2") (pintype "passive"))
    )
    (net (code "68") (name "Net-(E7A-B2)") (class "Default")
      (node (ref "E7") (pin "11") (pinfunction "B2_11") (pintype "input"))
      (node (ref "I0") (pin "2") (pinfunction "2_2") (pintype "passive"))
      (node (ref "R9") (pin "2") (pinfunction "2_2") (pintype "passive"))
    )
    (net (code "69") (name "Net-(E7A-B3)") (class "Default")
      (node (ref "E7") (pin "14") (pinfunction "B3_14") (pintype "input"))
      (node (ref "I1") (pin "2") (pinfunction "2_2") (pintype "passive"))
      (node (ref "R8") (pin "2") (pinfunction "2_2") (pintype "passive"))
    )
    (net (code "70") (name "Net-(E8A-I)") (class "Default")
      (node (ref "E8") (pin "1") (pinfunction "I_1") (pintype "input"))
      (node (ref "E9") (pin "12") (pinfunction "QG_12") (pintype "output"))
    )
    (net (code "71") (name "Net-(E8B-I)") (class "Default")
      (node (ref "E8") (pin "3") (pinfunction "I_3") (pintype "input"))
      (node (ref "E9") (pin "11") (pinfunction "QF_11") (pintype "output"))
    )
    (net (code "72") (name "Net-(E8C-I)") (class "Default")
      (node (ref "E8") (pin "5") (pinfunction "I_5") (pintype "input"))
      (node (ref "E9") (pin "10") (pinfunction "QE_10") (pintype "output"))
    )
    (net (code "73") (name "Net-(E10A-I)") (class "Default")
      (node (ref "E10") (pin "1") (pinfunction "I_1") (pintype "input"))
      (node (ref "E9") (pin "3") (pinfunction "QA_3") (pintype "output"))
    )
    (net (code "74") (name "Net-(E10B-I)") (class "Default")
      (node (ref "E10") (pin "3") (pinfunction "I_3") (pintype "input"))
      (node (ref "E5") (pin "11") (pinfunction "O_11") (pintype "output"))
    )
    (net (code "75") (name "Net-(E10C-I)") (class "Default")
      (node (ref "E10") (pin "5") (pinfunction "I_5") (pintype "input"))
      (node (ref "E15") (pin "10") (pinfunction "O_10") (pintype "output"))
      (node (ref "E23") (pin "3") (pinfunction "CLK_3") (pintype "input"))
    )
    (net (code "76") (name "Net-(E10C-O)") (class "Default")
      (node (ref "E10") (pin "6") (pinfunction "O_6") (pintype "output"))
      (node (ref "E18") (pin "3") (pinfunction "CLK_3") (pintype "input"))
    )
    (net (code "77") (name "Net-(E10D-I)") (class "Default")
      (node (ref "E10") (pin "9") (pinfunction "I_9") (pintype "input"))
      (node (ref "E9") (pin "6") (pinfunction "QD_6") (pintype "output"))
    )
    (net (code "78") (name "Net-(E10E-I)") (class "Default")
      (node (ref "E10") (pin "11") (pinfunction "I_11") (pintype "input"))
      (node (ref "E9") (pin "5") (pinfunction "QC_5") (pintype "output"))
    )
    (net (code "79") (name "Net-(E10F-I)") (class "Default")
      (node (ref "E10") (pin "13") (pinfunction "I_13") (pintype "input"))
      (node (ref "E9") (pin "4") (pinfunction "QB_4") (pintype "output"))
    )
    (net (code "80") (name "Net-(E11A-A0)") (class "Default")
      (node (ref "E11") (pin "1") (pinfunction "A0_1") (pintype "input"))
      (node (ref "R15") (pin "1") (pinfunction "1_1") (pintype "passive"))
      (node (ref "S5") (pin "2") (pinfunction "2_2") (pintype "passive"))
    )
    (net (code "81") (name "Net-(E11A-A1)") (class "Default")
      (node (ref "E11") (pin "6") (pinfunction "A1_6") (pintype "input"))
      (node (ref "R14") (pin "1") (pinfunction "1_1") (pintype "passive"))
      (node (ref "S4") (pin "2") (pinfunction "2_2") (pintype "passive"))
    )
    (net (code "82") (name "Net-(E11A-A2)") (class "Default")
      (node (ref "E11") (pin "10") (pinfunction "A2_10") (pintype "input"))
      (node (ref "R13") (pin "1") (pinfunction "1_1") (pintype "passive"))
      (node (ref "S6") (pin "2") (pinfunction "2_2") (pintype "passive"))
    )
    (net (code "83") (name "Net-(E11A-A3)") (class "Default")
      (node (ref "E11") (pin "15") (pinfunction "A3_15") (pintype "input"))
      (node (ref "R12") (pin "1") (pinfunction "1_1") (pintype "passive"))
      (node (ref "S7") (pin "2") (pinfunction "2_2") (pintype "passive"))
    )
    (net (code "84") (name "Net-(E11A-B0)") (class "Default")
      (node (ref "E11") (pin "2") (pinfunction "B0_2") (pintype "input"))
      (node (ref "I5") (pin "2") (pinfunction "2_2") (pintype "passive"))
      (node (ref "R19") (pin "2") (pinfunction "2_2") (pintype "passive"))
    )
    (net (code "85") (name "Net-(E11A-B1)") (class "Default")
      (node (ref "E11") (pin "5") (pinfunction "B1_5") (pintype "input"))
      (node (ref "I4") (pin "2") (pinfunction "2_2") (pintype "passive"))
      (node (ref "R18") (pin "2") (pinfunction "2_2") (pintype "passive"))
    )
    (net (code "86") (name "Net-(E11A-B2)") (class "Default")
      (node (ref "E11") (pin "11") (pinfunction "B2_11") (pintype "input"))
      (node (ref "I6") (pin "2") (pinfunction "2_2") (pintype "passive"))
      (node (ref "R17") (pin "2") (pinfunction "2_2") (pintype "passive"))
    )
    (net (code "87") (name "Net-(E11A-B3)") (class "Default")
      (node (ref "E11") (pin "14") (pinfunction "B3_14") (pintype "input"))
      (node (ref "I7") (pin "2") (pinfunction "2_2") (pintype "passive"))
      (node (ref "R16") (pin "2") (pinfunction "2_2") (pintype "passive"))
    )
    (net (code "88") (name "Net-(E12A-CLK)") (class "Default")
      (node (ref "E12") (pin "3") (pinfunction "CLK_3") (pintype "input"))
      (node (ref "E20") (pin "3") (pinfunction "O_3") (pintype "output"))
      (node (ref "E24") (pin "3") (pinfunction "I_3") (pintype "input"))
    )
    (net (code "89") (name "Net-(E12A-CLR)") (class "Default")
      (node (ref "E12") (pin "1") (pinfunction "CLR_1") (pintype "input"))
      (node (ref "E18") (pin "4") (pinfunction "PRE_4") (pintype "input"))
      (node (ref "E20") (pin "13") (pinfunction "O_13") (pintype "output"))
      (node (ref "E23") (pin "4") (pinfunction "PRE_4") (pintype "input"))
    )
    (net (code "90") (name "Net-(E12A-~{Q})") (class "Default")
      (node (ref "E12") (pin "6") (pinfunction "~{Q}_6") (pintype "output"))
      (node (ref "E15") (pin "6") (pinfunction "I1_6") (pintype "input"))
      (node (ref "E22") (pin "9") (pinfunction "I1_9") (pintype "input"))
    )
    (net (code "91") (name "Net-(E12B-CLK)") (class "Default")
      (node (ref "E12") (pin "11") (pinfunction "CLK_11") (pintype "input"))
      (node (ref "E13") (pin "11") (pinfunction "O_11") (pintype "output"))
      (node (ref "E15") (pin "9") (pinfunction "I1_9") (pintype "input"))
      (node (ref "E2") (pin "4") (pinfunction "I0_4") (pintype "input"))
      (node (ref "E2") (pin "5") (pinfunction "I1_5") (pintype "input"))
      (node (ref "R53") (pin "1") (pinfunction "1_1") (pintype "passive"))
    )
    (net (code "92") (name "Net-(E12B-PRE)") (class "Default")
      (node (ref "E12") (pin "10") (pinfunction "PRE_10") (pintype "input"))
      (node (ref "E18") (pin "6") (pinfunction "~{Q}_6") (pintype "output"))
      (node (ref "E22") (pin "8") (pinfunction "I0_8") (pintype "input"))
      (node (ref "E36") (pin "9") (pinfunction "I0_9") (pintype "input"))
    )
    (net (code "93") (name "Net-(E12B-Q)") (class "Default")
      (node (ref "E12") (pin "9") (pinfunction "Q_9") (pintype "output"))
      (node (ref "E15") (pin "8") (pinfunction "I0_8") (pintype "input"))
      (node (ref "E5") (pin "5") (pinfunction "I1_5") (pintype "input"))
    )
    (net (code "94") (name "Net-(E12B-~{Q})") (class "Default")
      (node (ref "E12") (pin "8") (pinfunction "~{Q}_8") (pintype "output"))
      (node (ref "E5") (pin "1") (pinfunction "I0_1") (pintype "input"))
    )
    (net (code "95") (name "Net-(E13A-I0)") (class "Default")
      (node (ref "E13") (pin "1") (pinfunction "I0_1") (pintype "input"))
      (node (ref "E16") (pin "12") (pinfunction "I1_12") (pintype "input"))
      (node (ref "E19") (pin "5") (pinfunction "Q_5") (pintype "output"))
      (node (ref "R38") (pin "1") (pinfunction "1_1") (pintype "passive"))
    )
    (net (code "96") (name "Net-(E13A-I1)") (class "Default")
      (node (ref "C7") (pin "1") (pinfunction "1_1") (pintype "passive"))
      (node (ref "E13") (pin "2") (pinfunction "I1_2") (pintype "input"))
      (node (ref "E16") (pin "11") (pinfunction "I0_11") (pintype "input"))
      (node (ref "R38") (pin "2") (pinfunction "2_2") (pintype "passive"))
    )
    (net (code "97") (name "Net-(E13A-O)") (class "Default")
      (node (ref "E13") (pin "3") (pinfunction "O_3") (pintype "output"))
      (node (ref "E16") (pin "6") (pinfunction "I1_6") (pintype "input"))
    )
    (net (code "98") (name "Net-(E14A-I0)") (class "Default")
      (node (ref "E14") (pin "2") (pinfunction "I0_2") (pintype "input"))
      (node (ref "E17") (pin "14") (pinfunction "O_14") (pintype "output"))
    )
    (net (code "99") (name "Net-(E14B-I0)") (class "Default")
      (node (ref "E14") (pin "5") (pinfunction "I0_5") (pintype "input"))
      (node (ref "E17") (pin "13") (pinfunction "O_13") (pintype "output"))
    )
    (net (code "100") (name "Net-(E14C-I0)") (class "Default")
      (node (ref "E14") (pin "8") (pinfunction "I0_8") (pintype "input"))
      (node (ref "E17") (pin "3") (pinfunction "O_3") (pintype "output"))
    )
    (net (code "101") (name "Net-(E14D-I0)") (class "Default")
      (node (ref "E14") (pin "11") (pinfunction "I0_11") (pintype "input"))
      (node (ref "E17") (pin "2") (pinfunction "O_2") (pintype "output"))
    )
    (net (code "102") (name "Net-(E15B-I0)") (class "Default")
      (node (ref "E15") (pin "5") (pinfunction "I0_5") (pintype "input"))
      (node (ref "E20") (pin "2") (pinfunction "O_2") (pintype "output"))
    )
    (net (code "103") (name "Net-(E15D-I0)") (class "Default")
      (node (ref "E15") (pin "11") (pinfunction "I0_11") (pintype "input"))
      (node (ref "E20") (pin "14") (pinfunction "O_14") (pintype "output"))
    )
    (net (code "104") (name "Net-(E15D-O)") (class "Default")
      (node (ref "E15") (pin "13") (pinfunction "O_13") (pintype "output"))
      (node (ref "E21") (pin "6") (pinfunction "I1_6") (pintype "input"))
      (node (ref "E22") (pin "5") (pinfunction "I0_5") (pintype "input"))
      (node (ref "E36") (pin "5") (pinfunction "I1_5") (pintype "input"))
    )
    (net (code "105") (name "Net-(E16A-I0)") (class "Default")
      (node (ref "E16") (pin "13") (pinfunction "O_13") (pintype "output"))
      (node (ref "E16") (pin "2") (pinfunction "I0_2") (pintype "input"))
    )
    (net (code "106") (name "Net-(E16A-I1)") (class "Default")
      (node (ref "E16") (pin "10") (pinfunction "O_10") (pintype "output"))
      (node (ref "E16") (pin "3") (pinfunction "I1_3") (pintype "input"))
      (node (ref "E16") (pin "5") (pinfunction "I0_5") (pintype "input"))
    )
    (net (code "107") (name "Net-(E16A-O)") (class "Default")
      (node (ref "E16") (pin "1") (pinfunction "O_1") (pintype "output"))
      (node (ref "E2") (pin "12") (pinfunction "I1_12") (pintype "input"))
    )
    (net (code "108") (name "Net-(E16B-O)") (class "Default")
      (node (ref "E16") (pin "4") (pinfunction "O_4") (pintype "output"))
      (node (ref "Q2") (pin "2") (pinfunction "B_2") (pintype "passive"))
      (node (ref "R39") (pin "1") (pinfunction "1_1") (pintype "passive"))
    )
    (net (code "109") (name "Net-(E17A-I0)") (class "Default")
      (node (ref "D101") (pin "A") (pinfunction "A_A") (pintype "passive"))
      (node (ref "D113") (pin "A") (pinfunction "A_A") (pintype "passive"))
      (node (ref "D125") (pin "A") (pinfunction "A_A") (pintype "passive"))
      (node (ref "D137") (pin "A") (pinfunction "A_A") (pintype "passive"))
      (node (ref "D149") (pin "A") (pinfunction "A_A") (pintype "passive"))
      (node (ref "D161") (pin "A") (pinfunction "A_A") (pintype "passive"))
      (node (ref "D17") (pin "A") (pinfunction "A_A") (pintype "passive"))
      (node (ref "D173") (pin "A") (pinfunction "A_A") (pintype "passive"))
      (node (ref "D185") (pin "A") (pinfunction "A_A") (pintype "passive"))
      (node (ref "D197") (pin "A") (pinfunction "A_A") (pintype "passive"))
      (node (ref "D209") (pin "A") (pinfunction "A_A") (pintype "passive"))
      (node (ref "D221") (pin "A") (pinfunction "A_A") (pintype "passive"))
      (node (ref "D233") (pin "A") (pinfunction "A_A") (pintype "passive"))
      (node (ref "D245") (pin "A") (pinfunction "A_A") (pintype "passive"))
      (node (ref "D257") (pin "A") (pinfunction "A_A") (pintype "passive"))
      (node (ref "D269") (pin "A") (pinfunction "A_A") (pintype "passive"))
      (node (ref "D281") (pin "A") (pinfunction "A_A") (pintype "passive"))
      (node (ref "D29") (pin "A") (pinfunction "A_A") (pintype "passive"))
      (node (ref "D293") (pin "A") (pinfunction "A_A") (pintype "passive"))
      (node (ref "D305") (pin "A") (pinfunction "A_A") (pintype "passive"))
      (node (ref "D317") (pin "A") (pinfunction "A_A") (pintype "passive"))
      (node (ref "D329") (pin "A") (pinfunction "A_A") (pintype "passive"))
      (node (ref "D341") (pin "A") (pinfunction "A_A") (pintype "passive"))
      (node (ref "D353") (pin "A") (pinfunction "A_A") (pintype "passive"))
      (node (ref "D365") (pin "A") (pinfunction "A_A") (pintype "passive"))
      (node (ref "D377") (pin "A") (pinfunction "A_A") (pintype "passive"))
      (node (ref "D41") (pin "A") (pinfunction "A_A") (pintype "passive"))
      (node (ref "D5") (pin "A") (pinfunction "A_A") (pintype "passive"))
      (node (ref "D53") (pin "A") (pinfunction "A_A") (pintype "passive"))
      (node (ref "D65") (pin "A") (pinfunction "A_A") (pintype "passive"))
      (node (ref "D77") (pin "A") (pinfunction "A_A") (pintype "passive"))
      (node (ref "D89") (pin "A") (pinfunction "A_A") (pintype "passive"))
      (node (ref "E17") (pin "4") (pinfunction "I0_4") (pintype "input"))
      (node (ref "E17") (pin "5") (pinfunction "I1_5") (pintype "input"))
      (node (ref "R44") (pin "2") (pinfunction "2_2") (pintype "passive"))
    )
    (net (code "110") (name "Net-(E17B-I0)") (class "Default")
      (node (ref "D102") (pin "A") (pinfunction "A_A") (pintype "passive"))
      (node (ref "D114") (pin "A") (pinfunction "A_A") (pintype "passive"))
      (node (ref "D126") (pin "A") (pinfunction "A_A") (pintype "passive"))
      (node (ref "D138") (pin "A") (pinfunction "A_A") (pintype "passive"))
      (node (ref "D150") (pin "A") (pinfunction "A_A") (pintype "passive"))
      (node (ref "D162") (pin "A") (pinfunction "A_A") (pintype "passive"))
      (node (ref "D174") (pin "A") (pinfunction "A_A") (pintype "passive"))
      (node (ref "D18") (pin "A") (pinfunction "A_A") (pintype "passive"))
      (node (ref "D186") (pin "A") (pinfunction "A_A") (pintype "passive"))
      (node (ref "D198") (pin "A") (pinfunction "A_A") (pintype "passive"))
      (node (ref "D210") (pin "A") (pinfunction "A_A") (pintype "passive"))
      (node (ref "D222") (pin "A") (pinfunction "A_A") (pintype "passive"))
      (node (ref "D234") (pin "A") (pinfunction "A_A") (pintype "passive"))
      (node (ref "D246") (pin "A") (pinfunction "A_A") (pintype "passive"))
      (node (ref "D258") (pin "A") (pinfunction "A_A") (pintype "passive"))
      (node (ref "D270") (pin "A") (pinfunction "A_A") (pintype "passive"))
      (node (ref "D282") (pin "A") (pinfunction "A_A") (pintype "passive"))
      (node (ref "D294") (pin "A") (pinfunction "A_A") (pintype "passive"))
      (node (ref "D30") (pin "A") (pinfunction "A_A") (pintype "passive"))
      (node (ref "D306") (pin "A") (pinfunction "A_A") (pintype "passive"))
      (node (ref "D318") (pin "A") (pinfunction "A_A") (pintype "passive"))
      (node (ref "D330") (pin "A") (pinfunction "A_A") (pintype "passive"))
      (node (ref "D342") (pin "A") (pinfunction "A_A") (pintype "passive"))
      (node (ref "D354") (pin "A") (pinfunction "A_A") (pintype "passive"))
      (node (ref "D366") (pin "A") (pinfunction "A_A") (pintype "passive"))
      (node (ref "D378") (pin "A") (pinfunction "A_A") (pintype "passive"))
      (node (ref "D42") (pin "A") (pinfunction "A_A") (pintype "passive"))
      (node (ref "D54") (pin "A") (pinfunction "A_A") (pintype "passive"))
      (node (ref "D6") (pin "A") (pinfunction "A_A") (pintype "passive"))
      (node (ref "D66") (pin "A") (pinfunction "A_A") (pintype "passive"))
      (node (ref "D78") (pin "A") (pinfunction "A_A") (pintype "passive"))
      (node (ref "D90") (pin "A") (pinfunction "A_A") (pintype "passive"))
      (node (ref "E17") (pin "6") (pinfunction "I0_6") (pintype "input"))
      (node (ref "E17") (pin "7") (pinfunction "I1_7") (pintype "input"))
      (node (ref "R45") (pin "2") (pinfunction "2_2") (pintype "passive"))
    )
    (net (code "111") (name "Net-(E17C-I0)") (class "Default")
      (node (ref "D104") (pin "A") (pinfunction "A_A") (pintype "passive"))
      (node (ref "D116") (pin "A") (pinfunction "A_A") (pintype "passive"))
      (node (ref "D128") (pin "A") (pinfunction "A_A") (pintype "passive"))
      (node (ref "D140") (pin "A") (pinfunction "A_A") (pintype "passive"))
      (node (ref "D152") (pin "A") (pinfunction "A_A") (pintype "passive"))
      (node (ref "D164") (pin "A") (pinfunction "A_A") (pintype "passive"))
      (node (ref "D176") (pin "A") (pinfunction "A_A") (pintype "passive"))
      (node (ref "D188") (pin "A") (pinfunction "A_A") (pintype "passive"))
      (node (ref "D20") (pin "A") (pinfunction "A_A") (pintype "passive"))
      (node (ref "D200") (pin "A") (pinfunction "A_A") (pintype "passive"))
      (node (ref "D212") (pin "A") (pinfunction "A_A") (pintype "passive"))
      (node (ref "D224") (pin "A") (pinfunction "A_A") (pintype "passive"))
      (node (ref "D236") (pin "A") (pinfunction "A_A") (pintype "passive"))
      (node (ref "D248") (pin "A") (pinfunction "A_A") (pintype "passive"))
      (node (ref "D260") (pin "A") (pinfunction "A_A") (pintype "passive"))
      (node (ref "D272") (pin "A") (pinfunction "A_A") (pintype "passive"))
      (node (ref "D284") (pin "A") (pinfunction "A_A") (pintype "passive"))
      (node (ref "D296") (pin "A") (pinfunction "A_A") (pintype "passive"))
      (node (ref "D308") (pin "A") (pinfunction "A_A") (pintype "passive"))
      (node (ref "D32") (pin "A") (pinfunction "A_A") (pintype "passive"))
      (node (ref "D320") (pin "A") (pinfunction "A_A") (pintype "passive"))
      (node (ref "D332") (pin "A") (pinfunction "A_A") (pintype "passive"))
      (node (ref "D344") (pin "A") (pinfunction "A_A") (pintype "passive"))
      (node (ref "D356") (pin "A") (pinfunction "A_A") (pintype "passive"))
      (node (ref "D368") (pin "A") (pinfunction "A_A") (pintype "passive"))
      (node (ref "D380") (pin "A") (pinfunction "A_A") (pintype "passive"))
      (node (ref "D44") (pin "A") (pinfunction "A_A") (pintype "passive"))
      (node (ref "D56") (pin "A") (pinfunction "A_A") (pintype "passive"))
      (node (ref "D68") (pin "A") (pinfunction "A_A") (pintype "passive"))
      (node (ref "D8") (pin "A") (pinfunction "A_A") (pintype "passive"))
      (node (ref "D80") (pin "A") (pinfunction "A_A") (pintype "passive"))
      (node (ref "D92") (pin "A") (pinfunction "A_A") (pintype "passive"))
      (node (ref "E17") (pin "10") (pinfunction "I1_10") (pintype "input"))
      (node (ref "E17") (pin "9") (pinfunction "I0_9") (pintype "input"))
      (node (ref "R47") (pin "2") (pinfunction "2_2") (pintype "passive"))
    )
    (net (code "112") (name "Net-(E17D-I0)") (class "Default")
      (node (ref "D103") (pin "A") (pinfunction "A_A") (pintype "passive"))
      (node (ref "D115") (pin "A") (pinfunction "A_A") (pintype "passive"))
      (node (ref "D127") (pin "A") (pinfunction "A_A") (pintype "passive"))
      (node (ref "D139") (pin "A") (pinfunction "A_A") (pintype "passive"))
      (node (ref "D151") (pin "A") (pinfunction "A_A") (pintype "passive"))
      (node (ref "D163") (pin "A") (pinfunction "A_A") (pintype "passive"))
      (node (ref "D175") (pin "A") (pinfunction "A_A") (pintype "passive"))
      (node (ref "D187") (pin "A") (pinfunction "A_A") (pintype "passive"))
      (node (ref "D19") (pin "A") (pinfunction "A_A") (pintype "passive"))
      (node (ref "D199") (pin "A") (pinfunction "A_A") (pintype "passive"))
      (node (ref "D211") (pin "A") (pinfunction "A_A") (pintype "passive"))
      (node (ref "D223") (pin "A") (pinfunction "A_A") (pintype "passive"))
      (node (ref "D235") (pin "A") (pinfunction "A_A") (pintype "passive"))
      (node (ref "D247") (pin "A") (pinfunction "A_A") (pintype "passive"))
      (node (ref "D259") (pin "A") (pinfunction "A_A") (pintype "passive"))
      (node (ref "D271") (pin "A") (pinfunction "A_A") (pintype "passive"))
      (node (ref "D283") (pin "A") (pinfunction "A_A") (pintype "passive"))
      (node (ref "D295") (pin "A") (pinfunction "A_A") (pintype "passive"))
      (node (ref "D307") (pin "A") (pinfunction "A_A") (pintype "passive"))
      (node (ref "D31") (pin "A") (pinfunction "A_A") (pintype "passive"))
      (node (ref "D319") (pin "A") (pinfunction "A_A") (pintype "passive"))
      (node (ref "D331") (pin "A") (pinfunction "A_A") (pintype "passive"))
      (node (ref "D343") (pin "A") (pinfunction "A_A") (pintype "passive"))
      (node (ref "D355") (pin "A") (pinfunction "A_A") (pintype "passive"))
      (node (ref "D367") (pin "A") (pinfunction "A_A") (pintype "passive"))
      (node (ref "D379") (pin "A") (pinfunction "A_A") (pintype "passive"))
      (node (ref "D43") (pin "A") (pinfunction "A_A") (pintype "passive"))
      (node (ref "D55") (pin "A") (pinfunction "A_A") (pintype "passive"))
      (node (ref "D67") (pin "A") (pinfunction "A_A") (pintype "passive"))
      (node (ref "D7") (pin "A") (pinfunction "A_A") (pintype "passive"))
      (node (ref "D79") (pin "A") (pinfunction "A_A") (pintype "passive"))
      (node (ref "D91") (pin "A") (pinfunction "A_A") (pintype "passive"))
      (node (ref "E17") (pin "11") (pinfunction "I0_11") (pintype "input"))
      (node (ref "E17") (pin "12") (pinfunction "I1_12") (pintype "input"))
      (node (ref "R46") (pin "2") (pinfunction "2_2") (pintype "passive"))
    )
    (net (code "113") (name "Net-(E18B-Q)") (class "Default")
      (node (ref "E18") (pin "9") (pinfunction "Q_9") (pintype "output"))
      (node (ref "E19") (pin "1") (pinfunction "A_1") (pintype "input"))
    )
    (net (code "114") (name "Net-(E19A-B)") (class "Default")
      (node (ref "E19") (pin "2") (pinfunction "B_2") (pintype "input"))
      (node (ref "E27") (pin "13") (pinfunction "O_13") (pintype "output"))
    )
    (net (code "115") (name "Net-(E19A-C)") (class "Default")
      (node (ref "C1") (pin "1") (pinfunction "1_1") (pintype "passive"))
      (node (ref "E19") (pin "14") (pinfunction "C_14") (pintype "input"))
    )
    (net (code "116") (name "Net-(E19A-R{slash}C)") (class "Default")
      (node (ref "C1") (pin "2") (pinfunction "2_2") (pintype "passive"))
      (node (ref "E19") (pin "15") (pinfunction "R/C_15") (pintype "input"))
      (node (ref "R31") (pin "2") (pinfunction "2_2") (pintype "passive"))
    )
    (net (code "117") (name "Net-(E19B-B)") (class "Default")
      (node (ref "E19") (pin "10") (pinfunction "B_10") (pintype "input"))
      (node (ref "E24") (pin "6") (pinfunction "O_6") (pintype "output"))
      (node (ref "R35") (pin "2") (pinfunction "2_2") (pintype "passive"))
    )
    (net (code "118") (name "Net-(E19B-C)") (class "Default")
      (node (ref "C3") (pin "1") (pinfunction "1_1") (pintype "passive"))
      (node (ref "E19") (pin "6") (pinfunction "C_6") (pintype "input"))
    )
    (net (code "119") (name "Net-(E19B-R{slash}C)") (class "Default")
      (node (ref "C3") (pin "2") (pinfunction "2_2") (pintype "passive"))
      (node (ref "E19") (pin "7") (pinfunction "R/C_7") (pintype "input"))
      (node (ref "R34") (pin "2") (pinfunction "2_2") (pintype "passive"))
    )
    (net (code "120") (name "Net-(E20A-I0)") (class "Default")
      (node (ref "E2") (pin "3") (pinfunction "O_3") (pintype "output"))
      (node (ref "E20") (pin "4") (pinfunction "I0_4") (pintype "input"))
    )
    (net (code "121") (name "Net-(E20D-I0)") (class "Default")
      (node (ref "E20") (pin "11") (pinfunction "I0_11") (pintype "input"))
      (node (ref "E20") (pin "12") (pinfunction "I1_12") (pintype "input"))
      (node (ref "E27") (pin "14") (pinfunction "O_14") (pintype "output"))
    )
    (net (code "122") (name "Net-(E21A-I1)") (class "Default")
      (node (ref "E21") (pin "3") (pinfunction "I1_3") (pintype "input"))
      (node (ref "E29") (pin "8") (pinfunction "I0_8") (pintype "input"))
      (node (ref "F1") (pin "2") (pinfunction "2_2") (pintype "passive"))
      (node (ref "R2") (pin "1") (pinfunction "1_1") (pintype "passive"))
    )
    (net (code "123") (name "Net-(E21B-I0)") (class "Default")
      (node (ref "E21") (pin "5") (pinfunction "I0_5") (pintype "input"))
      (node (ref "E30") (pin "5") (pinfunction "Q_5") (pintype "output"))
      (node (ref "E33") (pin "2") (pinfunction "I0_2") (pintype "input"))
      (node (ref "E36") (pin "12") (pinfunction "I0_12") (pintype "input"))
    )
    (net (code "124") (name "Net-(E21C-I0)") (class "Default")
      (node (ref "E21") (pin "8") (pinfunction "I0_8") (pintype "input"))
      (node (ref "E29") (pin "5") (pinfunction "I0_5") (pintype "input"))
      (node (ref "F2") (pin "2") (pinfunction "2_2") (pintype "passive"))
      (node (ref "R1") (pin "1") (pinfunction "1_1") (pintype "passive"))
    )
    (net (code "125") (name "Net-(E22B-I1)") (class "Default")
      (node (ref "E22") (pin "6") (pinfunction "I1_6") (pintype "input"))
      (node (ref "E30") (pin "8") (pinfunction "~{Q}_8") (pintype "output"))
      (node (ref "E36") (pin "4") (pinfunction "I0_4") (pintype "input"))
    )
    (net (code "126") (name "Net-(E22D-I0)") (class "Default")
      (node (ref "E22") (pin "11") (pinfunction "I0_11") (pintype "input"))
      (node (ref "E22") (pin "12") (pinfunction "I1_12") (pintype "input"))
      (node (ref "E23") (pin "6") (pinfunction "~{Q}_6") (pintype "output"))
    )
    (net (code "127") (name "Net-(E24A-I)") (class "Default")
      (node (ref "E24") (pin "1") (pinfunction "I_1") (pintype "input"))
      (node (ref "E25") (pin "10") (pinfunction "QE_10") (pintype "output"))
    )
    (net (code "128") (name "Net-(E24C-I)") (class "Default")
      (node (ref "E24") (pin "5") (pinfunction "I_5") (pintype "input"))
      (node (ref "E27") (pin "2") (pinfunction "O_2") (pintype "output"))
    )
    (net (code "129") (name "Net-(E24D-I)") (class "Default")
      (node (ref "E24") (pin "9") (pinfunction "I_9") (pintype "input"))
      (node (ref "E25") (pin "13") (pinfunction "QH_13") (pintype "output"))
      (node (ref "E9") (pin "1") (pinfunction "A_1") (pintype "input"))
      (node (ref "E9") (pin "2") (pinfunction "B_2") (pintype "input"))
    )
    (net (code "130") (name "Net-(E24E-I)") (class "Default")
      (node (ref "E24") (pin "11") (pinfunction "I_11") (pintype "input"))
      (node (ref "E25") (pin "12") (pinfunction "QG_12") (pintype "output"))
    )
    (net (code "131") (name "Net-(E24F-I)") (class "Default")
      (node (ref "E24") (pin "13") (pinfunction "I_13") (pintype "input"))
      (node (ref "E25") (pin "11") (pinfunction "QF_11") (pintype "output"))
    )
    (net (code "132") (name "Net-(E25A-A)") (class "Default")
      (node (ref "E25") (pin "1") (pinfunction "A_1") (pintype "input"))
      (node (ref "E25") (pin "2") (pinfunction "B_2") (pintype "input"))
      (node (ref "E28") (pin "3") (pinfunction "I_3") (pintype "input"))
      (node (ref "E31") (pin "13") (pinfunction "QH_13") (pintype "output"))
    )
    (net (code "133") (name "Net-(E25A-QA)") (class "Default")
      (node (ref "E25") (pin "3") (pinfunction "QA_3") (pintype "output"))
      (node (ref "E28") (pin "1") (pinfunction "I_1") (pintype "input"))
    )
    (net (code "134") (name "Net-(E25A-QB)") (class "Default")
      (node (ref "E25") (pin "4") (pinfunction "QB_4") (pintype "output"))
      (node (ref "E28") (pin "13") (pinfunction "I_13") (pintype "input"))
    )
    (net (code "135") (name "Net-(E25A-QC)") (class "Default")
      (node (ref "E25") (pin "5") (pinfunction "QC_5") (pintype "output"))
      (node (ref "E28") (pin "11") (pinfunction "I_11") (pintype "input"))
    )
    (net (code "136") (name "Net-(E25A-QD)") (class "Default")
      (node (ref "E25") (pin "6") (pinfunction "QD_6") (pintype "output"))
      (node (ref "E28") (pin "9") (pinfunction "I_9") (pintype "input"))
    )
    (net (code "137") (name "Net-(E26A-A0)") (class "Default")
      (node (ref "E26") (pin "1") (pinfunction "A0_1") (pintype "input"))
      (node (ref "R23") (pin "1") (pinfunction "1_1") (pintype "passive"))
      (node (ref "S9") (pin "2") (pinfunction "2_2") (pintype "passive"))
    )
    (net (code "138") (name "Net-(E26A-A1)") (class "Default")
      (node (ref "E26") (pin "6") (pinfunction "A1_6") (pintype "input"))
      (node (ref "R22") (pin "1") (pinfunction "1_1") (pintype "passive"))
      (node (ref "S8") (pin "2") (pinfunction "2_2") (pintype "passive"))
    )
    (net (code "139") (name "Net-(E26A-A2)") (class "Default")
      (node (ref "E26") (pin "10") (pinfunction "A2_10") (pintype "input"))
      (node (ref "R21") (pin "1") (pinfunction "1_1") (pintype "passive"))
      (node (ref "S10") (pin "2") (pinfunction "2_2") (pintype "passive"))
    )
    (net (code "140") (name "Net-(E26A-A3)") (class "Default")
      (node (ref "E26") (pin "15") (pinfunction "A3_15") (pintype "input"))
      (node (ref "R20") (pin "1") (pinfunction "1_1") (pintype "passive"))
      (node (ref "S11") (pin "2") (pinfunction "2_2") (pintype "passive"))
    )
    (net (code "141") (name "Net-(E26A-B0)") (class "Default")
      (node (ref "E26") (pin "2") (pinfunction "B0_2") (pintype "input"))
      (node (ref "I9") (pin "2") (pinfunction "2_2") (pintype "passive"))
      (node (ref "R27") (pin "2") (pinfunction "2_2") (pintype "passive"))
    )
    (net (code "142") (name "Net-(E26A-B1)") (class "Default")
      (node (ref "E26") (pin "5") (pinfunction "B1_5") (pintype "input"))
      (node (ref "I8") (pin "2") (pinfunction "2_2") (pintype "passive"))
      (node (ref "R26") (pin "2") (pinfunction "2_2") (pintype "passive"))
    )
    (net (code "143") (name "Net-(E26A-B2)") (class "Default")
      (node (ref "E26") (pin "11") (pinfunction "B2_11") (pintype "input"))
      (node (ref "I10") (pin "2") (pinfunction "2_2") (pintype "passive"))
      (node (ref "R25") (pin "2") (pinfunction "2_2") (pintype "passive"))
    )
    (net (code "144") (name "Net-(E26A-B3)") (class "Default")
      (node (ref "E26") (pin "14") (pinfunction "B3_14") (pintype "input"))
      (node (ref "I11") (pin "2") (pinfunction "2_2") (pintype "passive"))
      (node (ref "R24") (pin "2") (pinfunction "2_2") (pintype "passive"))
    )
    (net (code "145") (name "Net-(E27A-O)") (class "Default")
      (node (ref "E27") (pin "3") (pinfunction "O_3") (pintype "output"))
      (node (ref "E31") (pin "1") (pinfunction "A_1") (pintype "input"))
      (node (ref "E31") (pin "2") (pinfunction "B_2") (pintype "input"))
    )
    (net (code "146") (name "Net-(E27B-I0)") (class "Default")
      (node (ref "E27") (pin "6") (pinfunction "I0_6") (pintype "input"))
      (node (ref "E27") (pin "7") (pinfunction "I1_7") (pintype "input"))
      (node (ref "R33") (pin "1") (pinfunction "1_1") (pintype "passive"))
      (node (ref "R35") (pin "1") (pinfunction "1_1") (pintype "passive"))
    )
    (net (code "147") (name "Net-(E28C-I)") (class "Default")
      (node (ref "E28") (pin "5") (pinfunction "I_5") (pintype "input"))
      (node (ref "E31") (pin "12") (pinfunction "QG_12") (pintype "output"))
    )
    (net (code "148") (name "Net-(E29A-I0)") (class "Default")
      (node (ref "E29") (pin "11") (pinfunction "I0_11") (pintype "input"))
      (node (ref "E29") (pin "2") (pinfunction "I0_2") (pintype "input"))
      (node (ref "F0") (pin "2") (pinfunction "2_2") (pintype "passive"))
      (node (ref "R3") (pin "1") (pinfunction "1_1") (pintype "passive"))
    )
    (net (code "149") (name "Net-(E30A-CLK)") (class "Default")
      (node (ref "E30") (pin "3") (pinfunction "CLK_3") (pintype "input"))
      (node (ref "E36") (pin "3") (pinfunction "O_3") (pintype "output"))
    )
    (net (code "150") (name "Net-(E30A-~{Q})") (class "Default")
      (node (ref "E30") (pin "6") (pinfunction "~{Q}_6") (pintype "output"))
      (node (ref "E33") (pin "6") (pinfunction "I1_6") (pintype "input"))
    )
    (net (code "151") (name "Net-(E30B-CLK)") (class "Default")
      (node (ref "E30") (pin "11") (pinfunction "CLK_11") (pintype "input"))
      (node (ref "E36") (pin "11") (pinfunction "O_11") (pintype "output"))
    )
    (net (code "152") (name "Net-(E31A-QA)") (class "Default")
      (node (ref "E31") (pin "3") (pinfunction "QA_3") (pintype "output"))
      (node (ref "E34") (pin "5") (pinfunction "I_5") (pintype "input"))
    )
    (net (code "153") (name "Net-(E31A-QB)") (class "Default")
      (node (ref "E31") (pin "4") (pinfunction "QB_4") (pintype "output"))
      (node (ref "E34") (pin "3") (pinfunction "I_3") (pintype "input"))
    )
    (net (code "154") (name "Net-(E31A-QC)") (class "Default")
      (node (ref "E31") (pin "5") (pinfunction "QC_5") (pintype "output"))
      (node (ref "E34") (pin "1") (pinfunction "I_1") (pintype "input"))
    )
    (net (code "155") (name "Net-(E31A-QD)") (class "Default")
      (node (ref "E31") (pin "6") (pinfunction "QD_6") (pintype "output"))
      (node (ref "E34") (pin "13") (pinfunction "I_13") (pintype "input"))
    )
    (net (code "156") (name "Net-(E31A-QE)") (class "Default")
      (node (ref "E31") (pin "10") (pinfunction "QE_10") (pintype "output"))
      (node (ref "E34") (pin "11") (pinfunction "I_11") (pintype "input"))
    )
    (net (code "157") (name "Net-(E31A-QF)") (class "Default")
      (node (ref "E31") (pin "11") (pinfunction "QF_11") (pintype "output"))
      (node (ref "E34") (pin "9") (pinfunction "I_9") (pintype "input"))
    )
    (net (code "158") (name "Net-(E32A-I0)") (class "Default")
      (node (ref "E32") (pin "2") (pinfunction "I0_2") (pintype "input"))
      (node (ref "E35") (pin "14") (pinfunction "O_14") (pintype "output"))
    )
    (net (code "159") (name "Net-(E32B-I0)") (class "Default")
      (node (ref "E32") (pin "5") (pinfunction "I0_5") (pintype "input"))
      (node (ref "E35") (pin "13") (pinfunction "O_13") (pintype "output"))
    )
    (net (code "160") (name "Net-(E32C-I0)") (class "Default")
      (node (ref "E32") (pin "8") (pinfunction "I0_8") (pintype "input"))
      (node (ref "E35") (pin "3") (pinfunction "O_3") (pintype "output"))
    )
    (net (code "161") (name "Net-(E32D-I0)") (class "Default")
      (node (ref "E32") (pin "11") (pinfunction "I0_11") (pintype "input"))
      (node (ref "E35") (pin "2") (pinfunction "O_2") (pintype "output"))
    )
    (net (code "162") (name "Net-(E33A-I1)") (class "Default")
      (node (ref "E33") (pin "3") (pinfunction "I1_3") (pintype "input"))
      (node (ref "E33") (pin "5") (pinfunction "I0_5") (pintype "input"))
      (node (ref "E36") (pin "6") (pinfunction "O_6") (pintype "output"))
    )
    (net (code "163") (name "Net-(E33C-O)") (class "Default")
      (node (ref "E33") (pin "10") (pinfunction "O_10") (pintype "output"))
      (node (ref "E37") (pin "11") (pinfunction "CLR_11") (pintype "input"))
    )
    (net (code "164") (name "Net-(E33D-I0)") (class "Default")
      (node (ref "E33") (pin "11") (pinfunction "I0_11") (pintype "input"))
      (node (ref "E36") (pin "8") (pinfunction "O_8") (pintype "output"))
    )
    (net (code "165") (name "Net-(E35A-I0)") (class "Default")
      (node (ref "D105") (pin "A") (pinfunction "A_A") (pintype "passive"))
      (node (ref "D117") (pin "A") (pinfunction "A_A") (pintype "passive"))
      (node (ref "D129") (pin "A") (pinfunction "A_A") (pintype "passive"))
      (node (ref "D141") (pin "A") (pinfunction "A_A") (pintype "passive"))
      (node (ref "D153") (pin "A") (pinfunction "A_A") (pintype "passive"))
      (node (ref "D165") (pin "A") (pinfunction "A_A") (pintype "passive"))
      (node (ref "D177") (pin "A") (pinfunction "A_A") (pintype "passive"))
      (node (ref "D189") (pin "A") (pinfunction "A_A") (pintype "passive"))
      (node (ref "D201") (pin "A") (pinfunction "A_A") (pintype "passive"))
      (node (ref "D21") (pin "A") (pinfunction "A_A") (pintype "passive"))
      (node (ref "D213") (pin "A") (pinfunction "A_A") (pintype "passive"))
      (node (ref "D225") (pin "A") (pinfunction "A_A") (pintype "passive"))
      (node (ref "D237") (pin "A") (pinfunction "A_A") (pintype "passive"))
      (node (ref "D249") (pin "A") (pinfunction "A_A") (pintype "passive"))
      (node (ref "D261") (pin "A") (pinfunction "A_A") (pintype "passive"))
      (node (ref "D273") (pin "A") (pinfunction "A_A") (pintype "passive"))
      (node (ref "D285") (pin "A") (pinfunction "A_A") (pintype "passive"))
      (node (ref "D297") (pin "A") (pinfunction "A_A") (pintype "passive"))
      (node (ref "D309") (pin "A") (pinfunction "A_A") (pintype "passive"))
      (node (ref "D321") (pin "A") (pinfunction "A_A") (pintype "passive"))
      (node (ref "D33") (pin "A") (pinfunction "A_A") (pintype "passive"))
      (node (ref "D333") (pin "A") (pinfunction "A_A") (pintype "passive"))
      (node (ref "D345") (pin "A") (pinfunction "A_A") (pintype "passive"))
      (node (ref "D357") (pin "A") (pinfunction "A_A") (pintype "passive"))
      (node (ref "D369") (pin "A") (pinfunction "A_A") (pintype "passive"))
      (node (ref "D381") (pin "A") (pinfunction "A_A") (pintype "passive"))
      (node (ref "D45") (pin "A") (pinfunction "A_A") (pintype "passive"))
      (node (ref "D57") (pin "A") (pinfunction "A_A") (pintype "passive"))
      (node (ref "D69") (pin "A") (pinfunction "A_A") (pintype "passive"))
      (node (ref "D81") (pin "A") (pinfunction "A_A") (pintype "passive"))
      (node (ref "D9") (pin "A") (pinfunction "A_A") (pintype "passive"))
      (node (ref "D93") (pin "A") (pinfunction "A_A") (pintype "passive"))
      (node (ref "E35") (pin "4") (pinfunction "I0_4") (pintype "input"))
      (node (ref "E35") (pin "5") (pinfunction "I1_5") (pintype "input"))
      (node (ref "R48") (pin "2") (pinfunction "2_2") (pintype "passive"))
    )
    (net (code "166") (name "Net-(E35B-I0)") (class "Default")
      (node (ref "D10") (pin "A") (pinfunction "A_A") (pintype "passive"))
      (node (ref "D106") (pin "A") (pinfunction "A_A") (pintype "passive"))
      (node (ref "D118") (pin "A") (pinfunction "A_A") (pintype "passive"))
      (node (ref "D130") (pin "A") (pinfunction "A_A") (pintype "passive"))
      (node (ref "D142") (pin "A") (pinfunction "A_A") (pintype "passive"))
      (node (ref "D154") (pin "A") (pinfunction "A_A") (pintype "passive"))
      (node (ref "D166") (pin "A") (pinfunction "A_A") (pintype "passive"))
      (node (ref "D178") (pin "A") (pinfunction "A_A") (pintype "passive"))
      (node (ref "D190") (pin "A") (pinfunction "A_A") (pintype "passive"))
      (node (ref "D202") (pin "A") (pinfunction "A_A") (pintype "passive"))
      (node (ref "D214") (pin "A") (pinfunction "A_A") (pintype "passive"))
      (node (ref "D22") (pin "A") (pinfunction "A_A") (pintype "passive"))
      (node (ref "D226") (pin "A") (pinfunction "A_A") (pintype "passive"))
      (node (ref "D238") (pin "A") (pinfunction "A_A") (pintype "passive"))
      (node (ref "D250") (pin "A") (pinfunction "A_A") (pintype "passive"))
      (node (ref "D262") (pin "A") (pinfunction "A_A") (pintype "passive"))
      (node (ref "D274") (pin "A") (pinfunction "A_A") (pintype "passive"))
      (node (ref "D286") (pin "A") (pinfunction "A_A") (pintype "passive"))
      (node (ref "D298") (pin "A") (pinfunction "A_A") (pintype "passive"))
      (node (ref "D310") (pin "A") (pinfunction "A_A") (pintype "passive"))
      (node (ref "D322") (pin "A") (pinfunction "A_A") (pintype "passive"))
      (node (ref "D334") (pin "A") (pinfunction "A_A") (pintype "passive"))
      (node (ref "D34") (pin "A") (pinfunction "A_A") (pintype "passive"))
      (node (ref "D346") (pin "A") (pinfunction "A_A") (pintype "passive"))
      (node (ref "D358") (pin "A") (pinfunction "A_A") (pintype "passive"))
      (node (ref "D370") (pin "A") (pinfunction "A_A") (pintype "passive"))
      (node (ref "D382") (pin "A") (pinfunction "A_A") (pintype "passive"))
      (node (ref "D46") (pin "A") (pinfunction "A_A") (pintype "passive"))
      (node (ref "D58") (pin "A") (pinfunction "A_A") (pintype "passive"))
      (node (ref "D70") (pin "A") (pinfunction "A_A") (pintype "passive"))
      (node (ref "D82") (pin "A") (pinfunction "A_A") (pintype "passive"))
      (node (ref "D94") (pin "A") (pinfunction "A_A") (pintype "passive"))
      (node (ref "E35") (pin "6") (pinfunction "I0_6") (pintype "input"))
      (node (ref "E35") (pin "7") (pinfunction "I1_7") (pintype "input"))
      (node (ref "R49") (pin "2") (pinfunction "2_2") (pintype "passive"))
    )
    (net (code "167") (name "Net-(E35C-I0)") (class "Default")
      (node (ref "D108") (pin "A") (pinfunction "A_A") (pintype "passive"))
      (node (ref "D12") (pin "A") (pinfunction "A_A") (pintype "passive"))
      (node (ref "D120") (pin "A") (pinfunction "A_A") (pintype "passive"))
      (node (ref "D132") (pin "A") (pinfunction "A_A") (pintype "passive"))
      (node (ref "D144") (pin "A") (pinfunction "A_A") (pintype "passive"))
      (node (ref "D156") (pin "A") (pinfunction "A_A") (pintype "passive"))
      (node (ref "D168") (pin "A") (pinfunction "A_A") (pintype "passive"))
      (node (ref "D180") (pin "A") (pinfunction "A_A") (pintype "passive"))
      (node (ref "D192") (pin "A") (pinfunction "A_A") (pintype "passive"))
      (node (ref "D204") (pin "A") (pinfunction "A_A") (pintype "passive"))
      (node (ref "D216") (pin "A") (pinfunction "A_A") (pintype "passive"))
      (node (ref "D228") (pin "A") (pinfunction "A_A") (pintype "passive"))
      (node (ref "D24") (pin "A") (pinfunction "A_A") (pintype "passive"))
      (node (ref "D240") (pin "A") (pinfunction "A_A") (pintype "passive"))
      (node (ref "D252") (pin "A") (pinfunction "A_A") (pintype "passive"))
      (node (ref "D264") (pin "A") (pinfunction "A_A") (pintype "passive"))
      (node (ref "D276") (pin "A") (pinfunction "A_A") (pintype "passive"))
      (node (ref "D288") (pin "A") (pinfunction "A_A") (pintype "passive"))
      (node (ref "D300") (pin "A") (pinfunction "A_A") (pintype "passive"))
      (node (ref "D312") (pin "A") (pinfunction "A_A") (pintype "passive"))
      (node (ref "D324") (pin "A") (pinfunction "A_A") (pintype "passive"))
      (node (ref "D336") (pin "A") (pinfunction "A_A") (pintype "passive"))
      (node (ref "D348") (pin "A") (pinfunction "A_A") (pintype "passive"))
      (node (ref "D36") (pin "A") (pinfunction "A_A") (pintype "passive"))
      (node (ref "D360") (pin "A") (pinfunction "A_A") (pintype "passive"))
      (node (ref "D372") (pin "A") (pinfunction "A_A") (pintype "passive"))
      (node (ref "D384") (pin "A") (pinfunction "A_A") (pintype "passive"))
      (node (ref "D48") (pin "A") (pinfunction "A_A") (pintype "passive"))
      (node (ref "D60") (pin "A") (pinfunction "A_A") (pintype "passive"))
      (node (ref "D72") (pin "A") (pinfunction "A_A") (pintype "passive"))
      (node (ref "D84") (pin "A") (pinfunction "A_A") (pintype "passive"))
      (node (ref "D96") (pin "A") (pinfunction "A_A") (pintype "passive"))
      (node (ref "E35") (pin "10") (pinfunction "I1_10") (pintype "input"))
      (node (ref "E35") (pin "9") (pinfunction "I0_9") (pintype "input"))
      (node (ref "R51") (pin "2") (pinfunction "2_2") (pintype "passive"))
    )
    (net (code "168") (name "Net-(E35D-I0)") (class "Default")
      (node (ref "D107") (pin "A") (pinfunction "A_A") (pintype "passive"))
      (node (ref "D11") (pin "A") (pinfunction "A_A") (pintype "passive"))
      (node (ref "D119") (pin "A") (pinfunction "A_A") (pintype "passive"))
      (node (ref "D131") (pin "A") (pinfunction "A_A") (pintype "passive"))
      (node (ref "D143") (pin "A") (pinfunction "A_A") (pintype "passive"))
      (node (ref "D155") (pin "A") (pinfunction "A_A") (pintype "passive"))
      (node (ref "D167") (pin "A") (pinfunction "A_A") (pintype "passive"))
      (node (ref "D179") (pin "A") (pinfunction "A_A") (pintype "passive"))
      (node (ref "D191") (pin "A") (pinfunction "A_A") (pintype "passive"))
      (node (ref "D203") (pin "A") (pinfunction "A_A") (pintype "passive"))
      (node (ref "D215") (pin "A") (pinfunction "A_A") (pintype "passive"))
      (node (ref "D227") (pin "A") (pinfunction "A_A") (pintype "passive"))
      (node (ref "D23") (pin "A") (pinfunction "A_A") (pintype "passive"))
      (node (ref "D239") (pin "A") (pinfunction "A_A") (pintype "passive"))
      (node (ref "D251") (pin "A") (pinfunction "A_A") (pintype "passive"))
      (node (ref "D263") (pin "A") (pinfunction "A_A") (pintype "passive"))
      (node (ref "D275") (pin "A") (pinfunction "A_A") (pintype "passive"))
      (node (ref "D287") (pin "A") (pinfunction "A_A") (pintype "passive"))
      (node (ref "D299") (pin "A") (pinfunction "A_A") (pintype "passive"))
      (node (ref "D311") (pin "A") (pinfunction "A_A") (pintype "passive"))
      (node (ref "D323") (pin "A") (pinfunction "A_A") (pintype "passive"))
      (node (ref "D335") (pin "A") (pinfunction "A_A") (pintype "passive"))
      (node (ref "D347") (pin "A") (pinfunction "A_A") (pintype "passive"))
      (node (ref "D35") (pin "A") (pinfunction "A_A") (pintype "passive"))
      (node (ref "D359") (pin "A") (pinfunction "A_A") (pintype "passive"))
      (node (ref "D371") (pin "A") (pinfunction "A_A") (pintype "passive"))
      (node (ref "D383") (pin "A") (pinfunction "A_A") (pintype "passive"))
      (node (ref "D47") (pin "A") (pinfunction "A_A") (pintype "passive"))
      (node (ref "D59") (pin "A") (pinfunction "A_A") (pintype "passive"))
      (node (ref "D71") (pin "A") (pinfunction "A_A") (pintype "passive"))
      (node (ref "D83") (pin "A") (pinfunction "A_A") (pintype "passive"))
      (node (ref "D95") (pin "A") (pinfunction "A_A") (pintype "passive"))
      (node (ref "E35") (pin "11") (pinfunction "I0_11") (pintype "input"))
      (node (ref "E35") (pin "12") (pinfunction "I1_12") (pintype "input"))
      (node (ref "R50") (pin "2") (pinfunction "2_2") (pintype "passive"))
    )
    (net (code "169") (name "Net-(E37A-A)") (class "Default")
      (node (ref "E37") (pin "1") (pinfunction "A_1") (pintype "input"))
      (node (ref "E37") (pin "5") (pinfunction "Q_5") (pintype "output"))
    )
    (net (code "170") (name "Net-(E37A-C)") (class "Default")
      (node (ref "C5") (pin "1") (pinfunction "1_1") (pintype "passive"))
      (node (ref "E37") (pin "14") (pinfunction "C_14") (pintype "input"))
    )
    (net (code "171") (name "Net-(E37A-R{slash}C)") (class "Default")
      (node (ref "C5") (pin "2") (pinfunction "2_2") (pintype "passive"))
      (node (ref "E37") (pin "15") (pinfunction "R/C_15") (pintype "input"))
      (node (ref "R37") (pin "2") (pinfunction "2_2") (pintype "passive"))
    )
    (net (code "172") (name "Net-(E37B-C)") (class "Default")
      (node (ref "C4") (pin "1") (pinfunction "1_1") (pintype "passive"))
      (node (ref "E37") (pin "6") (pinfunction "C_6") (pintype "input"))
    )
    (net (code "173") (name "Net-(E37B-R{slash}C)") (class "Default")
      (node (ref "C4") (pin "2") (pinfunction "2_2") (pintype "passive"))
      (node (ref "E37") (pin "7") (pinfunction "R/C_7") (pintype "input"))
      (node (ref "R36") (pin "2") (pinfunction "2_2") (pintype "passive"))
    )
    (net (code "174") (name "Net-(Q1-B)") (class "Default")
      (node (ref "Q1") (pin "2") (pinfunction "B_2") (pintype "passive"))
      (node (ref "R29") (pin "2") (pinfunction "2_2") (pintype "passive"))
    )
    (net (code "175") (name "Net-(Q1-C)") (class "Default")
      (node (ref "Q1") (pin "3") (pinfunction "C_3") (pintype "passive"))
      (node (ref "R30") (pin "1") (pinfunction "1_1") (pintype "passive"))
    )
    (net (code "176") (name "PULSE_LA") (class "Default")
      (node (ref "Q1") (pin "1") (pinfunction "E_1") (pintype "passive"))
      (node (ref "U$2") (pin "DR2") (pinfunction "1_DR2") (pintype "bidirectional"))
    )
    (net (code "177") (name "SET_GO") (class "Default")
      (node (ref "E18") (pin "11") (pinfunction "CLK_11") (pintype "input"))
      (node (ref "E19") (pin "12") (pinfunction "~{Q}_12") (pintype "output"))
    )
    (net (code "178") (name "SHIFT_CLOCK") (class "Default")
      (node (ref "E24") (pin "4") (pinfunction "O_4") (pintype "output"))
      (node (ref "E25") (pin "8") (pinfunction "CLK_8") (pintype "input"))
      (node (ref "E31") (pin "8") (pinfunction "CLK_8") (pintype "input"))
      (node (ref "E6") (pin "8") (pinfunction "CLK_8") (pintype "input"))
      (node (ref "E9") (pin "8") (pinfunction "CLK_8") (pintype "input"))
    )
    (net (code "179") (name "SW") (class "Default")
      (node (ref "R32") (pin "2") (pinfunction "2_2") (pintype "passive"))
      (node (ref "U$2") (pin "DV2") (pinfunction "1_DV2") (pintype "bidirectional"))
    )
    (net (code "180") (name "TP4") (class "Default")
      (node (ref "E20") (pin "5") (pinfunction "I1_5") (pintype "input"))
      (node (ref "E20") (pin "6") (pinfunction "I0_6") (pintype "input"))
      (node (ref "E20") (pin "7") (pinfunction "I1_7") (pintype "input"))
      (node (ref "E33") (pin "9") (pinfunction "I1_9") (pintype "input"))
      (node (ref "U$2") (pin "CJ2") (pinfunction "1_CJ2") (pintype "bidirectional"))
    )
    (net (code "181") (name "VCC") (class "Default")
      (node (ref "C10") (pin "+") (pinfunction "+_+") (pintype "passive"))
      (node (ref "C11") (pin "+") (pinfunction "+_+") (pintype "passive"))
      (node (ref "C12") (pin "1") (pinfunction "1_1") (pintype "passive"))
      (node (ref "C13") (pin "1") (pinfunction "1_1") (pintype "passive"))
      (node (ref "C14") (pin "1") (pinfunction "1_1") (pintype "passive"))
      (node (ref "C15") (pin "1") (pinfunction "1_1") (pintype "passive"))
      (node (ref "C16") (pin "1") (pinfunction "1_1") (pintype "passive"))
      (node (ref "C17") (pin "1") (pinfunction "1_1") (pintype "passive"))
      (node (ref "C18") (pin "1") (pinfunction "1_1") (pintype "passive"))
      (node (ref "C19") (pin "1") (pinfunction "1_1") (pintype "passive"))
      (node (ref "C2") (pin "+") (pinfunction "+_+") (pintype "passive"))
      (node (ref "C20") (pin "1") (pinfunction "1_1") (pintype "passive"))
      (node (ref "C21") (pin "1") (pinfunction "1_1") (pintype "passive"))
      (node (ref "C22") (pin "1") (pinfunction "1_1") (pintype "passive"))
      (node (ref "C23") (pin "1") (pinfunction "1_1") (pintype "passive"))
      (node (ref "C24") (pin "1") (pinfunction "1_1") (pintype "passive"))
      (node (ref "C25") (pin "1") (pinfunction "1_1") (pintype "passive"))
      (node (ref "C26") (pin "1") (pinfunction "1_1") (pintype "passive"))
      (node (ref "C27") (pin "1") (pinfunction "1_1") (pintype "passive"))
      (node (ref "C28") (pin "1") (pinfunction "1_1") (pintype "passive"))
      (node (ref "C29") (pin "1") (pinfunction "1_1") (pintype "passive"))
      (node (ref "C30") (pin "1") (pinfunction "1_1") (pintype "passive"))
      (node (ref "C31") (pin "1") (pinfunction "1_1") (pintype "passive"))
      (node (ref "C32") (pin "1") (pinfunction "1_1") (pintype "passive"))
      (node (ref "C33") (pin "1") (pinfunction "1_1") (pintype "passive"))
      (node (ref "C34") (pin "1") (pinfunction "1_1") (pintype "passive"))
      (node (ref "C35") (pin "1") (pinfunction "1_1") (pintype "passive"))
      (node (ref "C36") (pin "1") (pinfunction "1_1") (pintype "passive"))
      (node (ref "C37") (pin "1") (pinfunction "1_1") (pintype "passive"))
      (node (ref "C38") (pin "1") (pinfunction "1_1") (pintype "passive"))
      (node (ref "C39") (pin "1") (pinfunction "1_1") (pintype "passive"))
      (node (ref "C40") (pin "1") (pinfunction "1_1") (pintype "passive"))
      (node (ref "C41") (pin "1") (pinfunction "1_1") (pintype "passive"))
      (node (ref "C42") (pin "1") (pinfunction "1_1") (pintype "passive"))
      (node (ref "C43") (pin "1") (pinfunction "1_1") (pintype "passive"))
      (node (ref "C44") (pin "1") (pinfunction "1_1") (pintype "passive"))
      (node (ref "C45") (pin "1") (pinfunction "1_1") (pintype "passive"))
      (node (ref "C46") (pin "1") (pinfunction "1_1") (pintype "passive"))
      (node (ref "C47") (pin "1") (pinfunction "1_1") (pintype "passive"))
      (node (ref "C48") (pin "1") (pinfunction "1_1") (pintype "passive"))
      (node (ref "C8") (pin "+") (pinfunction "+_+") (pintype "passive"))
      (node (ref "D385") (pin "A") (pinfunction "A_A") (pintype "passive"))
      (node (ref "R1") (pin "2") (pinfunction "2_2") (pintype "passive"))
      (node (ref "R12") (pin "2") (pinfunction "2_2") (pintype "passive"))
      (node (ref "R13") (pin "2") (pinfunction "2_2") (pintype "passive"))
      (node (ref "R14") (pin "2") (pinfunction "2_2") (pintype "passive"))
      (node (ref "R15") (pin "2") (pinfunction "2_2") (pintype "passive"))
      (node (ref "R2") (pin "2") (pinfunction "2_2") (pintype "passive"))
      (node (ref "R20") (pin "2") (pinfunction "2_2") (pintype "passive"))
      (node (ref "R21") (pin "2") (pinfunction "2_2") (pintype "passive"))
      (node (ref "R22") (pin "2") (pinfunction "2_2") (pintype "passive"))
      (node (ref "R23") (pin "2") (pinfunction "2_2") (pintype "passive"))
      (node (ref "R28") (pin "2") (pinfunction "2_2") (pintype "passive"))
      (node (ref "R3") (pin "2") (pinfunction "2_2") (pintype "passive"))
      (node (ref "R30") (pin "2") (pinfunction "2_2") (pintype "passive"))
      (node (ref "R31") (pin "1") (pinfunction "1_1") (pintype "passive"))
      (node (ref "R34") (pin "1") (pinfunction "1_1") (pintype "passive"))
      (node (ref "R36") (pin "1") (pinfunction "1_1") (pintype "passive"))
      (node (ref "R37") (pin "1") (pinfunction "1_1") (pintype "passive"))
      (node (ref "R39") (pin "2") (pinfunction "2_2") (pintype "passive"))
      (node (ref "R4") (pin "2") (pinfunction "2_2") (pintype "passive"))
      (node (ref "R40") (pin "1") (pinfunction "1_1") (pintype "passive"))
      (node (ref "R41") (pin "1") (pinfunction "1_1") (pintype "passive"))
      (node (ref "R42") (pin "1") (pinfunction "1_1") (pintype "passive"))
      (node (ref "R43") (pin "1") (pinfunction "1_1") (pintype "passive"))
      (node (ref "R44") (pin "1") (pinfunction "1_1") (pintype "passive"))
      (node (ref "R45") (pin "1") (pinfunction "1_1") (pintype "passive"))
      (node (ref "R46") (pin "1") (pinfunction "1_1") (pintype "passive"))
      (node (ref "R47") (pin "1") (pinfunction "1_1") (pintype "passive"))
      (node (ref "R48") (pin "1") (pinfunction "1_1") (pintype "passive"))
      (node (ref "R49") (pin "1") (pinfunction "1_1") (pintype "passive"))
      (node (ref "R5") (pin "2") (pinfunction "2_2") (pintype "passive"))
      (node (ref "R50") (pin "1") (pinfunction "1_1") (pintype "passive"))
      (node (ref "R51") (pin "1") (pinfunction "1_1") (pintype "passive"))
      (node (ref "R53") (pin "2") (pinfunction "2_2") (pintype "passive"))
      (node (ref "R6") (pin "2") (pinfunction "2_2") (pintype "passive"))
      (node (ref "R7") (pin "2") (pinfunction "2_2") (pintype "passive"))
      (node (ref "U$2") (pin "AA2") (pinfunction "1_AA2") (pintype "bidirectional"))
      (node (ref "U$2") (pin "BA2") (pinfunction "1_BA2") (pintype "bidirectional"))
      (node (ref "U$2") (pin "CA2") (pinfunction "1_CA2") (pintype "bidirectional"))
    )
    (net (code "182") (name "unconnected-(E12A-Q-Pad5)") (class "Default")
      (node (ref "E12") (pin "5") (pinfunction "Q_5") (pintype "output"))
    )
    (net (code "183") (name "unconnected-(E18B-~{Q}-Pad8)") (class "Default")
      (node (ref "E18") (pin "8") (pinfunction "~{Q}_8") (pintype "output"))
    )
    (net (code "184") (name "unconnected-(E19A-Q-Pad13)") (class "Default")
      (node (ref "E19") (pin "13") (pinfunction "Q_13") (pintype "output"))
    )
    (net (code "185") (name "unconnected-(E23A-Q-Pad5)") (class "Default")
      (node (ref "E23") (pin "5") (pinfunction "Q_5") (pintype "output"))
    )
    (net (code "186") (name "unconnected-(E37A-~{Q}-Pad4)") (class "Default")
      (node (ref "E37") (pin "4") (pinfunction "~{Q}_4") (pintype "output"))
    )
    (net (code "187") (name "unconnected-(E37B-~{Q}-Pad12)") (class "Default")
      (node (ref "E37") (pin "12") (pinfunction "~{Q}_12") (pintype "output"))
    )
    (net (code "188") (name "~{ACTIVE}") (class "Default")
      (node (ref "E15") (pin "12") (pinfunction "I1_12") (pintype "input"))
      (node (ref "E15") (pin "2") (pinfunction "I0_2") (pintype "input"))
      (node (ref "E18") (pin "5") (pinfunction "Q_5") (pintype "output"))
    )
    (net (code "189") (name "~{CLR_GO}") (class "Default")
      (node (ref "E10") (pin "4") (pinfunction "O_4") (pintype "output"))
      (node (ref "E18") (pin "10") (pinfunction "PRE_10") (pintype "input"))
    )
    (net (code "190") (name "~{D2}") (class "Default")
      (node (ref "E18") (pin "1") (pinfunction "CLR_1") (pintype "input"))
      (node (ref "E19") (pin "4") (pinfunction "~{Q}_4") (pintype "output"))
      (node (ref "E23") (pin "1") (pinfunction "CLR_1") (pintype "input"))
      (node (ref "E37") (pin "10") (pinfunction "B_10") (pintype "input"))
    )
    (net (code "191") (name "~{DATA00}") (class "Default")
      (node (ref "E4") (pin "10") (pinfunction "O_10") (pintype "open_collector"))
      (node (ref "E7") (pin "12") (pinfunction "F2_12") (pintype "open_collector"))
      (node (ref "U$2") (pin "AR1") (pinfunction "1_AR1") (pintype "bidirectional"))
    )
    (net (code "192") (name "~{DATA01}") (class "Default")
      (node (ref "E4") (pin "13") (pinfunction "O_13") (pintype "open_collector"))
      (node (ref "E7") (pin "13") (pinfunction "F3_13") (pintype "open_collector"))
      (node (ref "U$2") (pin "AS1") (pinfunction "1_AS1") (pintype "bidirectional"))
    )
    (net (code "193") (name "~{DATA02}") (class "Default")
      (node (ref "E4") (pin "4") (pinfunction "O_4") (pintype "open_collector"))
      (node (ref "E7") (pin "4") (pinfunction "F1_4") (pintype "open_collector"))
      (node (ref "U$2") (pin "AU1") (pinfunction "1_AU1") (pintype "bidirectional"))
    )
    (net (code "194") (name "~{DATA03}") (class "Default")
      (node (ref "E4") (pin "1") (pinfunction "O_1") (pintype "open_collector"))
      (node (ref "E7") (pin "3") (pinfunction "F0_3") (pintype "open_collector"))
      (node (ref "U$2") (pin "AV1") (pinfunction "1_AV1") (pintype "bidirectional"))
    )
    (net (code "195") (name "~{DATA04}") (class "Default")
      (node (ref "E11") (pin "4") (pinfunction "F1_4") (pintype "open_collector"))
      (node (ref "E14") (pin "10") (pinfunction "O_10") (pintype "open_collector"))
      (node (ref "U$2") (pin "BR1") (pinfunction "1_BR1") (pintype "bidirectional"))
    )
    (net (code "196") (name "~{DATA05}") (class "Default")
      (node (ref "E11") (pin "3") (pinfunction "F0_3") (pintype "open_collector"))
      (node (ref "E14") (pin "13") (pinfunction "O_13") (pintype "open_collector"))
      (node (ref "U$2") (pin "BS1") (pinfunction "1_BS1") (pintype "bidirectional"))
    )
    (net (code "197") (name "~{DATA06}") (class "Default")
      (node (ref "E11") (pin "12") (pinfunction "F2_12") (pintype "open_collector"))
      (node (ref "E14") (pin "4") (pinfunction "O_4") (pintype "open_collector"))
      (node (ref "E21") (pin "10") (pinfunction "O_10") (pintype "open_collector"))
      (node (ref "U$2") (pin "BU1") (pinfunction "1_BU1") (pintype "bidirectional"))
    )
    (net (code "198") (name "~{DATA07}") (class "Default")
      (node (ref "E11") (pin "13") (pinfunction "F3_13") (pintype "open_collector"))
      (node (ref "E14") (pin "1") (pinfunction "O_1") (pintype "open_collector"))
      (node (ref "E21") (pin "1") (pinfunction "O_1") (pintype "open_collector"))
      (node (ref "U$2") (pin "BV1") (pinfunction "1_BV1") (pintype "bidirectional"))
    )
    (net (code "199") (name "~{DATA08}") (class "Default")
      (node (ref "E26") (pin "4") (pinfunction "F1_4") (pintype "open_collector"))
      (node (ref "E29") (pin "1") (pinfunction "O_1") (pintype "open_collector"))
      (node (ref "E32") (pin "10") (pinfunction "O_10") (pintype "open_collector"))
      (node (ref "U$2") (pin "DR1") (pinfunction "1_DR1") (pintype "bidirectional"))
    )
    (net (code "200") (name "~{DATA09}") (class "Default")
      (node (ref "E26") (pin "3") (pinfunction "F0_3") (pintype "open_collector"))
      (node (ref "E29") (pin "4") (pinfunction "O_4") (pintype "open_collector"))
      (node (ref "E32") (pin "13") (pinfunction "O_13") (pintype "open_collector"))
      (node (ref "U$2") (pin "DS1") (pinfunction "1_DS1") (pintype "bidirectional"))
    )
    (net (code "201") (name "~{DATA10}") (class "Default")
      (node (ref "E26") (pin "12") (pinfunction "F2_12") (pintype "open_collector"))
      (node (ref "E29") (pin "10") (pinfunction "O_10") (pintype "open_collector"))
      (node (ref "E32") (pin "4") (pinfunction "O_4") (pintype "open_collector"))
      (node (ref "U$2") (pin "DU1") (pinfunction "1_DU1") (pintype "bidirectional"))
    )
    (net (code "202") (name "~{DATA11}") (class "Default")
      (node (ref "E26") (pin "13") (pinfunction "F3_13") (pintype "open_collector"))
      (node (ref "E29") (pin "13") (pinfunction "O_13") (pintype "open_collector"))
      (node (ref "E32") (pin "1") (pinfunction "O_1") (pintype "open_collector"))
      (node (ref "U$2") (pin "DV1") (pinfunction "1_DV1") (pintype "bidirectional"))
    )
    (net (code "203") (name "~{FIELD}") (class "Default")
      (node (ref "E33") (pin "1") (pinfunction "O_1") (pintype "output"))
      (node (ref "E5") (pin "2") (pinfunction "I1_2") (pintype "input"))
      (node (ref "E5") (pin "4") (pinfunction "I0_4") (pintype "input"))
    )
    (net (code "204") (name "~{INIT_ADD}") (class "Default")
      (node (ref "E11") (pin "9") (pinfunction "S0_9") (pintype "input"))
      (node (ref "E26") (pin "9") (pinfunction "S0_9") (pintype "input"))
      (node (ref "E5") (pin "6") (pinfunction "O_6") (pintype "output"))
      (node (ref "E7") (pin "9") (pinfunction "S0_9") (pintype "input"))
      (node (ref "U$2") (pin "DA1") (pinfunction "1_DA1") (pintype "bidirectional"))
    )
    (net (code "205") (name "~{KEY_CONTROL}") (class "Default")
      (node (ref "E21") (pin "4") (pinfunction "O_4") (pintype "open_collector"))
      (node (ref "U$2") (pin "DU2") (pinfunction "1_DU2") (pintype "bidirectional"))
    )
    (net (code "206") (name "~{LA_ENABLE}") (class "Default")
      (node (ref "E22") (pin "4") (pinfunction "O_4") (pintype "open_collector"))
      (node (ref "U$2") (pin "BM2") (pinfunction "1_BM2") (pintype "bidirectional"))
    )
    (net (code "207") (name "~{LW@TP4}") (class "Default")
      (node (ref "E15") (pin "3") (pinfunction "I1_3") (pintype "input"))
      (node (ref "E15") (pin "4") (pinfunction "O_4") (pintype "output"))
    )
    (net (code "208") (name "~{MEM_START}") (class "Default")
      (node (ref "E22") (pin "1") (pinfunction "O_1") (pintype "open_collector"))
      (node (ref "U$2") (pin "AJ2") (pinfunction "1_AJ2") (pintype "bidirectional"))
    )
    (net (code "209") (name "~{MSIR_DISABLE}") (class "Default")
      (node (ref "E22") (pin "13") (pinfunction "O_13") (pintype "open_collector"))
      (node (ref "U$2") (pin "CV1") (pinfunction "1_CV1") (pintype "bidirectional"))
    )
    (net (code "210") (name "~{POWER_OK}") (class "Default")
      (node (ref "E2") (pin "11") (pinfunction "I0_11") (pintype "input"))
      (node (ref "E27") (pin "10") (pinfunction "I1_10") (pintype "input"))
      (node (ref "E27") (pin "9") (pinfunction "I0_9") (pintype "input"))
      (node (ref "Q2") (pin "3") (pinfunction "C_3") (pintype "passive"))
      (node (ref "U$2") (pin "BV2") (pinfunction "1_BV2") (pintype "bidirectional"))
    )
    (net (code "211") (name "~{RUN}") (class "Default")
      (node (ref "E16") (pin "8") (pinfunction "I0_8") (pintype "input"))
      (node (ref "E16") (pin "9") (pinfunction "I1_9") (pintype "input"))
      (node (ref "E5") (pin "12") (pinfunction "I0_12") (pintype "input"))
      (node (ref "U$2") (pin "BU2") (pinfunction "1_BU2") (pintype "bidirectional"))
    )
    (net (code "212") (name "~{START_ADD}") (class "Default")
      (node (ref "E11") (pin "7") (pinfunction "S1_7") (pintype "input"))
      (node (ref "E26") (pin "7") (pinfunction "S1_7") (pintype "input"))
      (node (ref "E5") (pin "3") (pinfunction "O_3") (pintype "output"))
      (node (ref "E7") (pin "7") (pinfunction "S1_7") (pintype "input"))
      (node (ref "U$2") (pin "CB1") (pinfunction "1_CB1") (pintype "bidirectional"))
    )
    (net (code "213") (name "~{STOP}") (class "Default")
      (node (ref "E22") (pin "10") (pinfunction "O_10") (pintype "open_collector"))
      (node (ref "U$2") (pin "DS2") (pinfunction "1_DS2") (pintype "bidirectional"))
    )
    (net (code "214") (name "~{SYSTEM_CLEAR}") (class "Default")
      (node (ref "E15") (pin "1") (pinfunction "O_1") (pintype "output"))
      (node (ref "E25") (pin "9") (pinfunction "CLR_9") (pintype "input"))
      (node (ref "E30") (pin "1") (pinfunction "CLR_1") (pintype "input"))
      (node (ref "E30") (pin "13") (pinfunction "CLR_13") (pintype "input"))
      (node (ref "E31") (pin "9") (pinfunction "CLR_9") (pintype "input"))
      (node (ref "E6") (pin "9") (pinfunction "CLR_9") (pintype "input"))
      (node (ref "E9") (pin "9") (pinfunction "CLR_9") (pintype "input"))
    )
    (net (code "215") (name "~{TS1}") (class "Default")
      (node (ref "E27") (pin "4") (pinfunction "I0_4") (pintype "input"))
      (node (ref "E27") (pin "5") (pinfunction "I1_5") (pintype "input"))
      (node (ref "U$2") (pin "CK2") (pinfunction "1_CK2") (pintype "bidirectional"))
    )
    (net (code "216") (name "~{TS3}") (class "Default")
      (node (ref "E20") (pin "10") (pinfunction "I1_10") (pintype "input"))
      (node (ref "E20") (pin "9") (pinfunction "I0_9") (pintype "input"))
      (node (ref "U$2") (pin "CM2") (pinfunction "1_CM2") (pintype "bidirectional"))
    )
  )
)
